# module_Rnx_ctrl.net
KiCad netlist of a schematic drawn in EAGLE
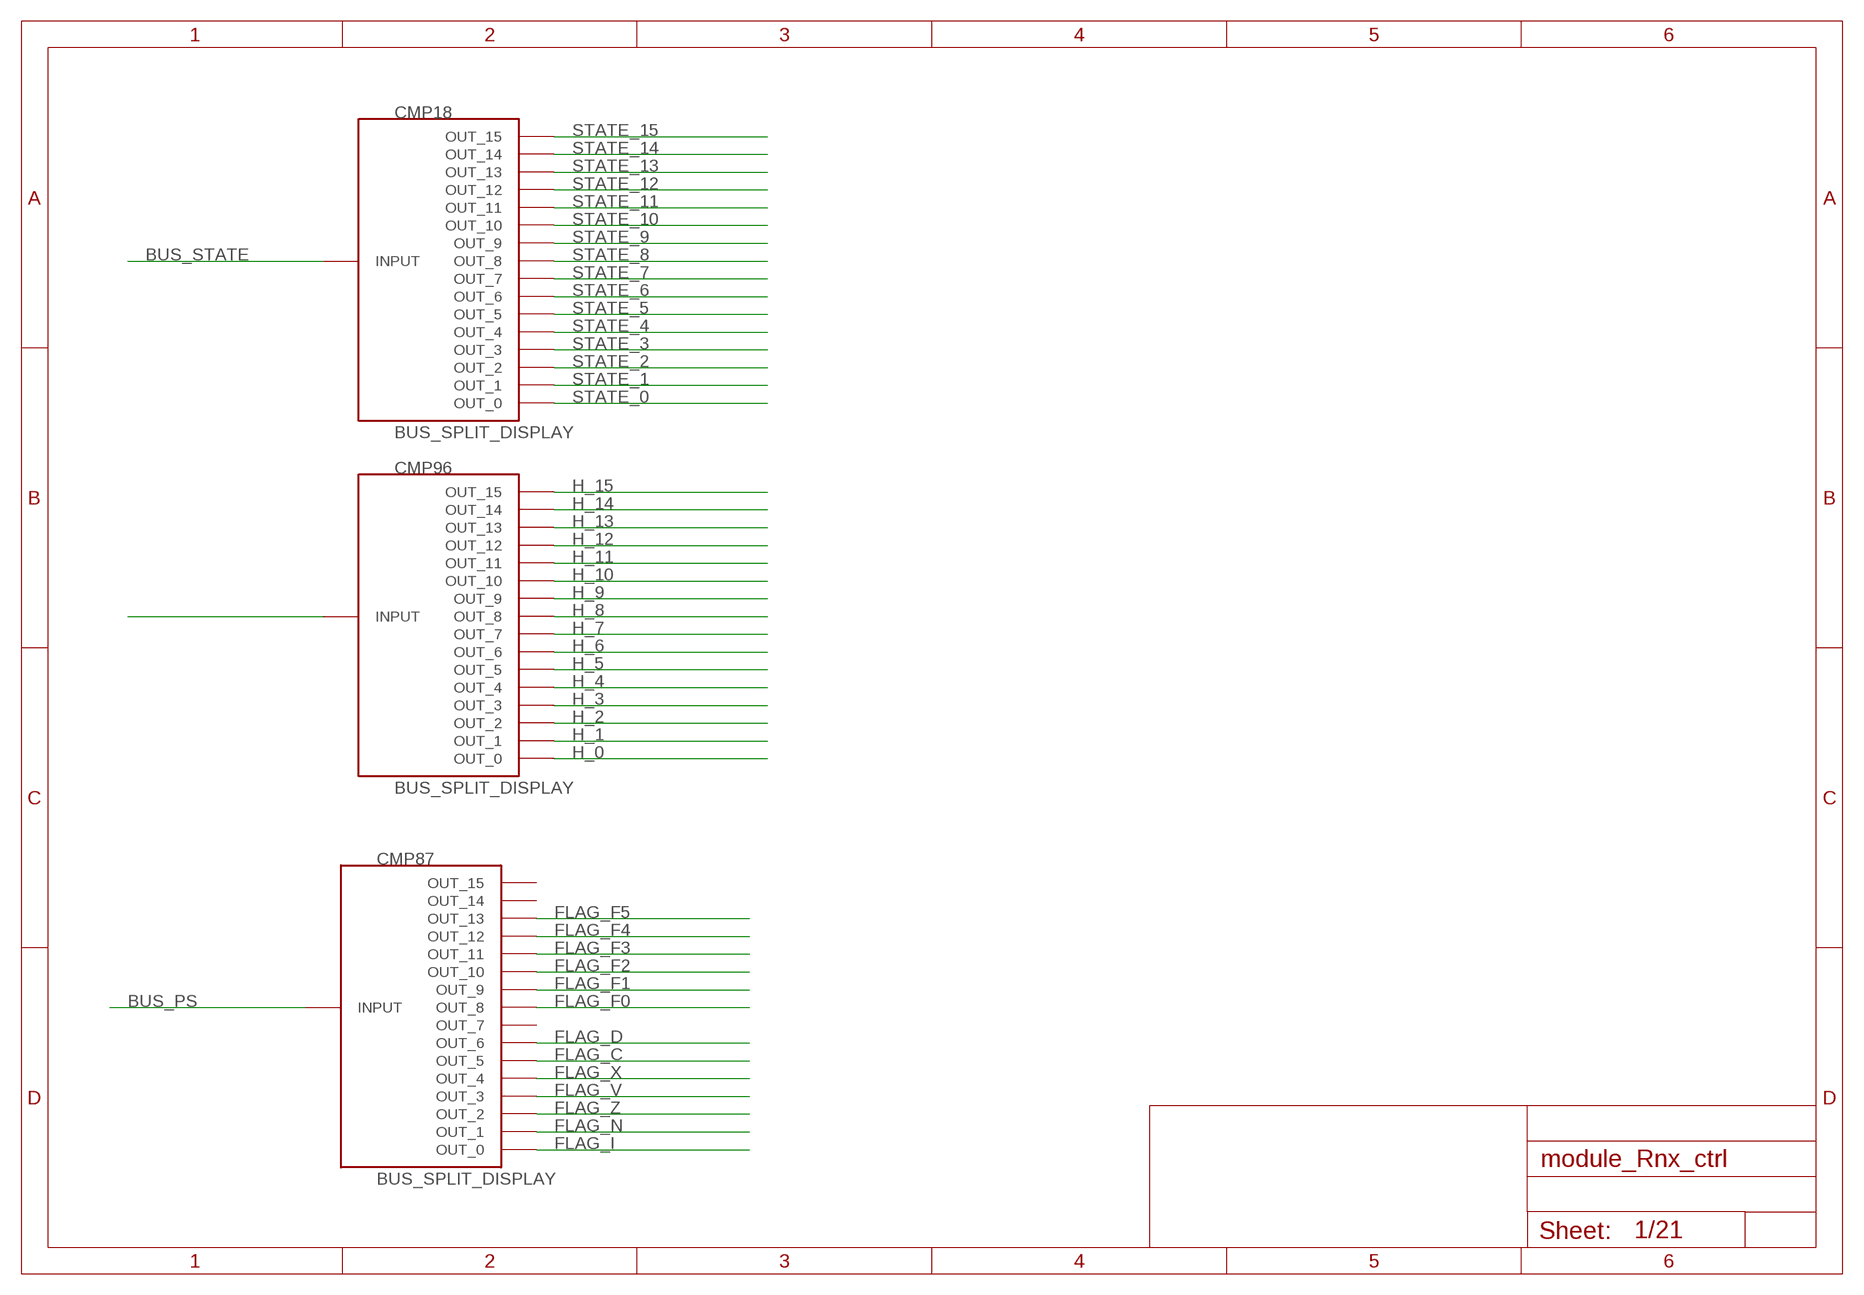
[diagram p0: schematic, sheet 1]
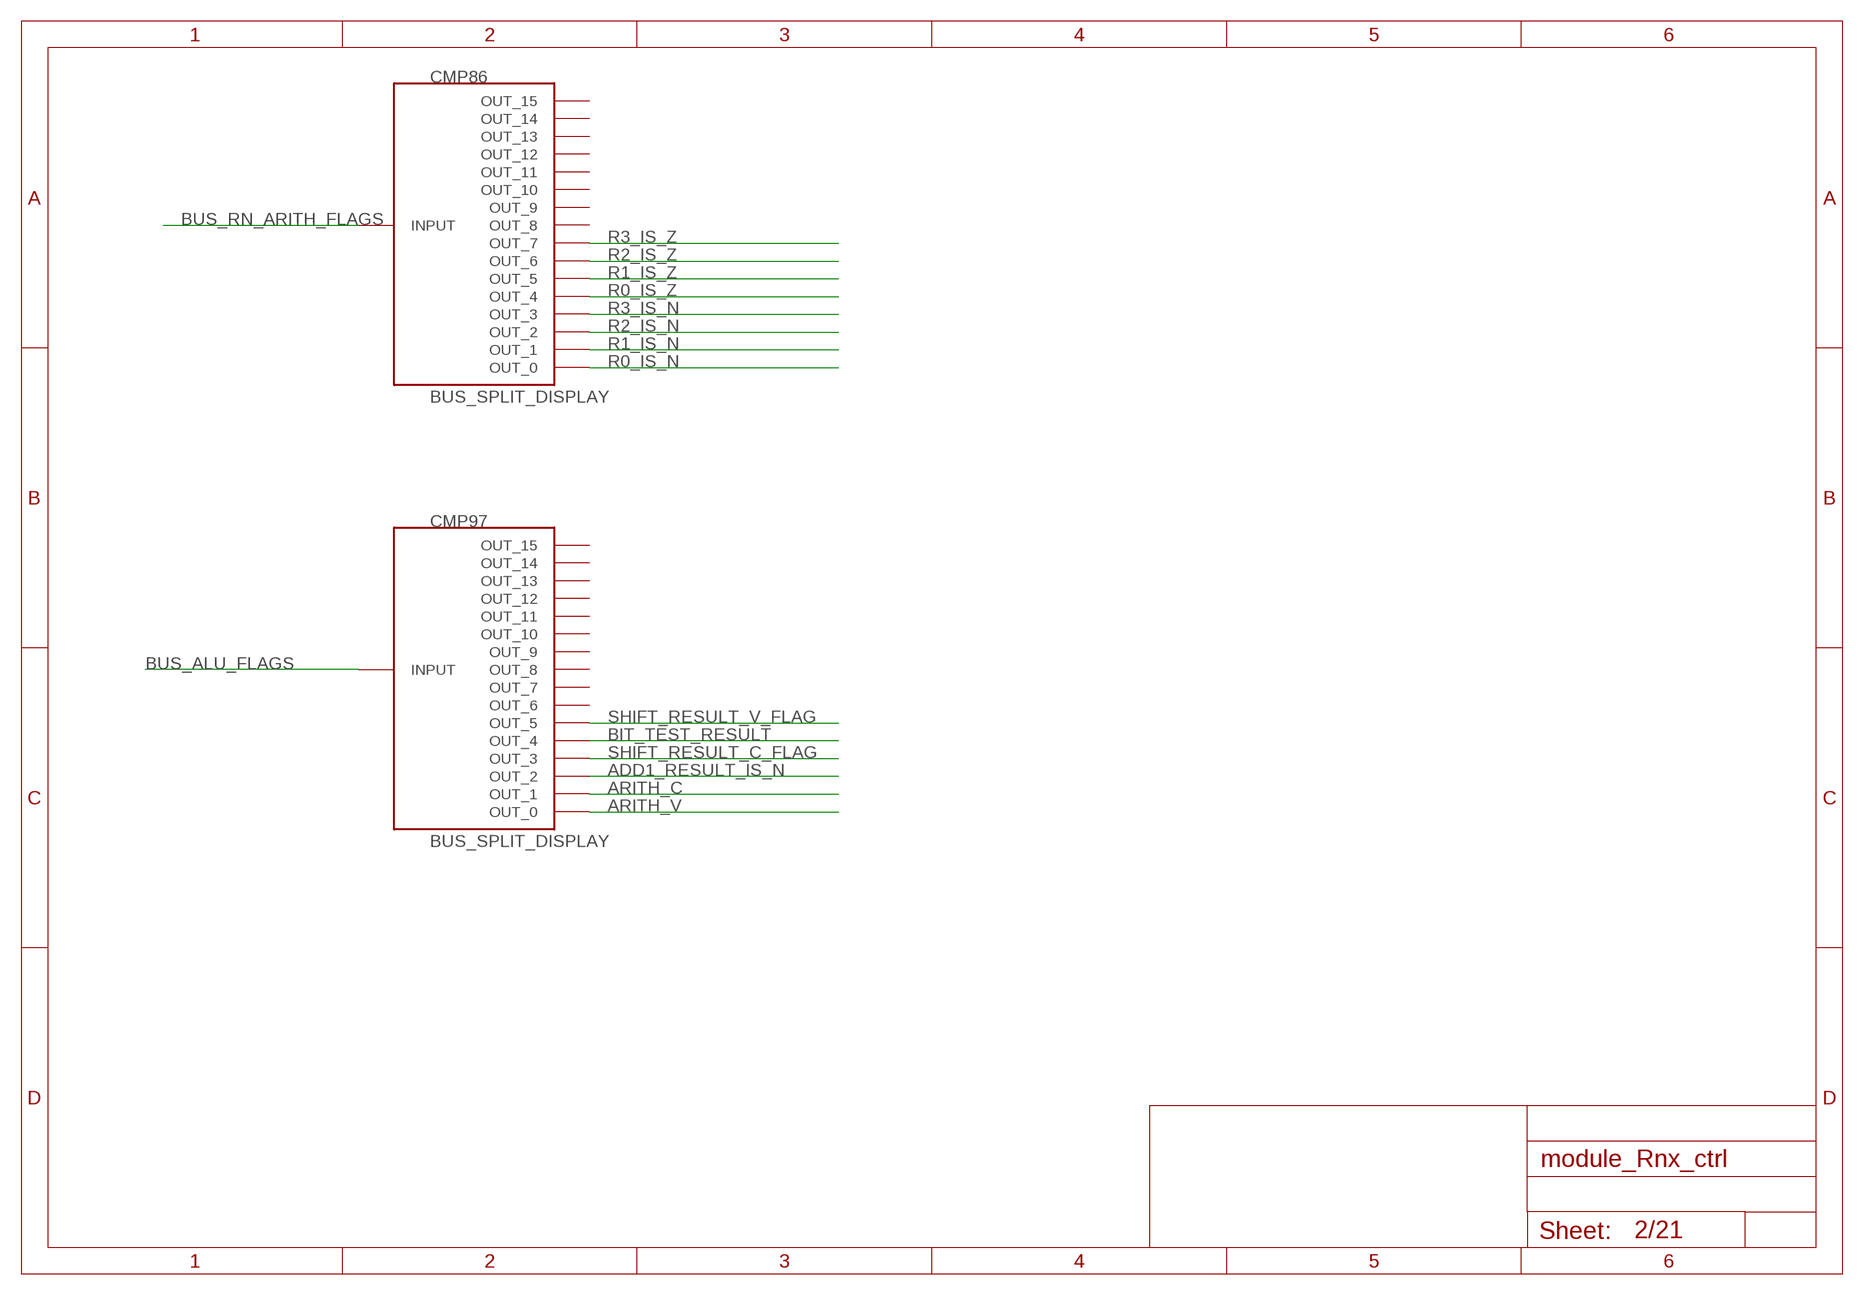
[diagram p1: schematic, sheet 2]
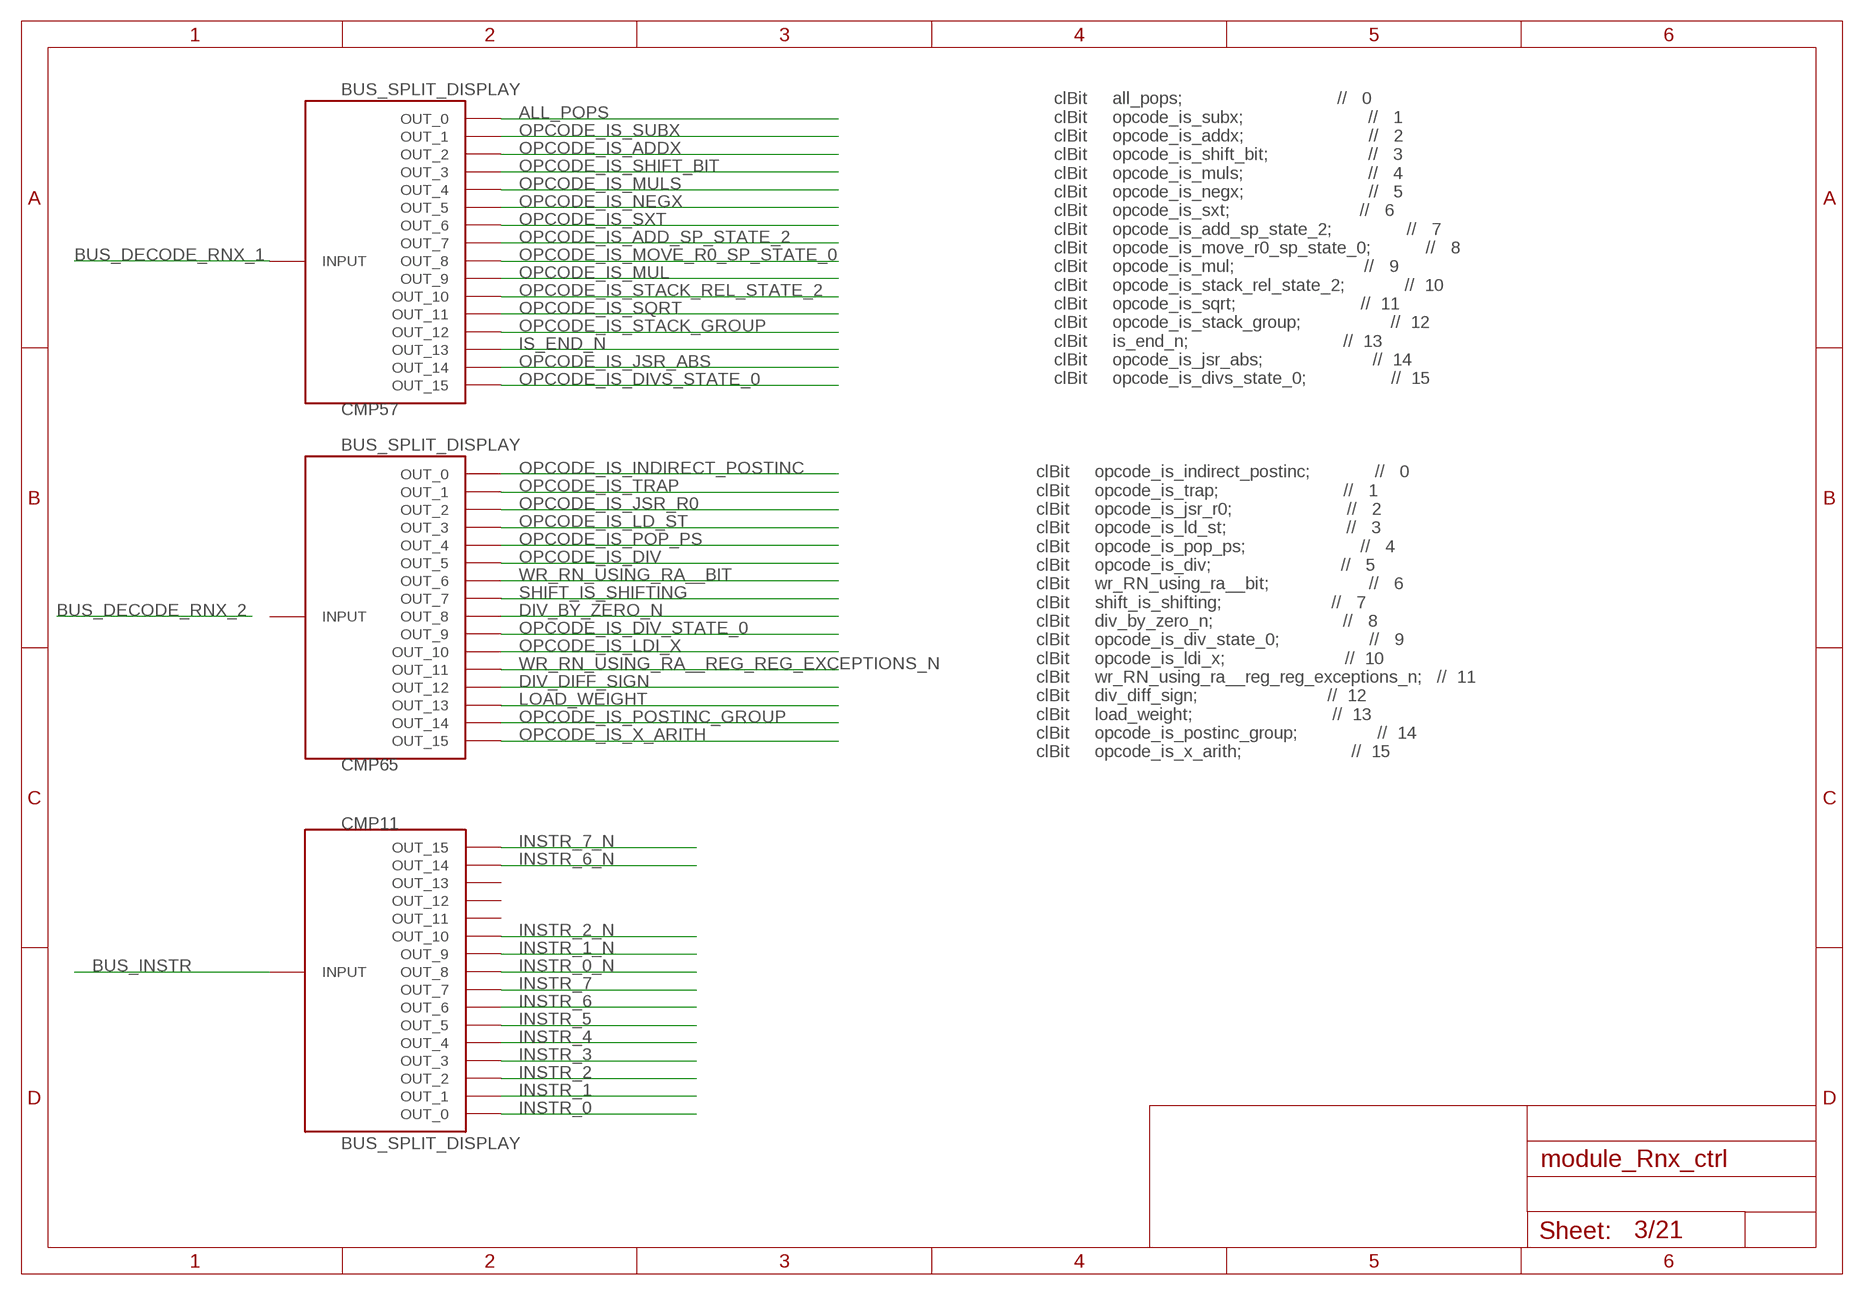
[diagram p2: schematic, sheet 3]
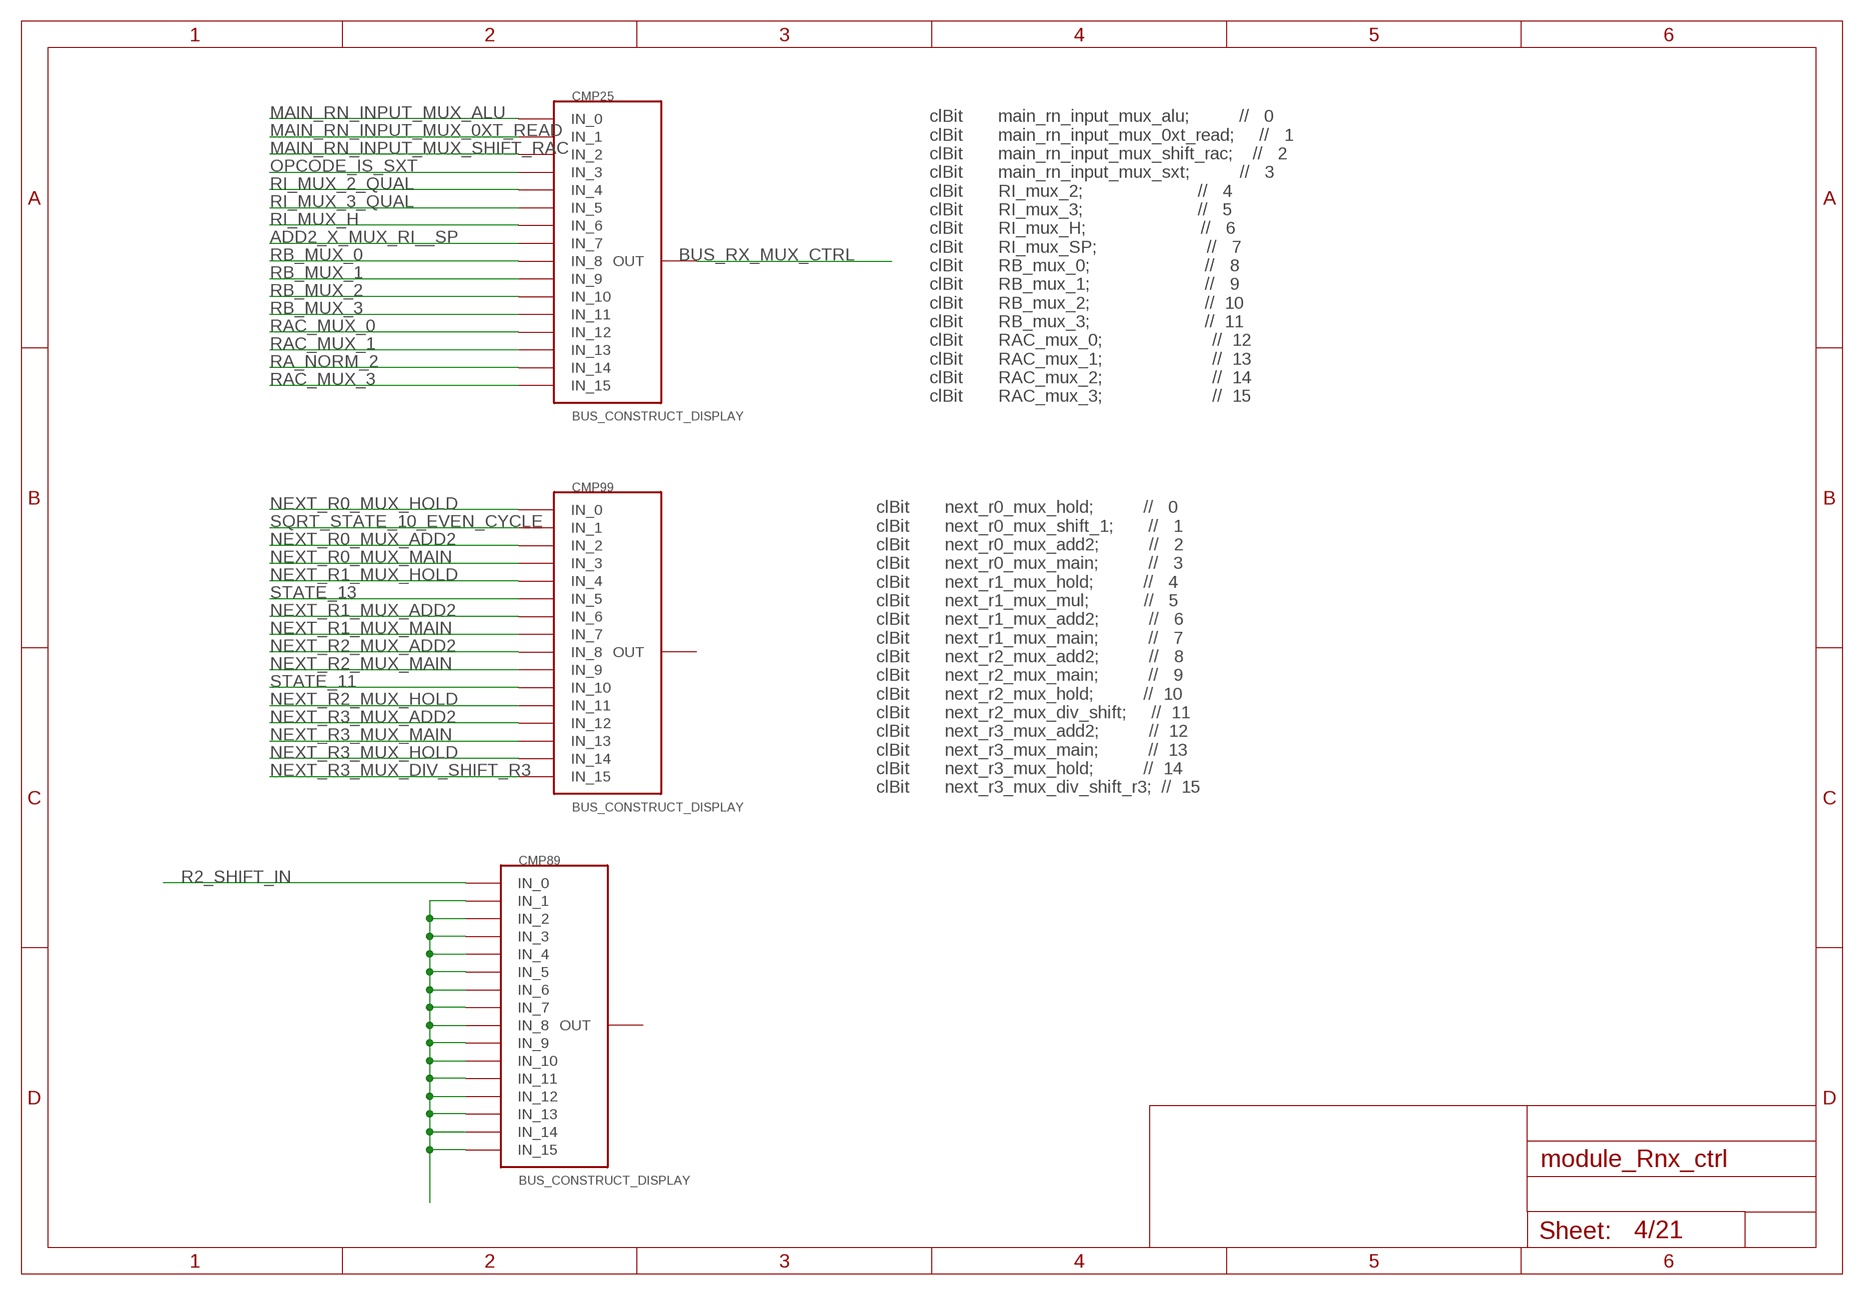
[diagram p3: schematic, sheet 4]
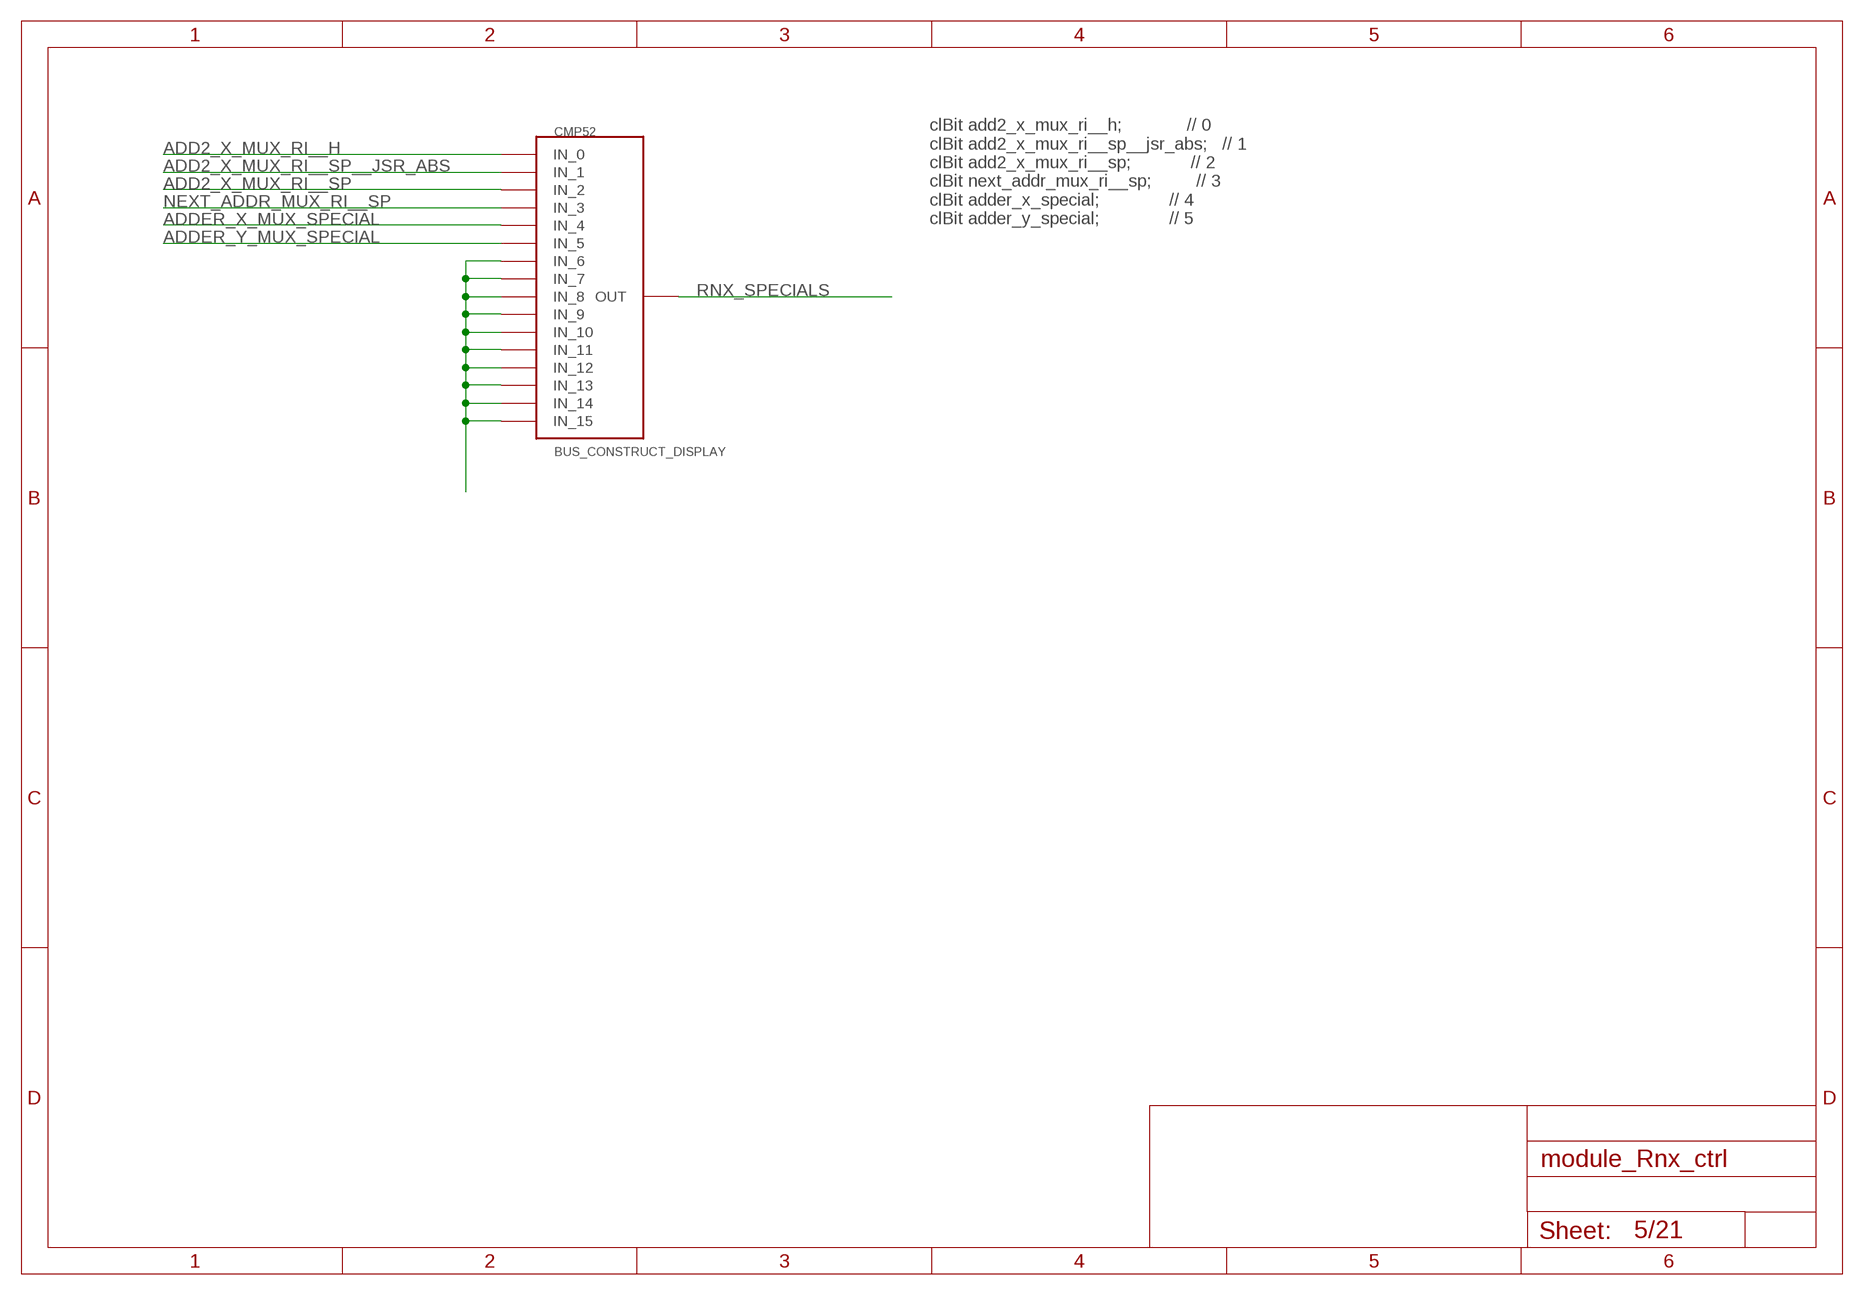
[diagram p4: schematic, sheet 5]
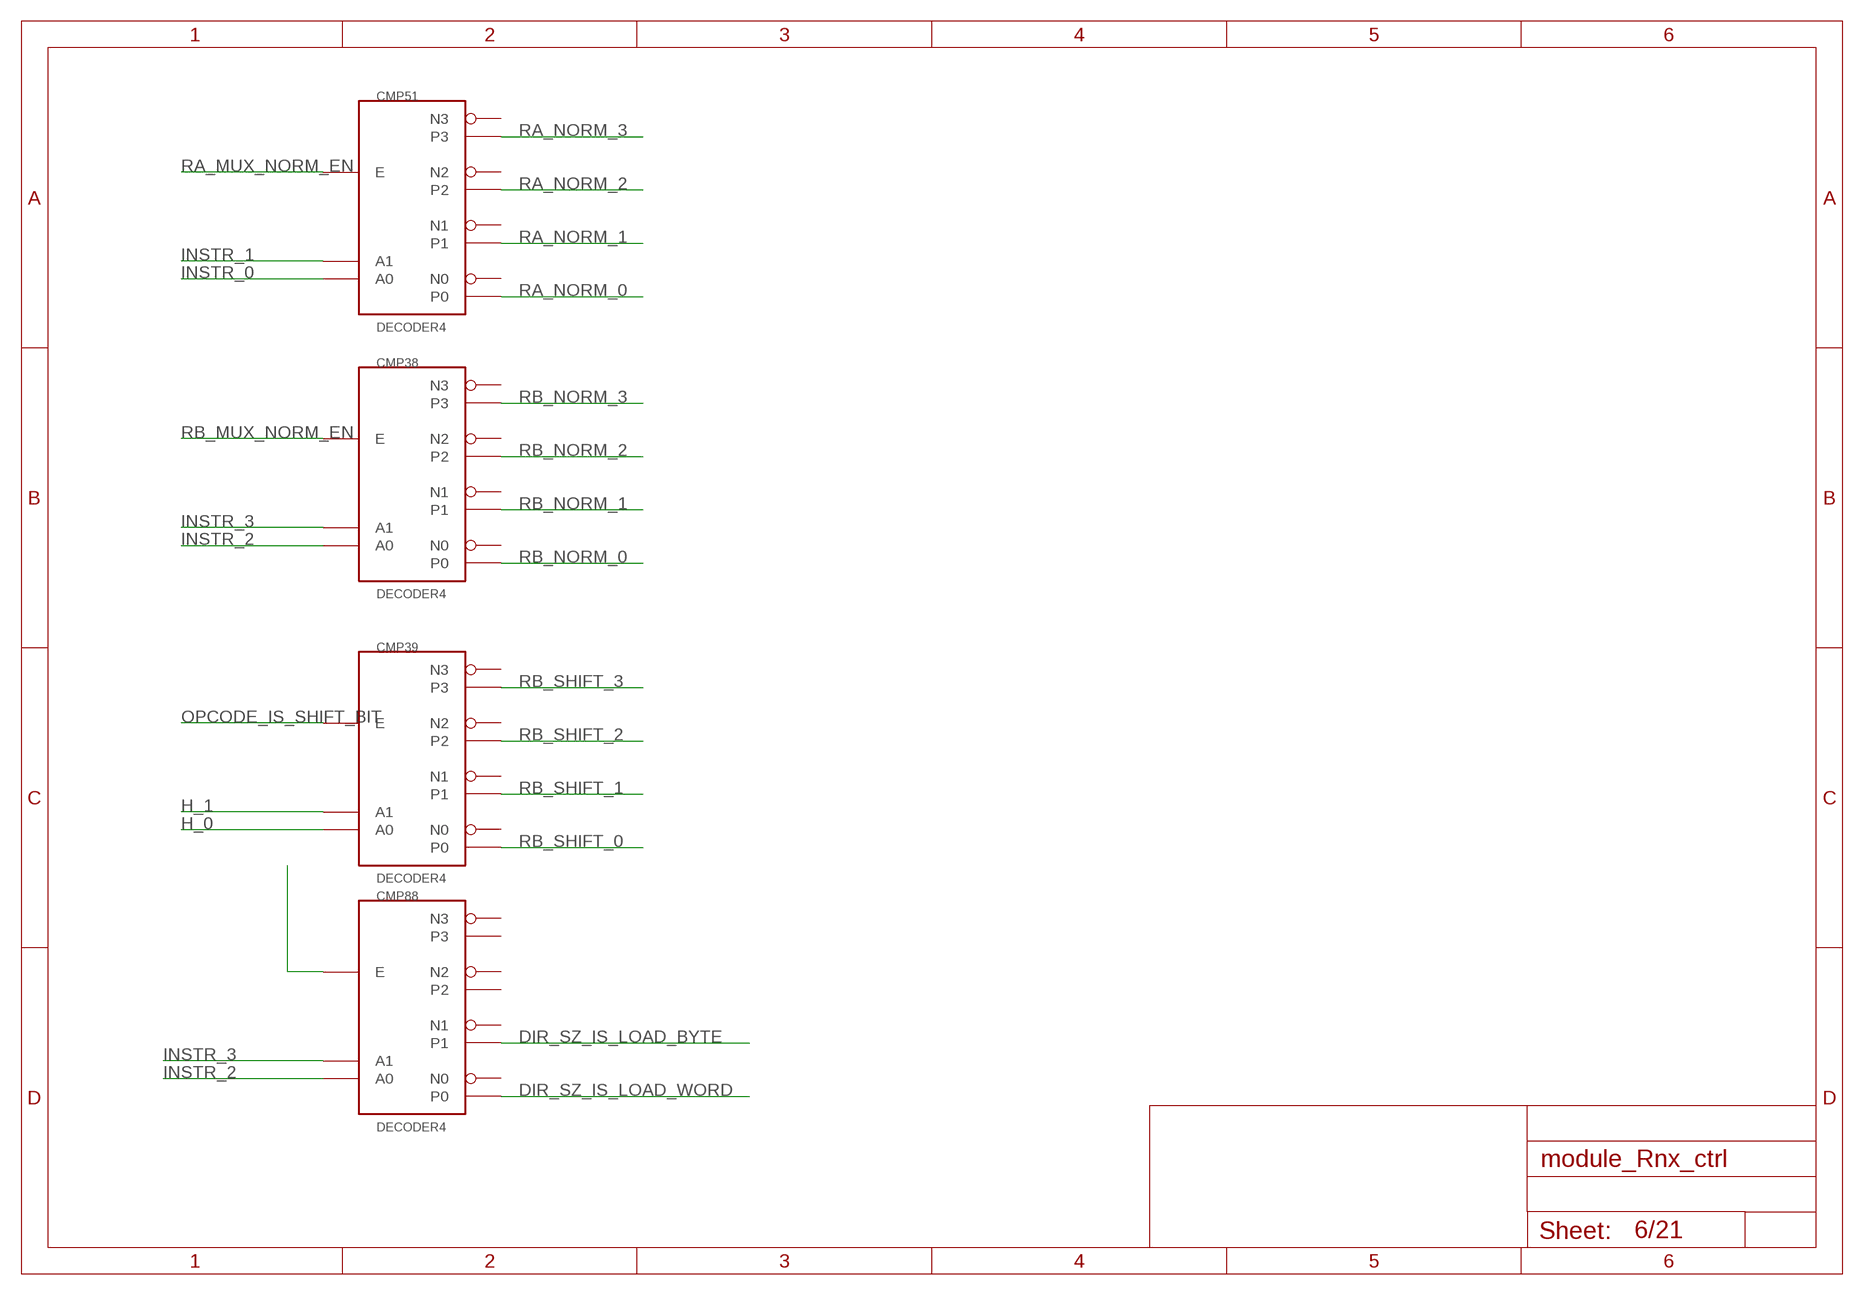
[diagram p5: schematic, sheet 6]
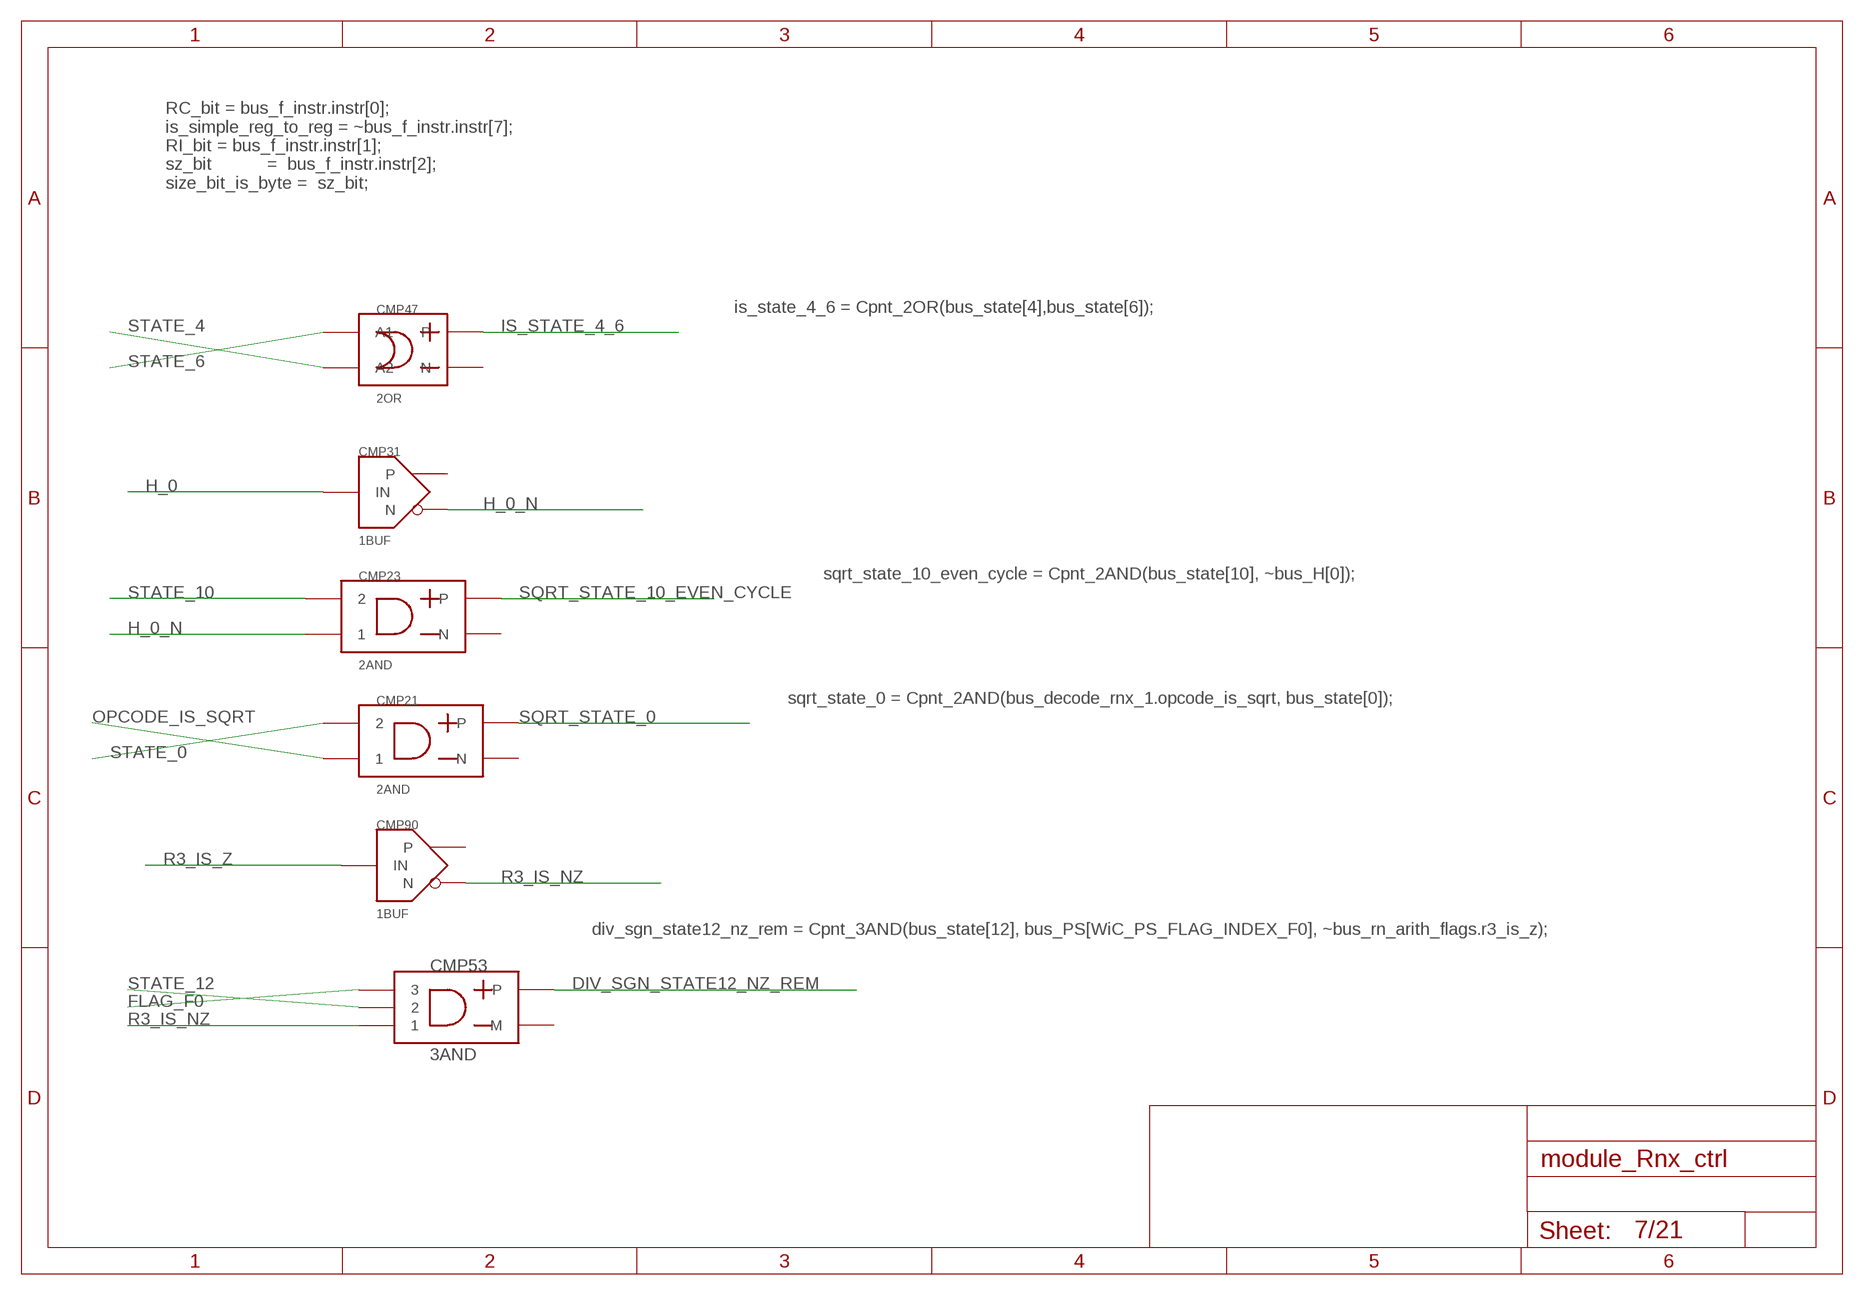
[diagram p6: schematic, sheet 7]
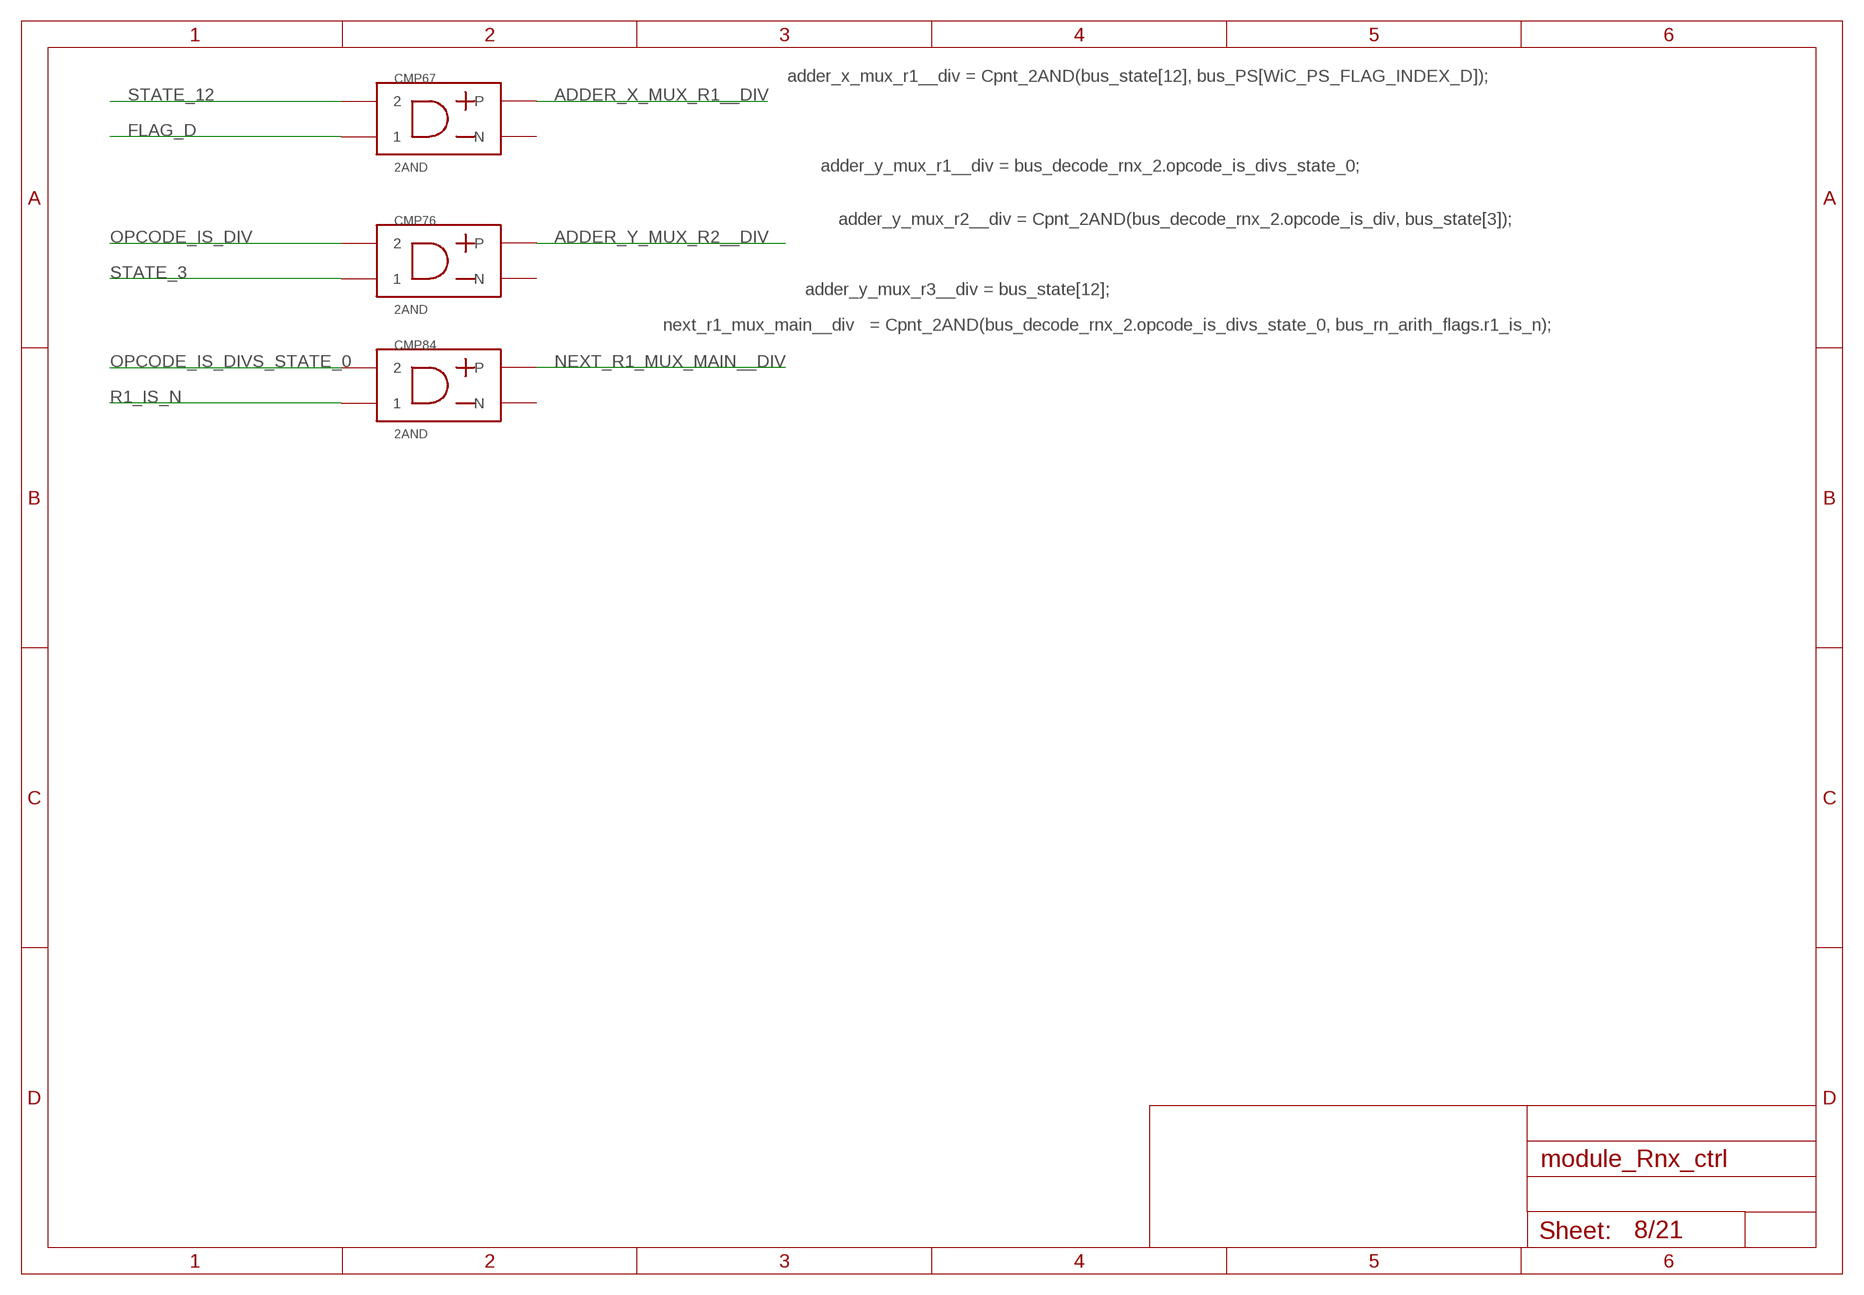
[diagram p7: schematic, sheet 8]
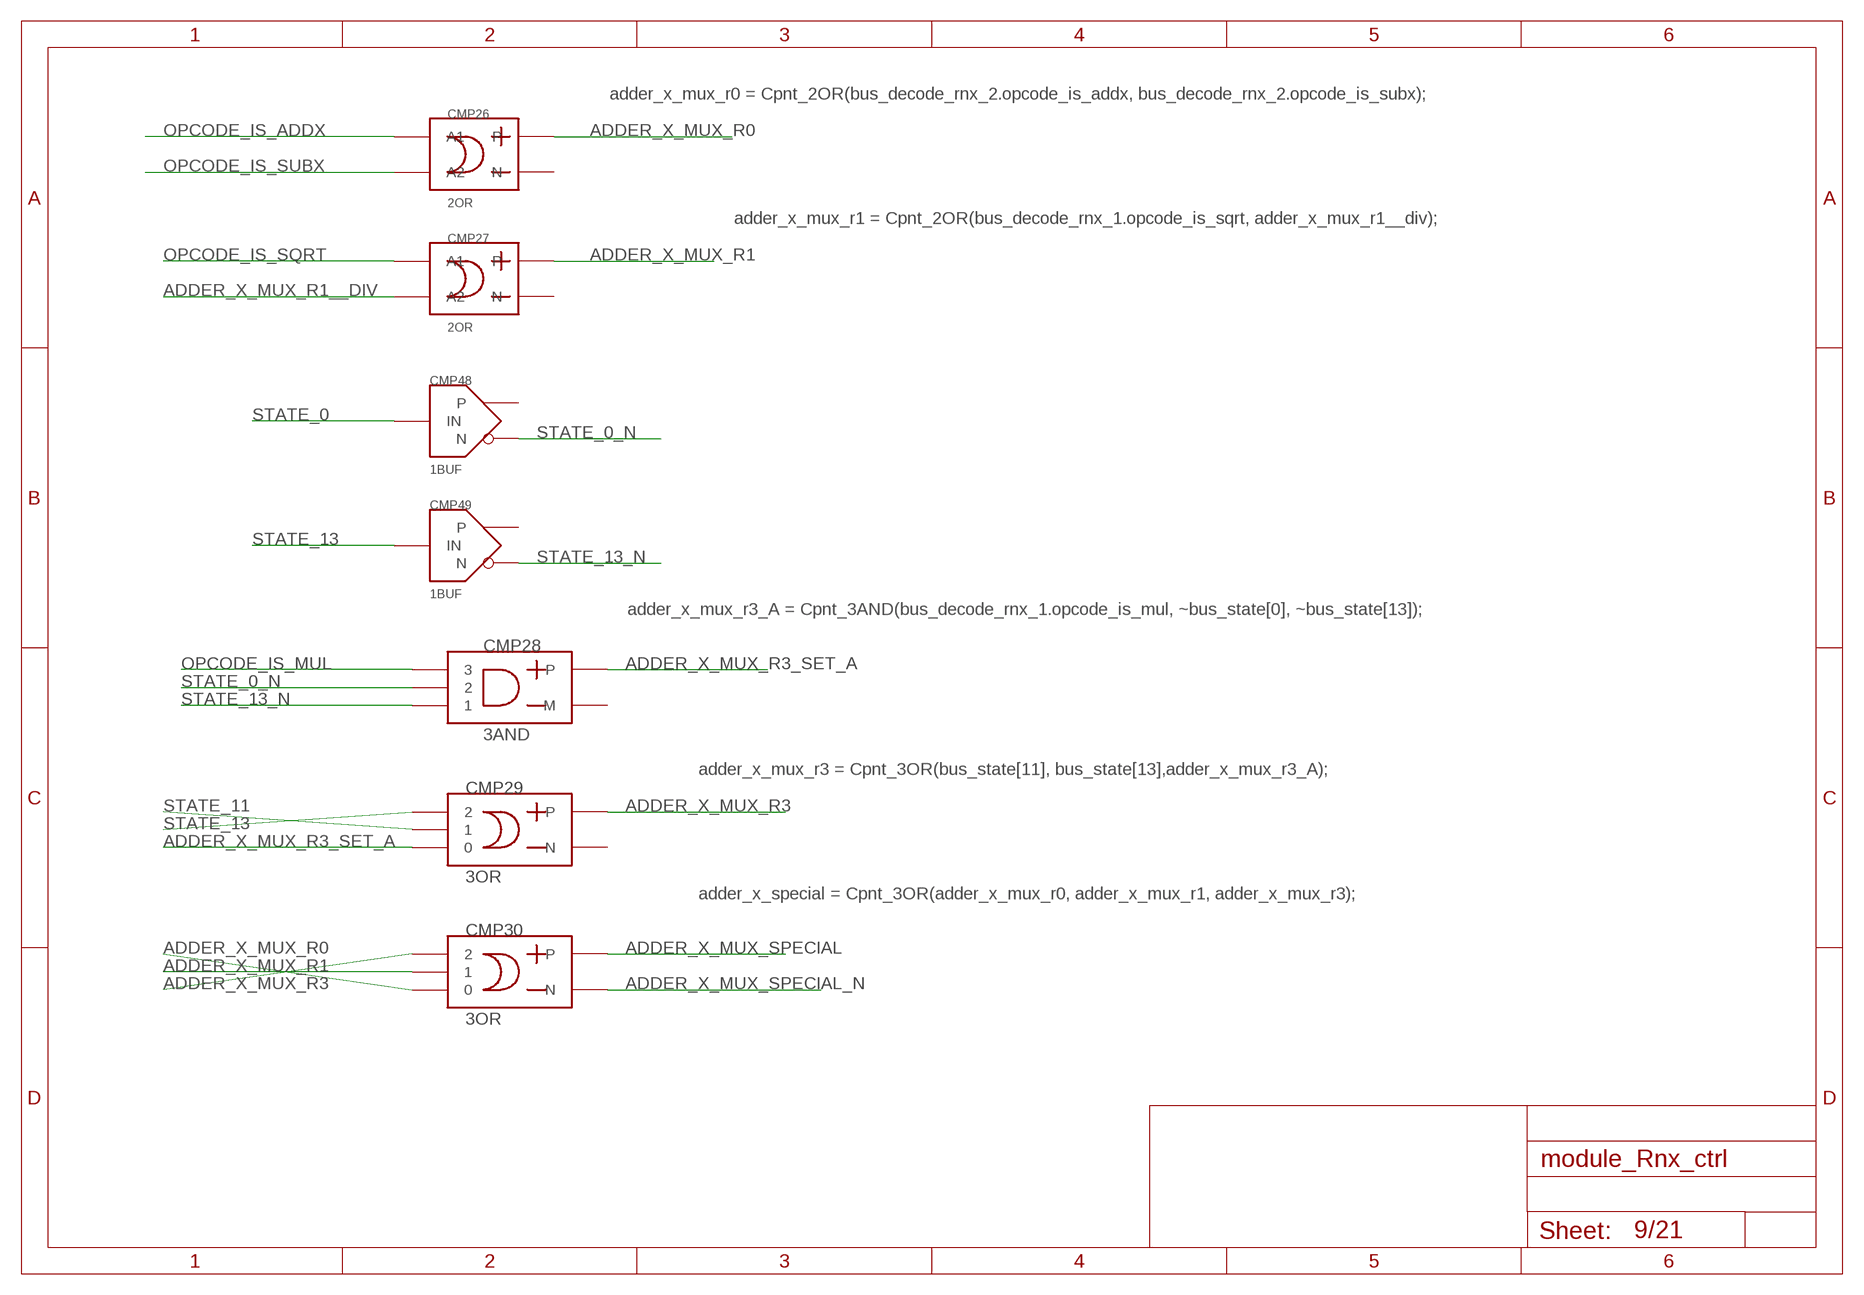
[diagram p8: schematic, sheet 9]
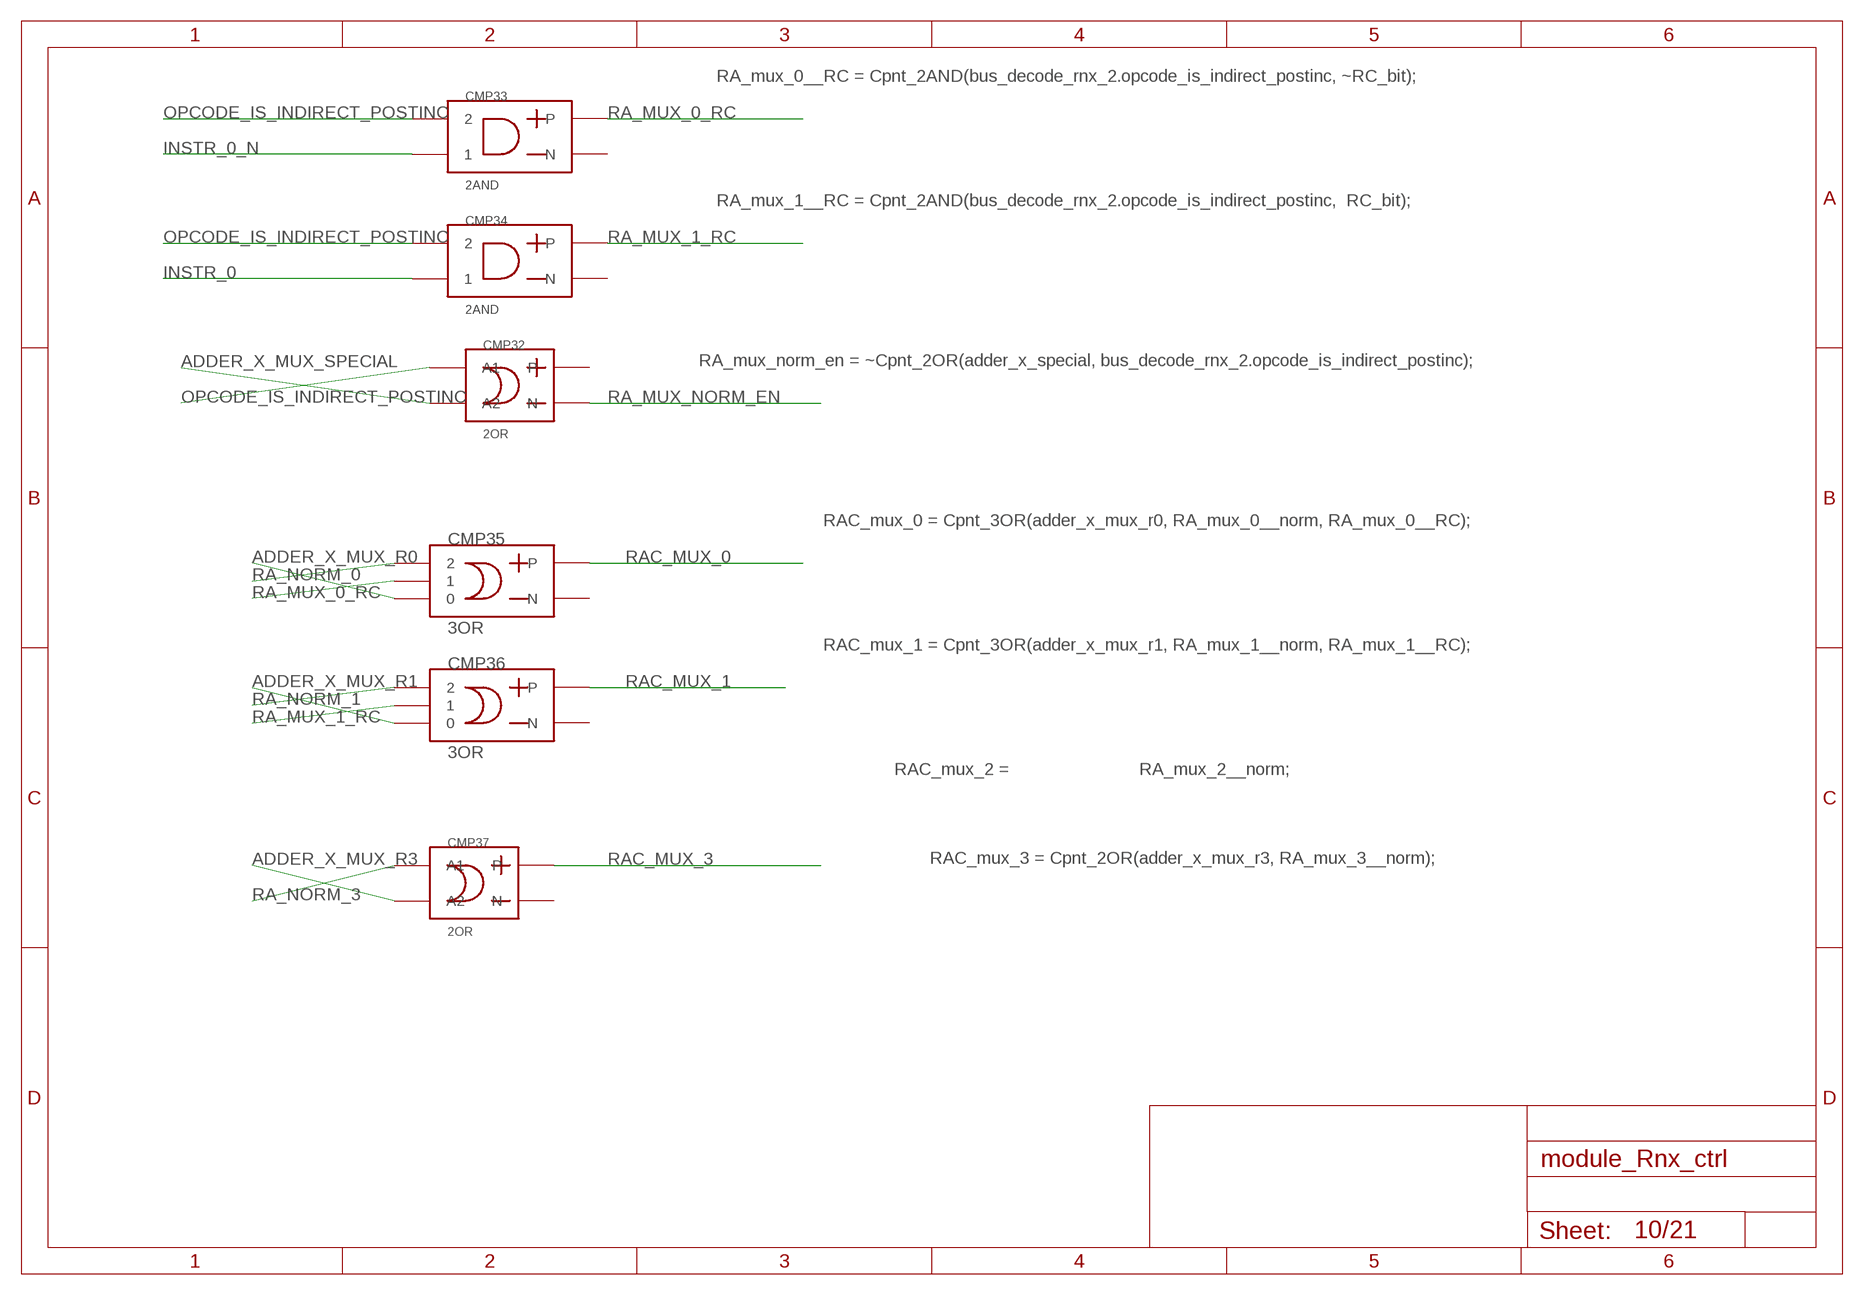
[diagram p9: schematic, sheet 10]
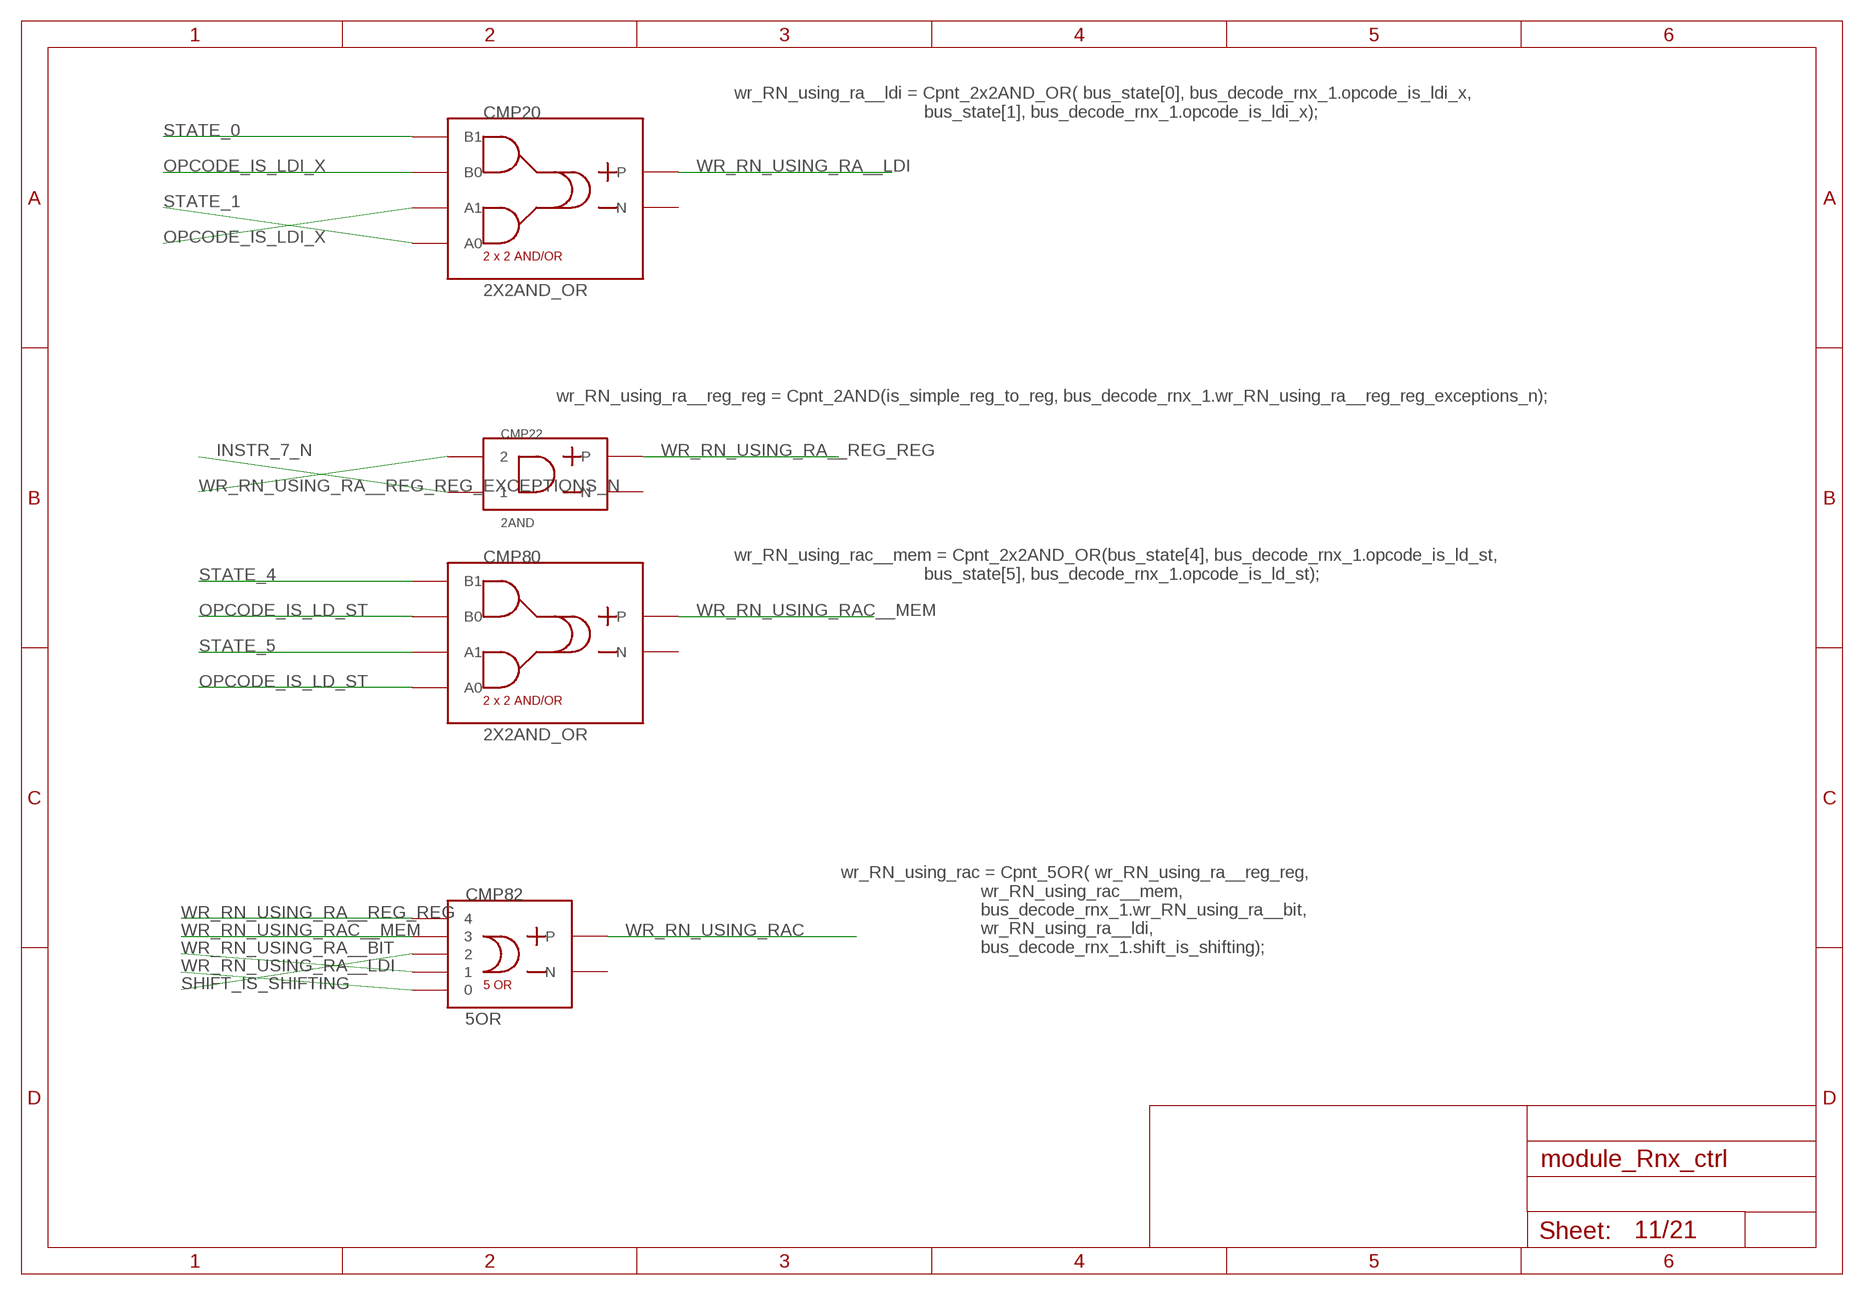
[diagram p10: schematic, sheet 11]
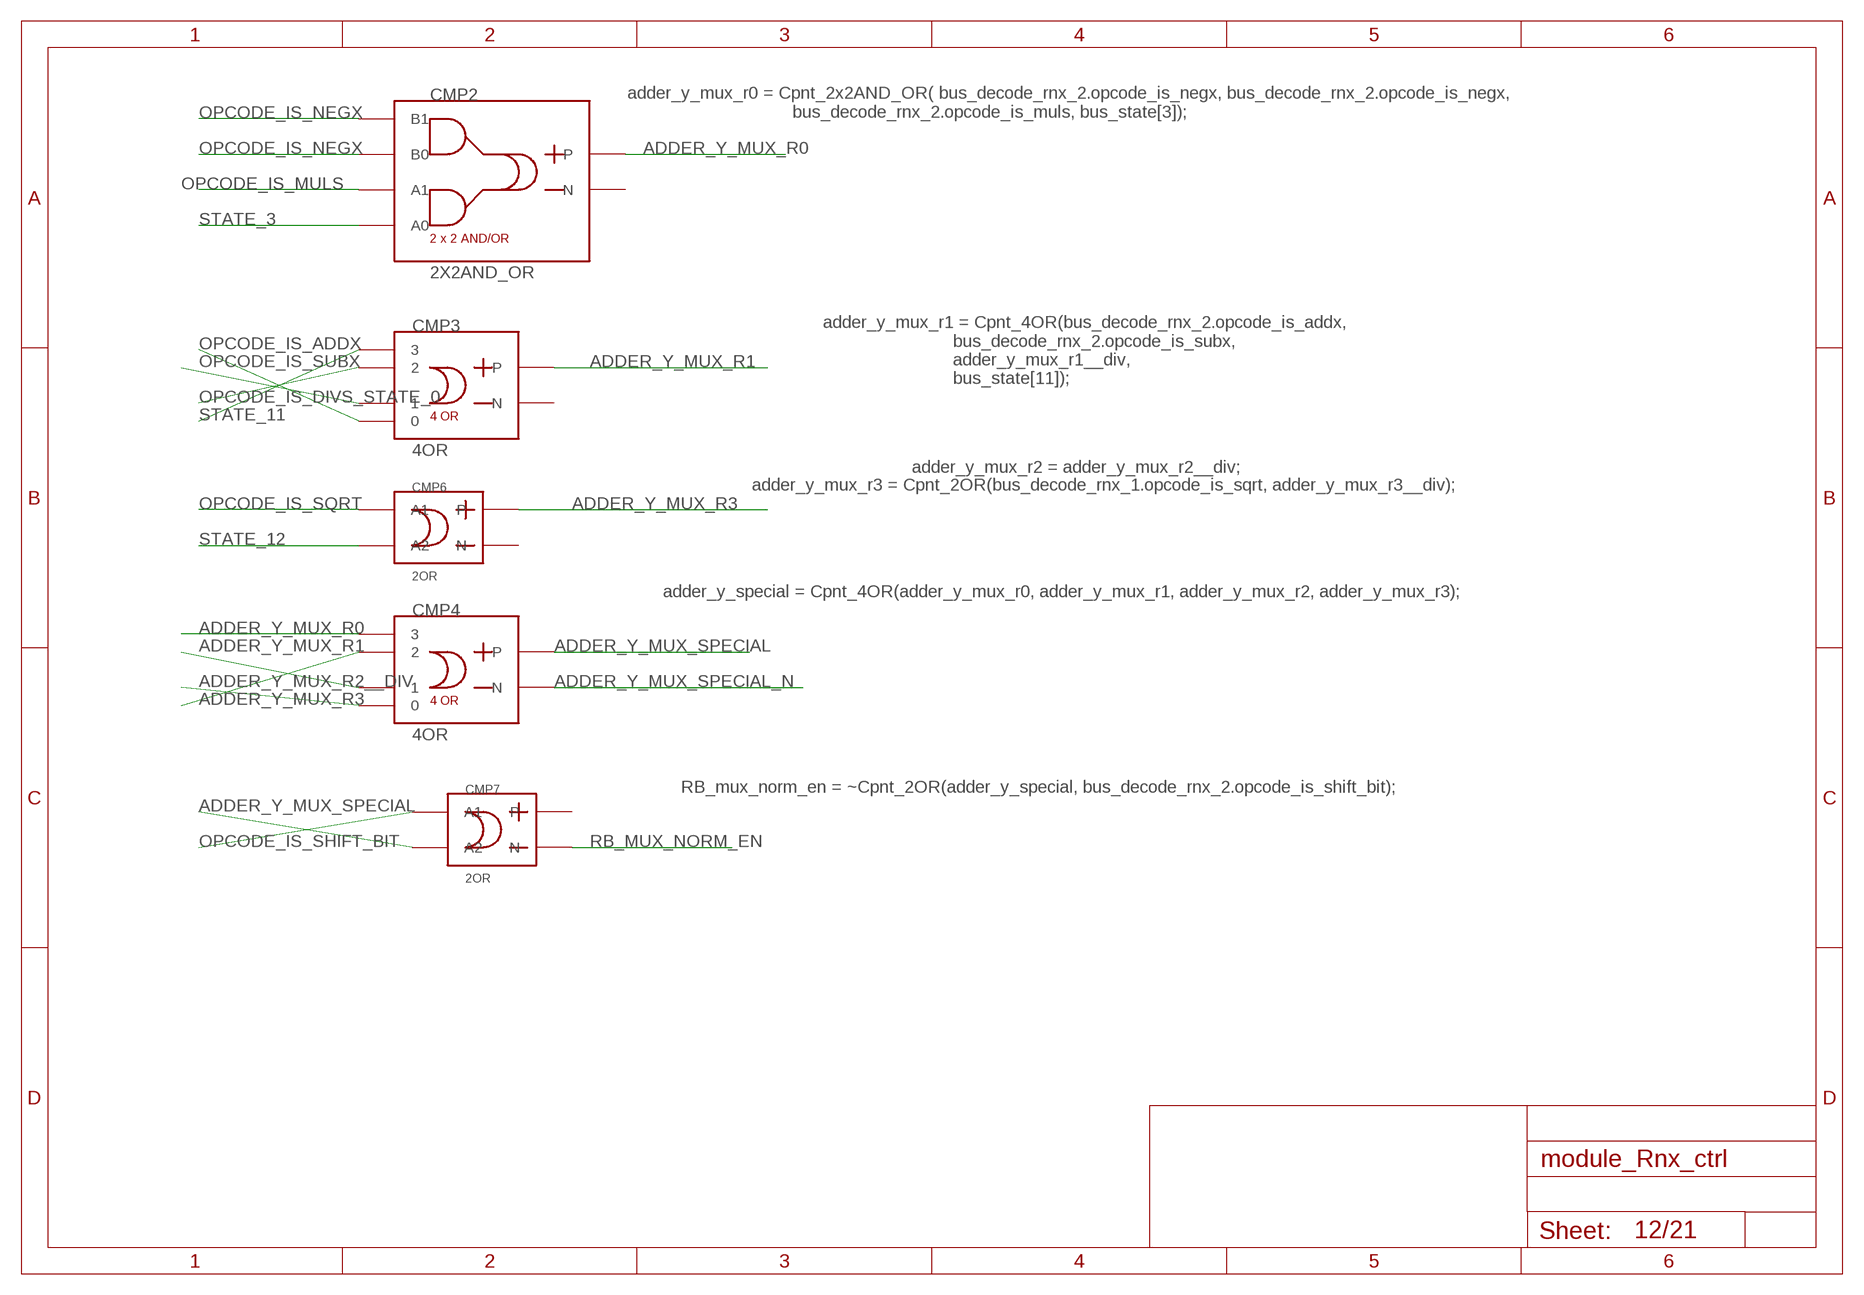
[diagram p11: schematic, sheet 12]
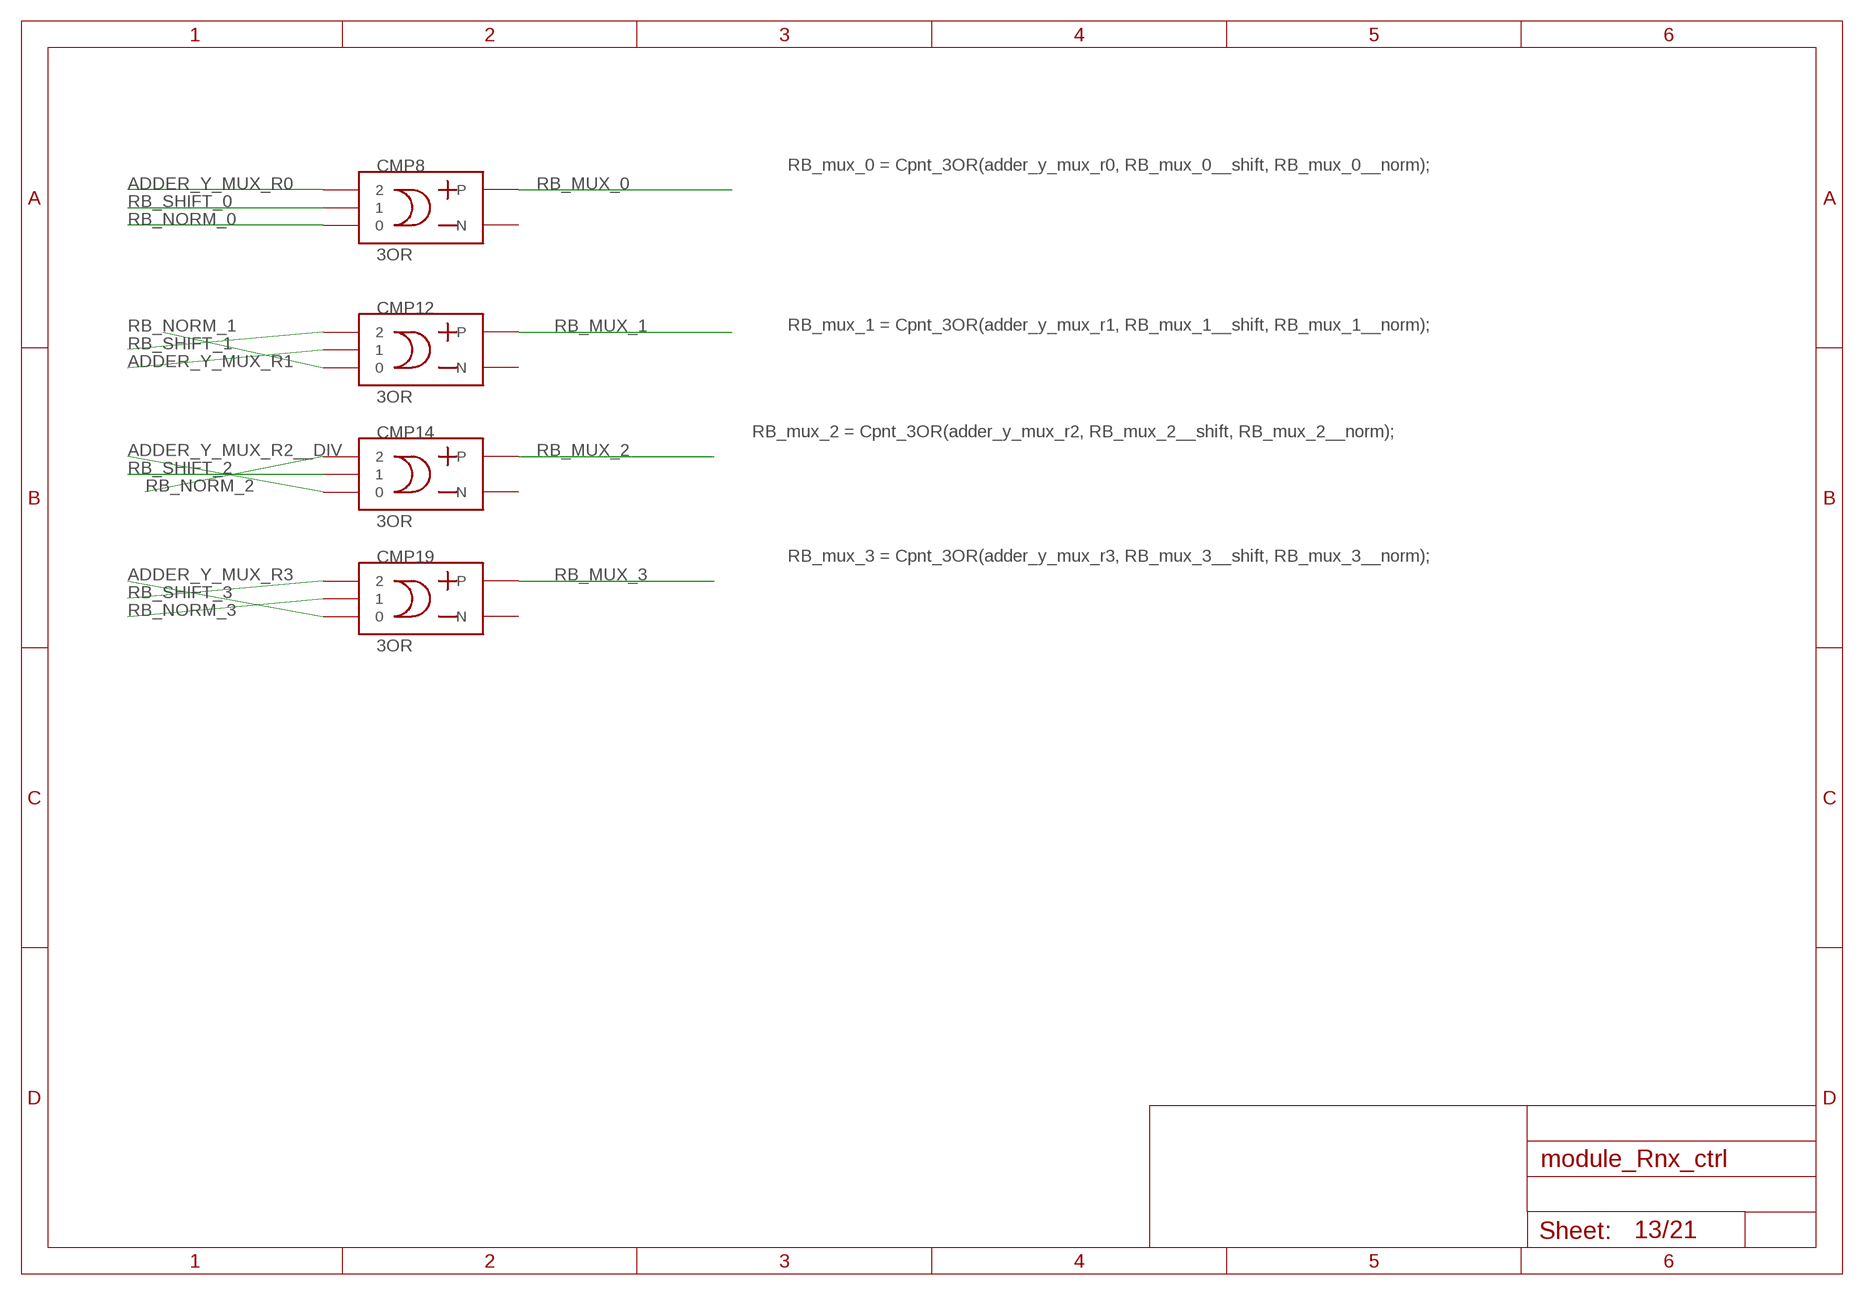
[diagram p12: schematic, sheet 13]
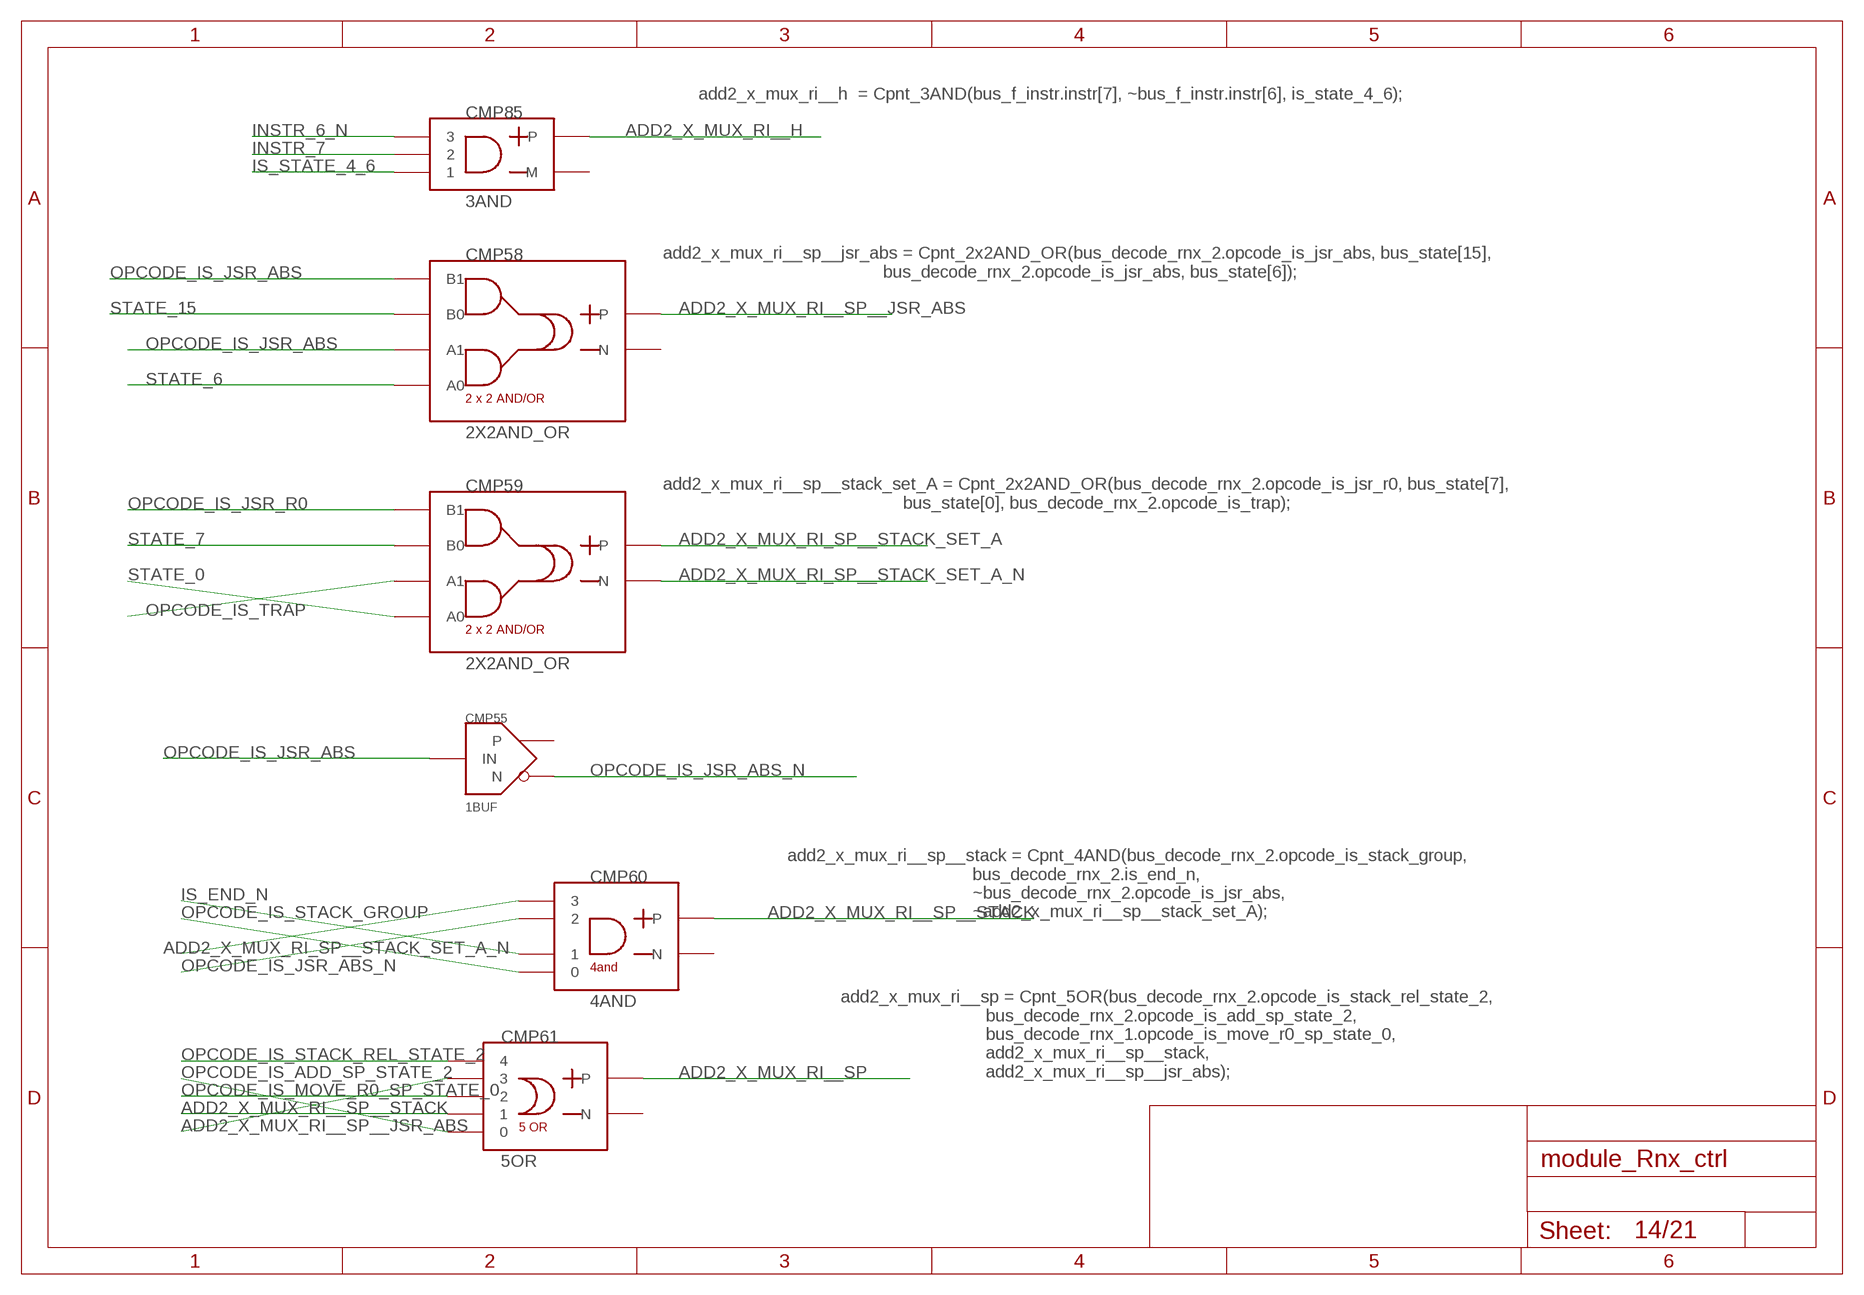
[diagram p13: schematic, sheet 14]
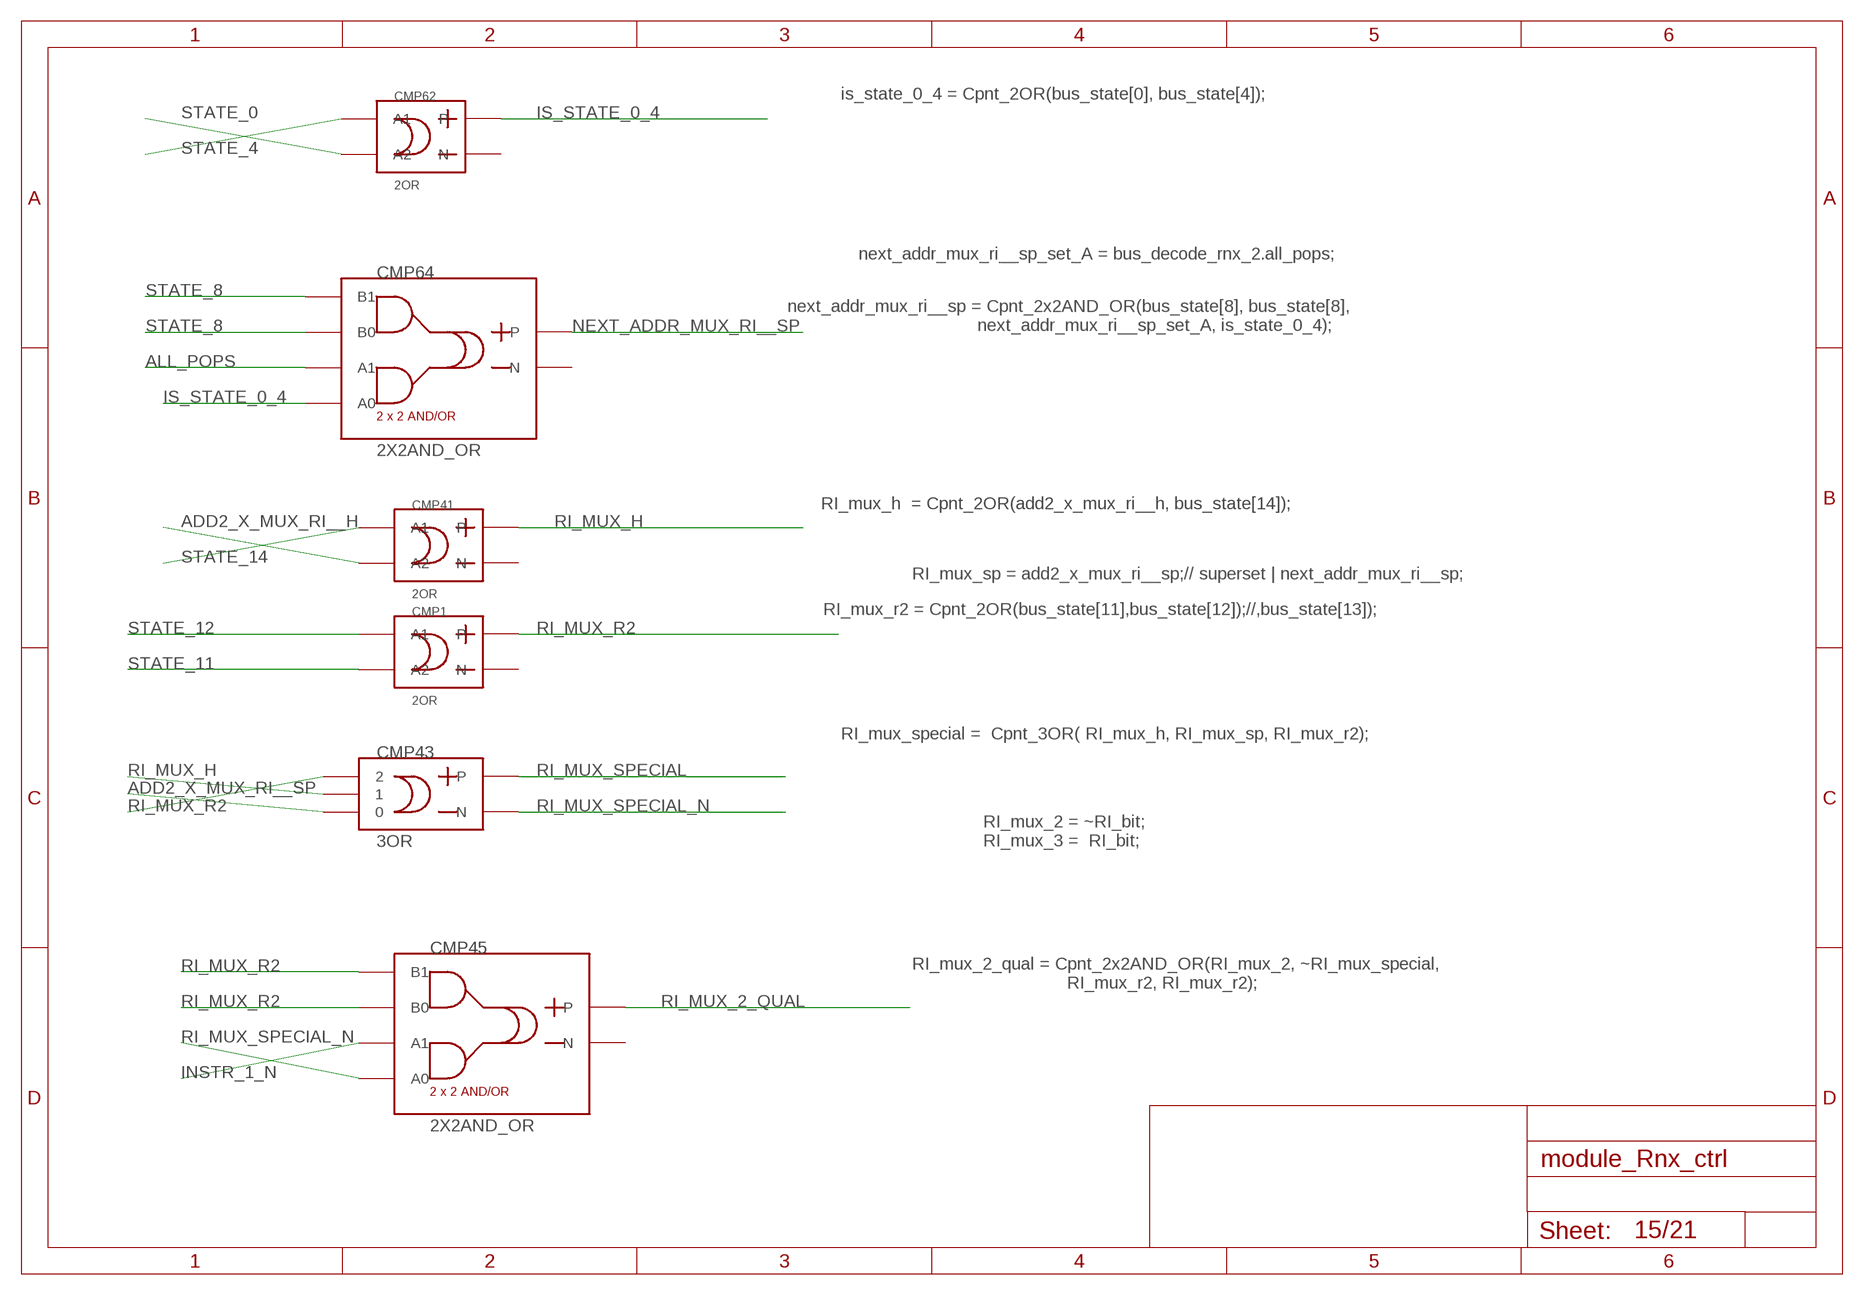
[diagram p14: schematic, sheet 15]
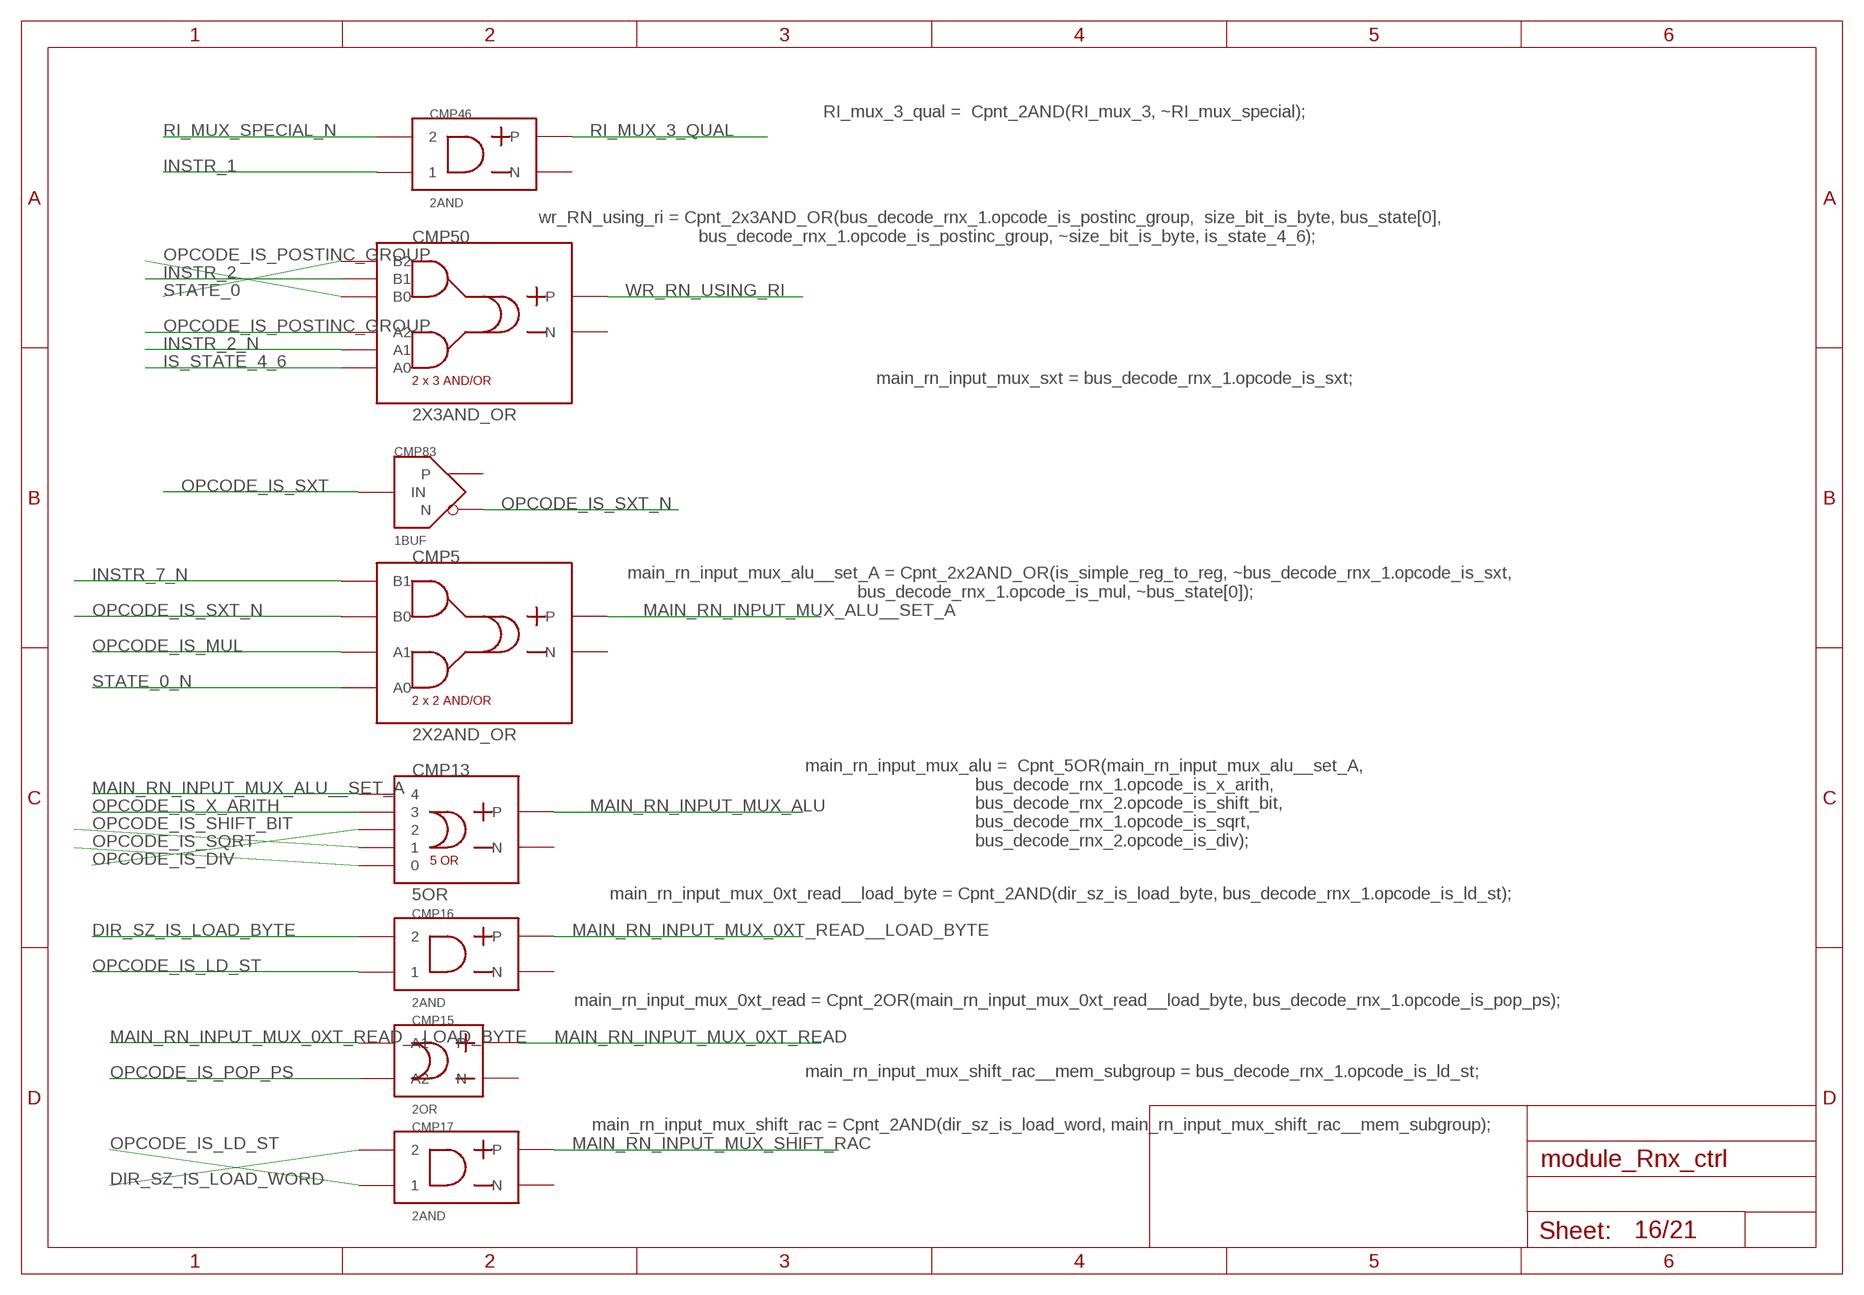
[diagram p15: schematic, sheet 16]
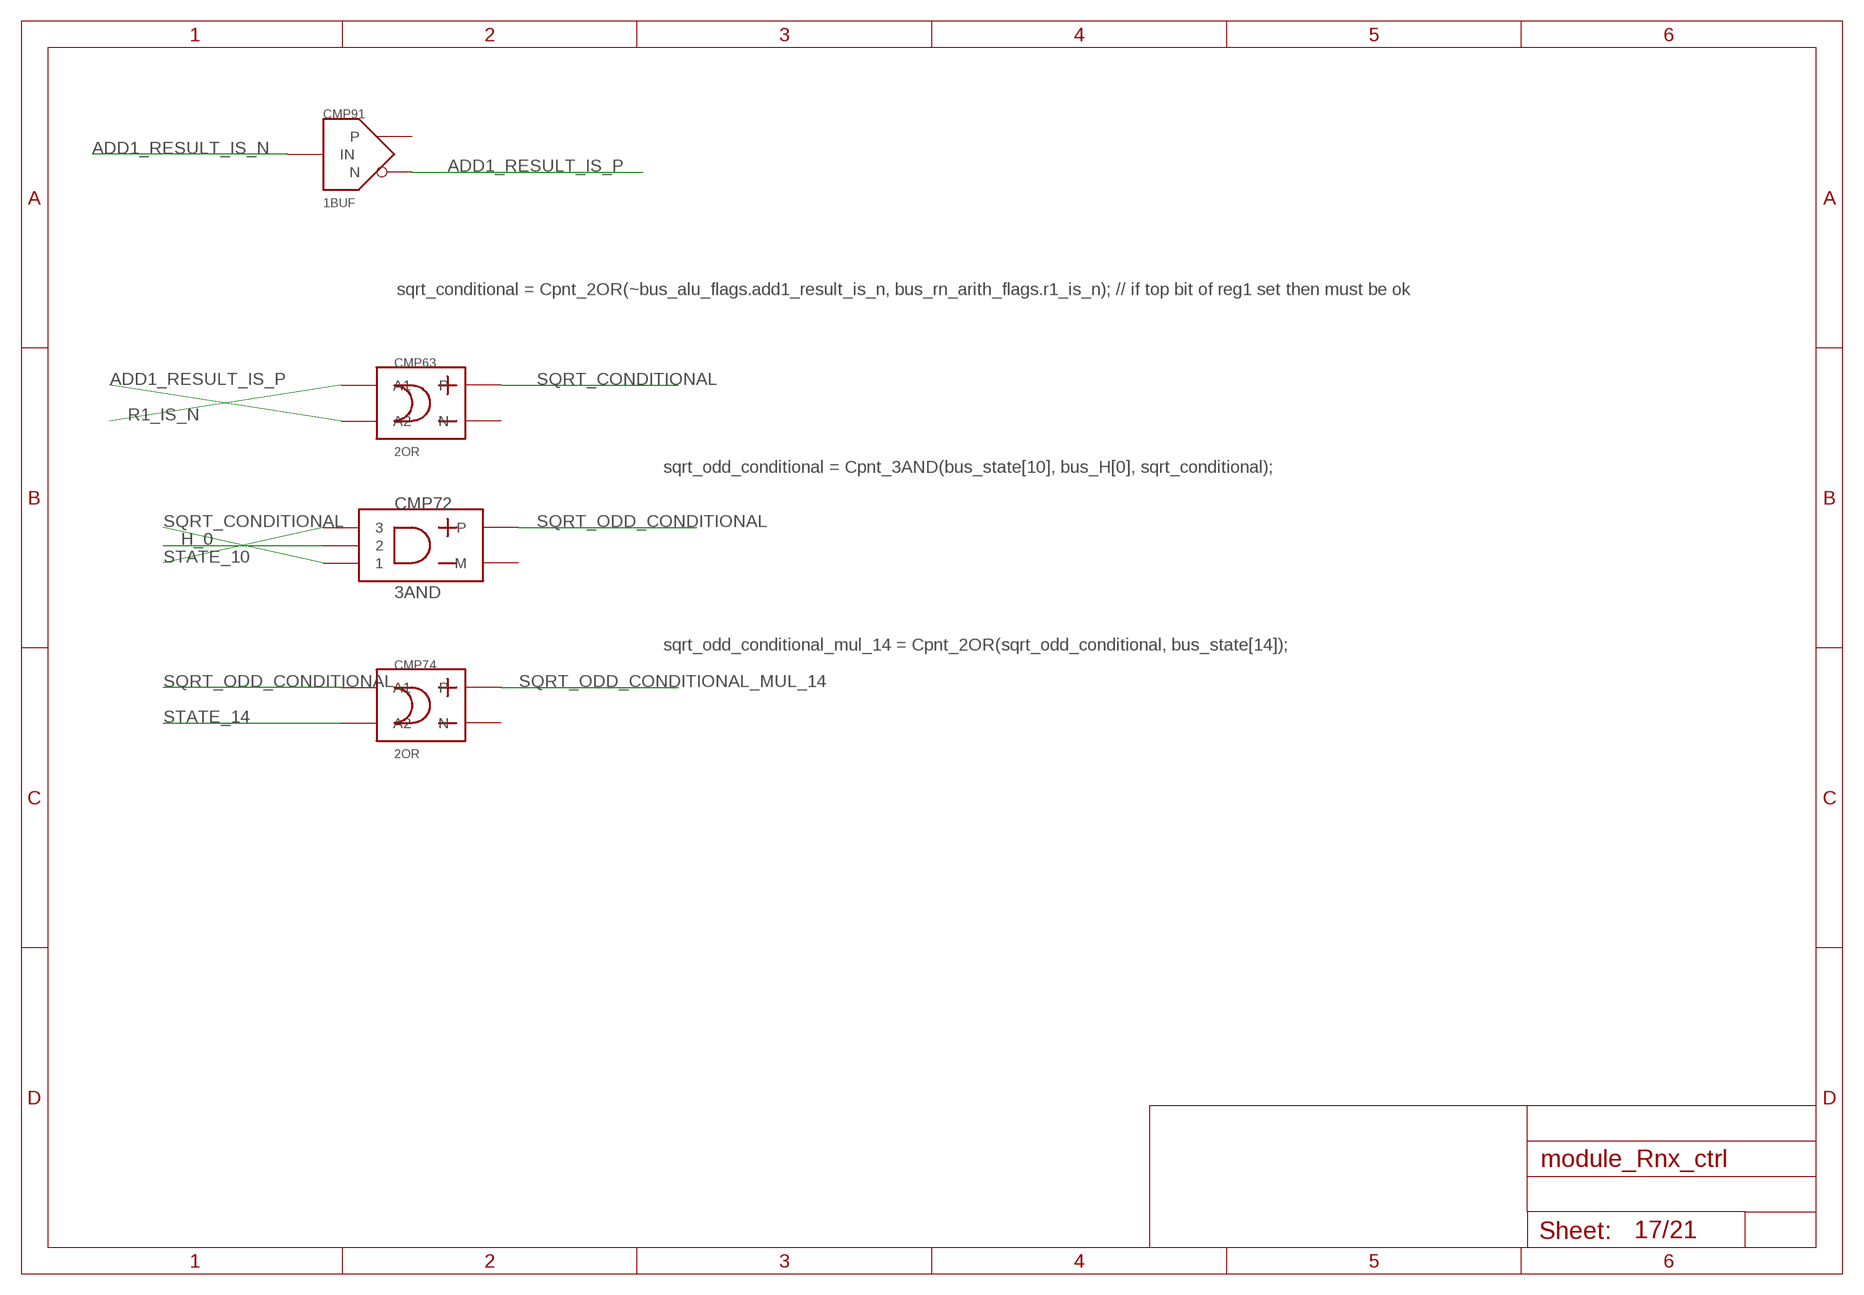
[diagram p16: schematic, sheet 17]
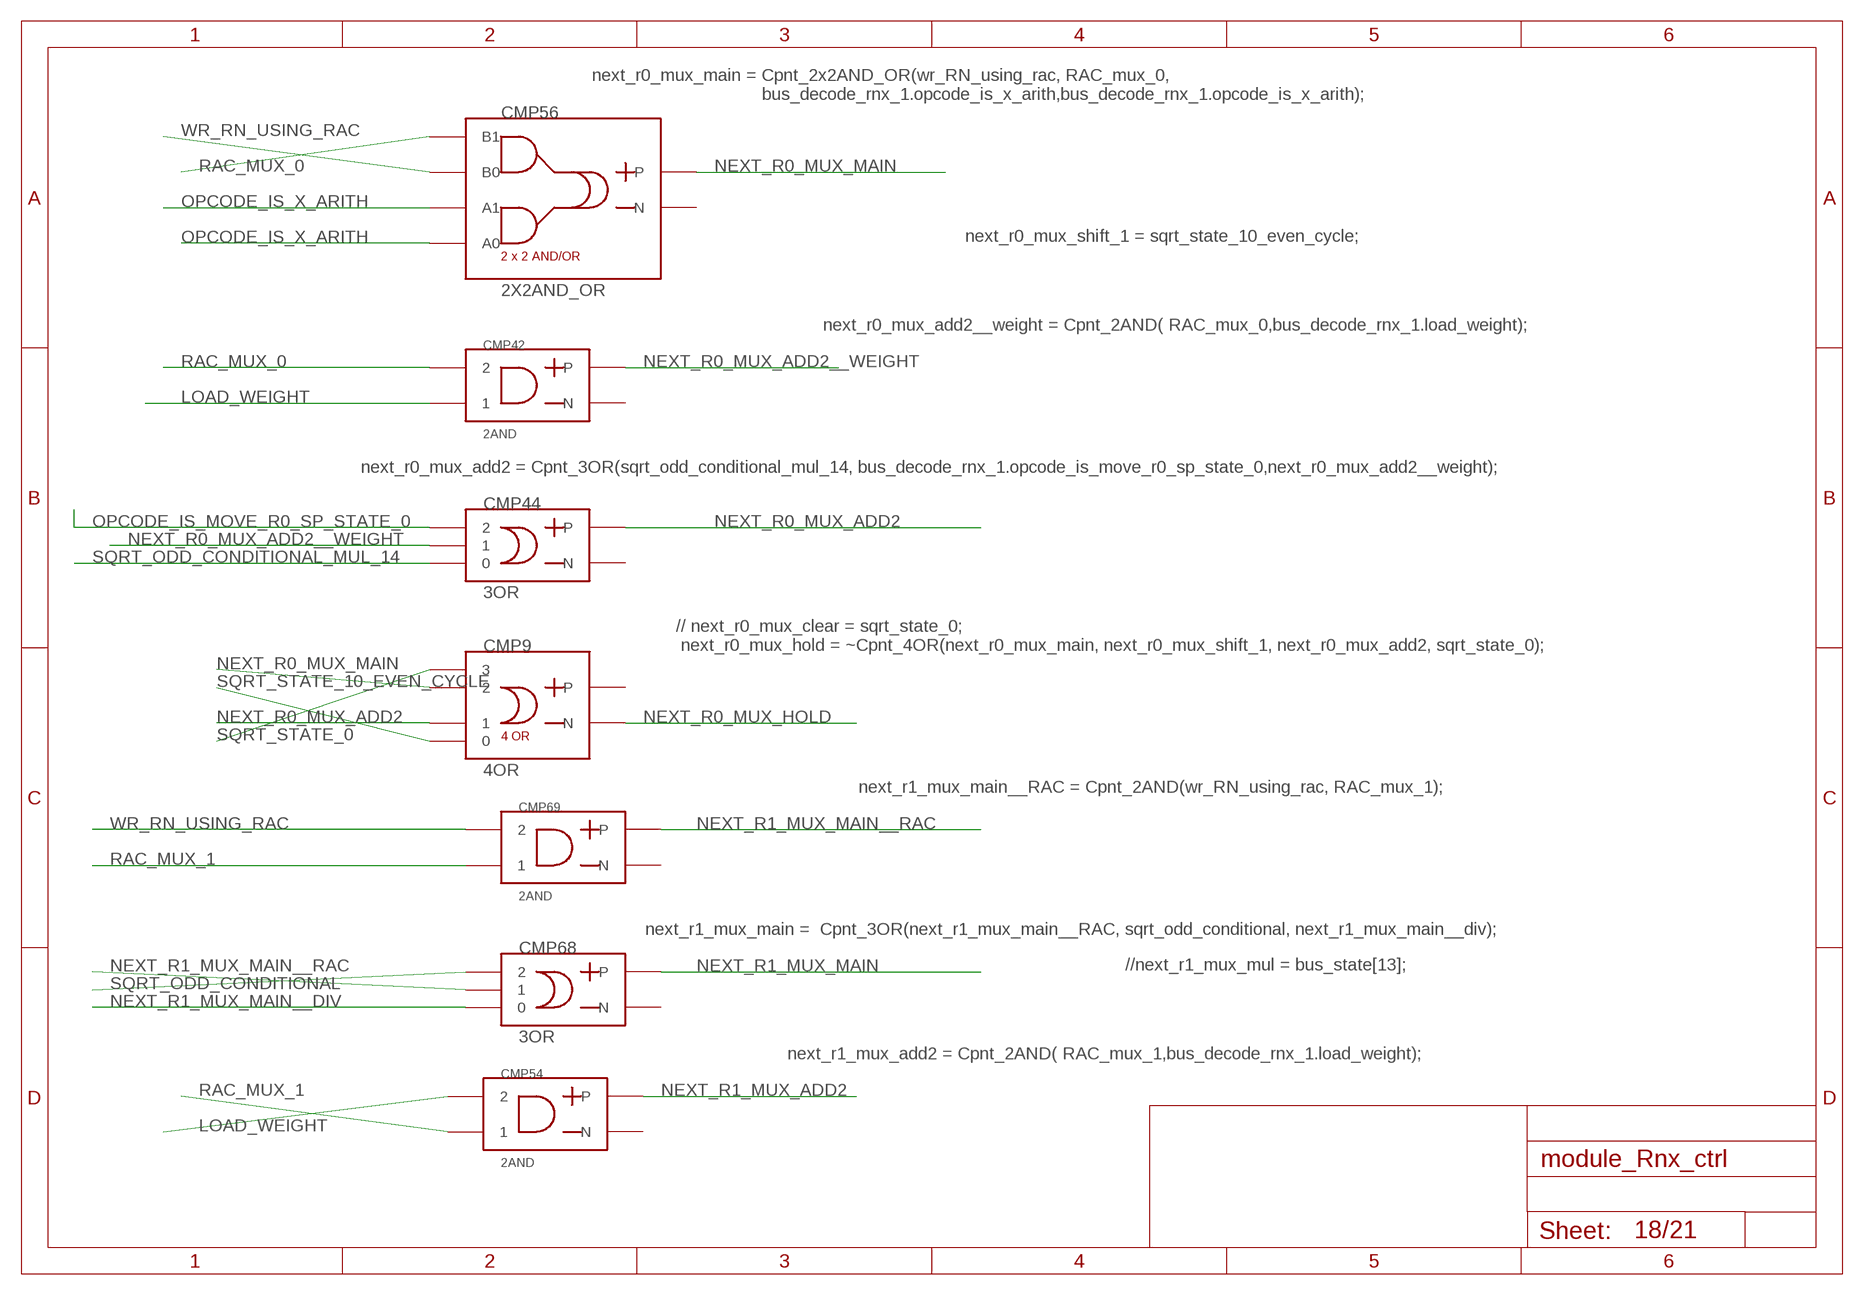
[diagram p17: schematic, sheet 18]
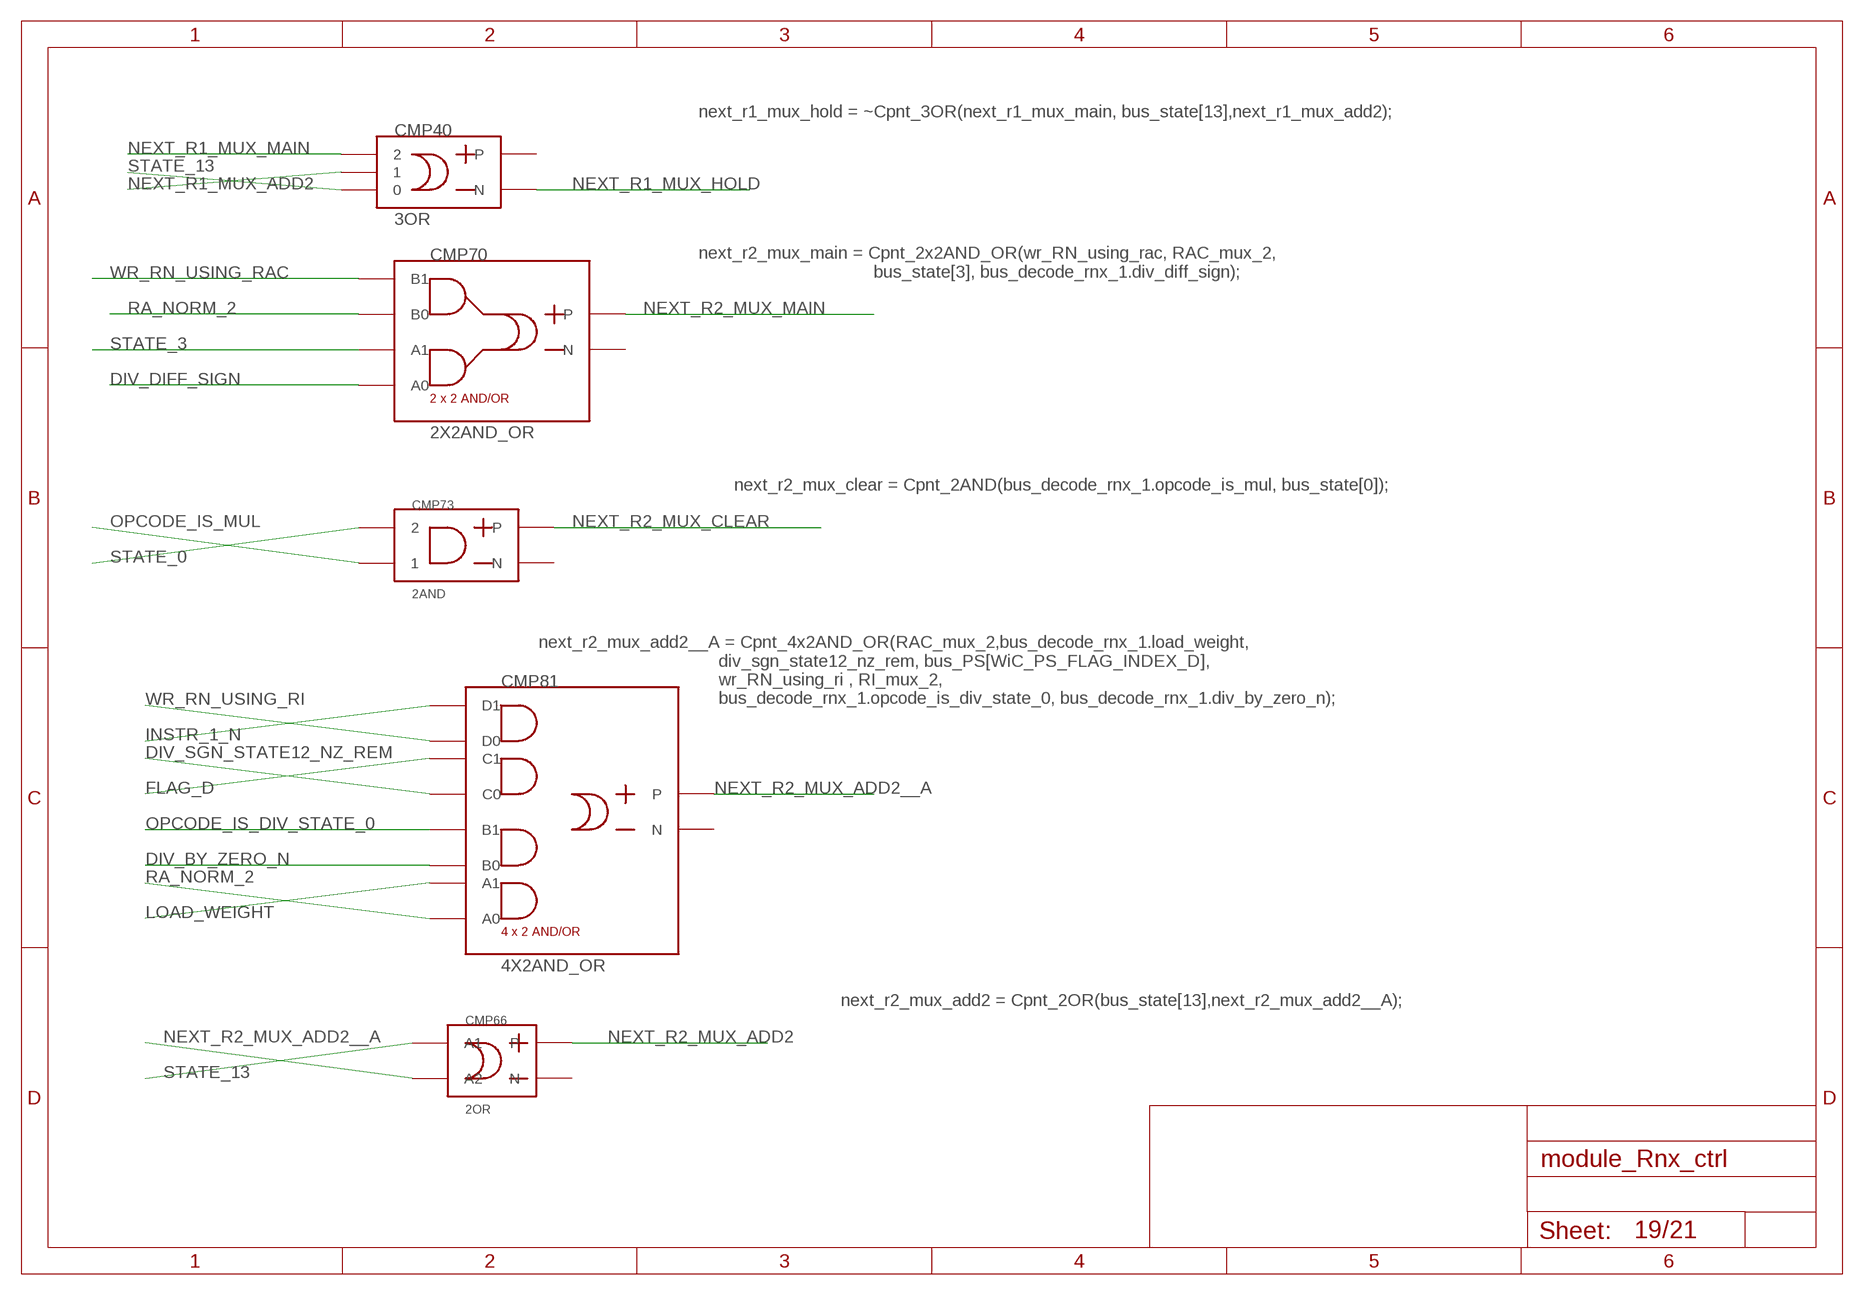
[diagram p18: schematic, sheet 19]
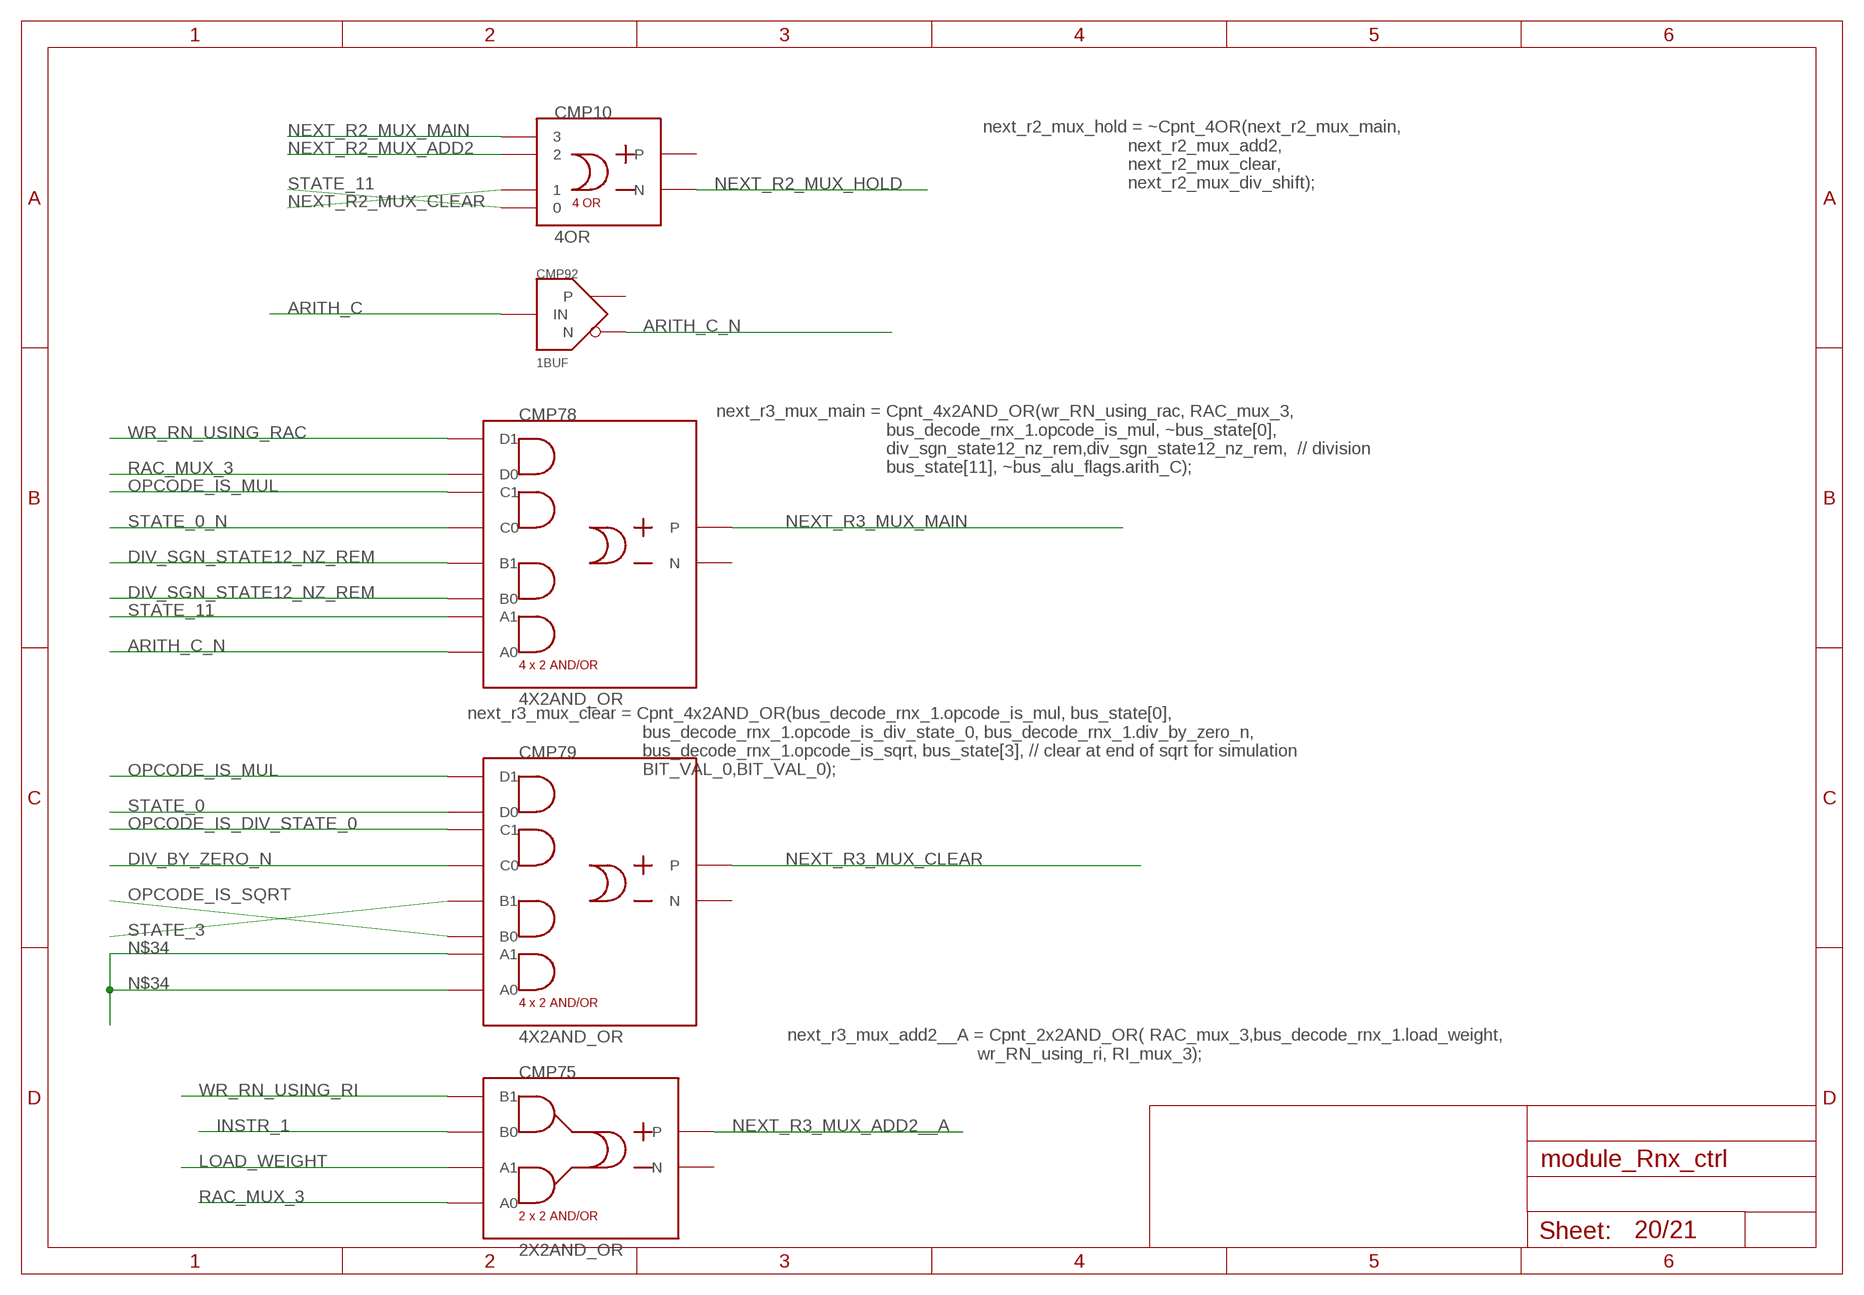
[diagram p19: schematic, sheet 20]
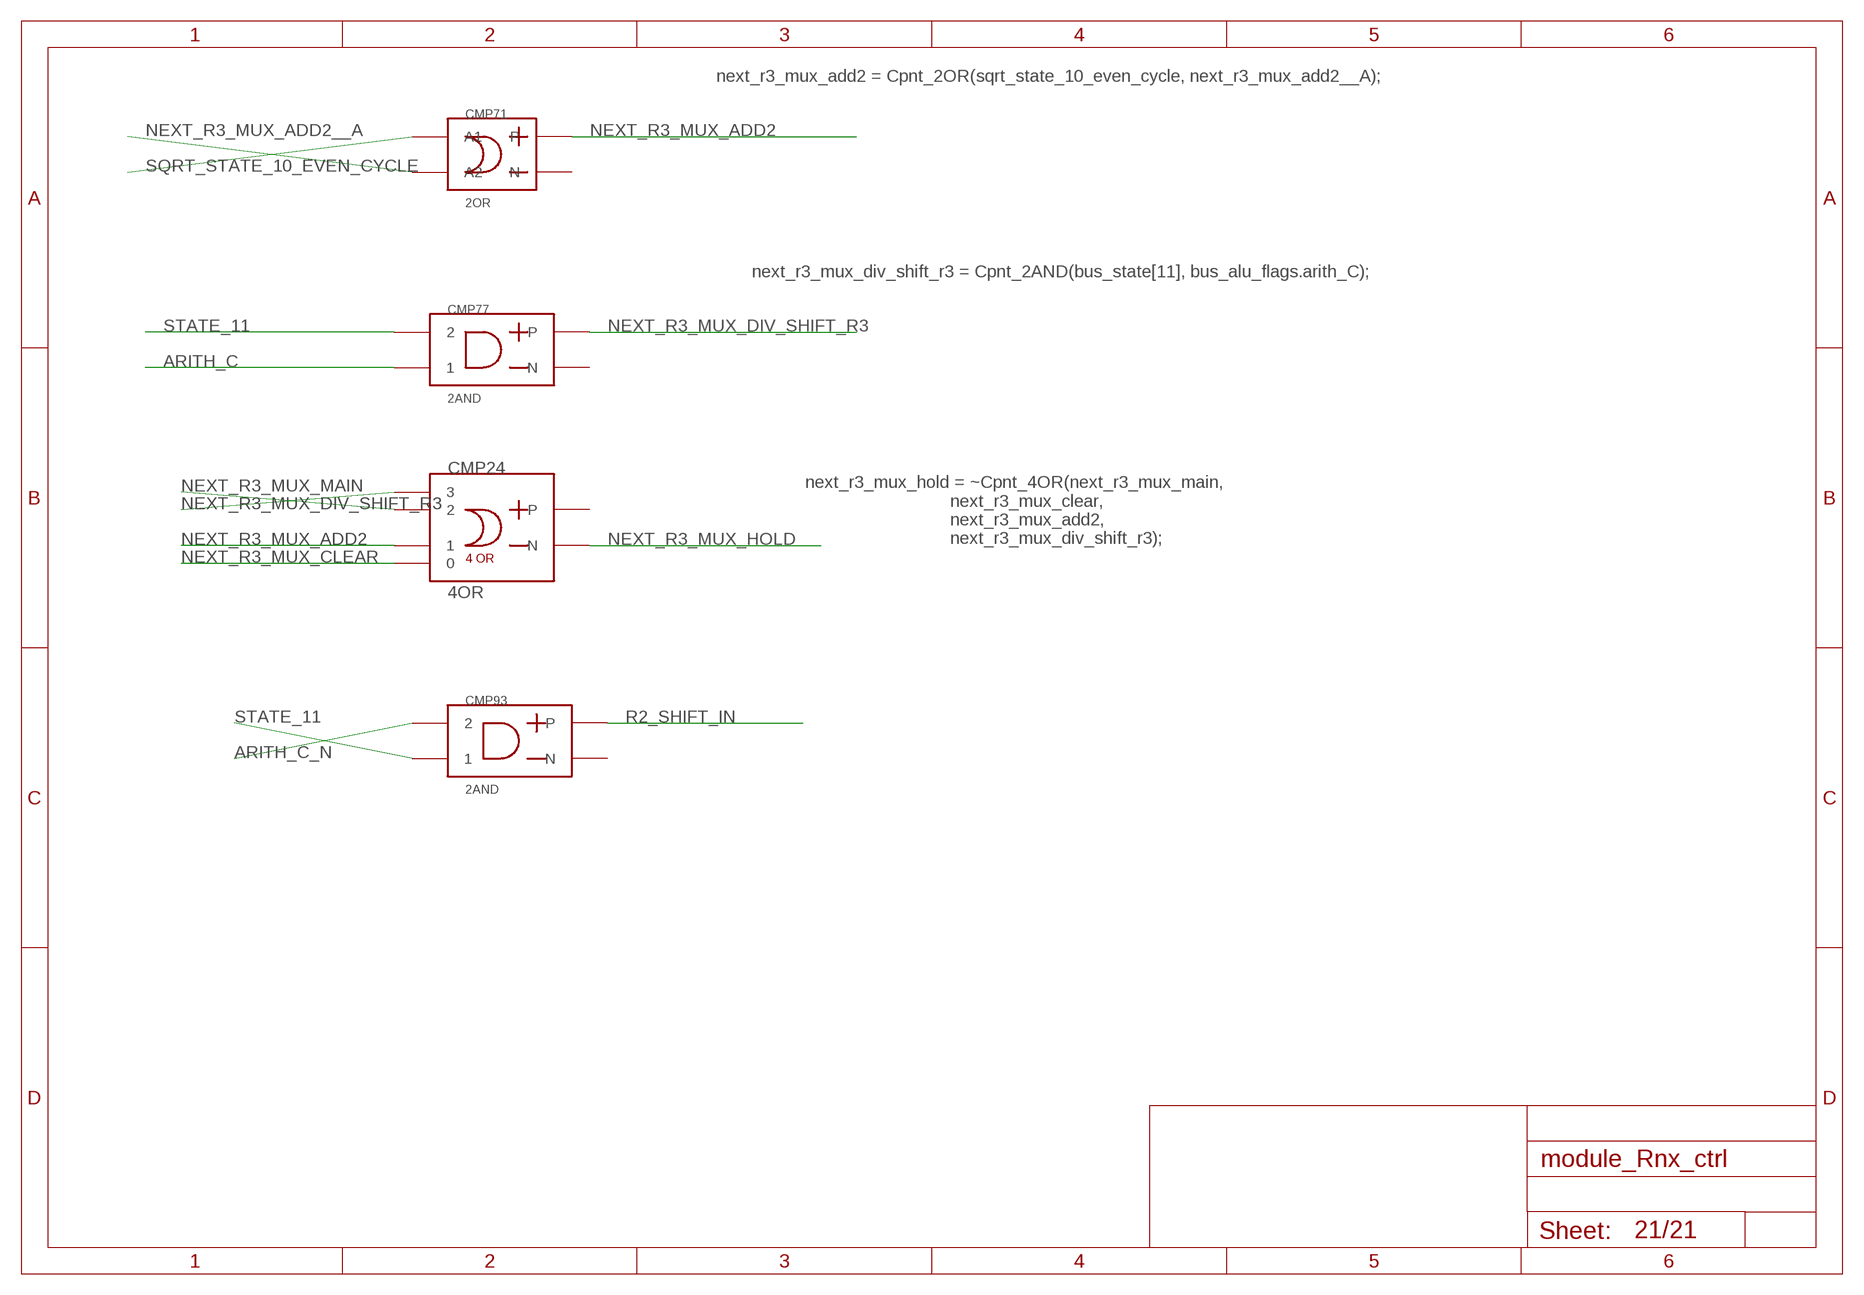
[diagram p20: schematic, sheet 21]

(export (version "E")
  (design (tool "Eeschema 10.0.6"))
  (components
    (comp (ref "CMP5")
      (value "2X2AND_OR")
      (footprint "eagle-import:2X2AND_OR")
      (libsource (lib "eagle-import") (part "2X2AND_OR"))
    )
    (comp (ref "CMP13")
      (value "5OR")
      (footprint "eagle-import:5OR")
      (libsource (lib "eagle-import") (part "5OR"))
    )
    (comp (ref "CMP15")
      (value "2OR")
      (footprint "eagle-import:2OR")
      (libsource (lib "eagle-import") (part "2OR"))
    )
    (comp (ref "CMP16")
      (value "2AND")
      (footprint "eagle-import:2AND")
      (libsource (lib "eagle-import") (part "2AND"))
    )
    (comp (ref "CMP17")
      (value "2AND")
      (footprint "eagle-import:2AND")
      (libsource (lib "eagle-import") (part "2AND"))
    )
    (comp (ref "CMP46")
      (value "2AND")
      (footprint "eagle-import:2AND")
      (libsource (lib "eagle-import") (part "2AND"))
    )
    (comp (ref "CMP50")
      (value "2X3AND_OR")
      (footprint "eagle-import:2X3AND_OR")
      (libsource (lib "eagle-import") (part "2X3AND_OR"))
    )
    (comp (ref "CMP83")
      (value "1BUF")
      (footprint "eagle-import:1BUF")
      (libsource (lib "eagle-import") (part "1BUF"))
    )
    (comp (ref "CMP2")
      (value "2X2AND_OR")
      (footprint "eagle-import:2X2AND_OR")
      (libsource (lib "eagle-import") (part "2X2AND_OR"))
    )
    (comp (ref "CMP3")
      (value "4OR")
      (footprint "eagle-import:4OR")
      (libsource (lib "eagle-import") (part "4OR"))
    )
    (comp (ref "CMP4")
      (value "4OR")
      (footprint "eagle-import:4OR")
      (libsource (lib "eagle-import") (part "4OR"))
    )
    (comp (ref "CMP6")
      (value "2OR")
      (footprint "eagle-import:2OR")
      (libsource (lib "eagle-import") (part "2OR"))
    )
    (comp (ref "CMP7")
      (value "2OR")
      (footprint "eagle-import:2OR")
      (libsource (lib "eagle-import") (part "2OR"))
    )
    (comp (ref "CMP63")
      (value "2OR")
      (footprint "eagle-import:2OR")
      (libsource (lib "eagle-import") (part "2OR"))
    )
    (comp (ref "CMP72")
      (value "3AND")
      (footprint "eagle-import:3AND")
      (libsource (lib "eagle-import") (part "3AND"))
    )
    (comp (ref "CMP74")
      (value "2OR")
      (footprint "eagle-import:2OR")
      (libsource (lib "eagle-import") (part "2OR"))
    )
    (comp (ref "CMP91")
      (value "1BUF")
      (footprint "eagle-import:1BUF")
      (libsource (lib "eagle-import") (part "1BUF"))
    )
    (comp (ref "CMP55")
      (value "1BUF")
      (footprint "eagle-import:1BUF")
      (libsource (lib "eagle-import") (part "1BUF"))
    )
    (comp (ref "CMP58")
      (value "2X2AND_OR")
      (footprint "eagle-import:2X2AND_OR")
      (libsource (lib "eagle-import") (part "2X2AND_OR"))
    )
    (comp (ref "CMP59")
      (value "2X2AND_OR")
      (footprint "eagle-import:2X2AND_OR")
      (libsource (lib "eagle-import") (part "2X2AND_OR"))
    )
    (comp (ref "CMP60")
      (value "4AND")
      (footprint "eagle-import:4AND")
      (libsource (lib "eagle-import") (part "4AND"))
    )
    (comp (ref "CMP61")
      (value "5OR")
      (footprint "eagle-import:5OR")
      (libsource (lib "eagle-import") (part "5OR"))
    )
    (comp (ref "CMP85")
      (value "3AND")
      (footprint "eagle-import:3AND")
      (libsource (lib "eagle-import") (part "3AND"))
    )
    (comp (ref "CMP86")
      (value "BUS_SPLIT_DISPLAY")
      (footprint "eagle-import:BUS_SPLIT_DISPLAY")
      (libsource (lib "eagle-import") (part "BUS_SPLIT_DISPLAY"))
    )
    (comp (ref "CMP97")
      (value "BUS_SPLIT_DISPLAY")
      (footprint "eagle-import:BUS_SPLIT_DISPLAY")
      (libsource (lib "eagle-import") (part "BUS_SPLIT_DISPLAY"))
    )
    (comp (ref "CMP52")
      (value "BUS_CONSTRUCT_DISPLAY")
      (footprint "eagle-import:BUS_SPLIT_DISPLAY")
      (libsource (lib "eagle-import") (part "BUS_CONSTRUCT_DISPLAY"))
    )
    (comp (ref "CMP25")
      (value "BUS_CONSTRUCT_DISPLAY")
      (footprint "eagle-import:BUS_SPLIT_DISPLAY")
      (libsource (lib "eagle-import") (part "BUS_CONSTRUCT_DISPLAY"))
    )
    (comp (ref "CMP89")
      (value "BUS_CONSTRUCT_DISPLAY")
      (footprint "eagle-import:BUS_SPLIT_DISPLAY")
      (libsource (lib "eagle-import") (part "BUS_CONSTRUCT_DISPLAY"))
    )
    (comp (ref "CMP99")
      (value "BUS_CONSTRUCT_DISPLAY")
      (footprint "eagle-import:BUS_SPLIT_DISPLAY")
      (libsource (lib "eagle-import") (part "BUS_CONSTRUCT_DISPLAY"))
    )
    (comp (ref "CMP26")
      (value "2OR")
      (footprint "eagle-import:2OR")
      (libsource (lib "eagle-import") (part "2OR"))
    )
    (comp (ref "CMP27")
      (value "2OR")
      (footprint "eagle-import:2OR")
      (libsource (lib "eagle-import") (part "2OR"))
    )
    (comp (ref "CMP28")
      (value "3AND")
      (footprint "eagle-import:3AND")
      (libsource (lib "eagle-import") (part "3AND"))
    )
    (comp (ref "CMP29")
      (value "3OR")
      (footprint "eagle-import:3OR")
      (libsource (lib "eagle-import") (part "3OR"))
    )
    (comp (ref "CMP30")
      (value "3OR")
      (footprint "eagle-import:3OR")
      (libsource (lib "eagle-import") (part "3OR"))
    )
    (comp (ref "CMP48")
      (value "1BUF")
      (footprint "eagle-import:1BUF")
      (libsource (lib "eagle-import") (part "1BUF"))
    )
    (comp (ref "CMP49")
      (value "1BUF")
      (footprint "eagle-import:1BUF")
      (libsource (lib "eagle-import") (part "1BUF"))
    )
    (comp (ref "CMP10")
      (value "4OR")
      (footprint "eagle-import:4OR")
      (libsource (lib "eagle-import") (part "4OR"))
    )
    (comp (ref "CMP75")
      (value "2X2AND_OR")
      (footprint "eagle-import:2X2AND_OR")
      (libsource (lib "eagle-import") (part "2X2AND_OR"))
    )
    (comp (ref "CMP78")
      (value "4X2AND_OR")
      (footprint "eagle-import:4X2AND_OR")
      (libsource (lib "eagle-import") (part "4X2AND_OR"))
    )
    (comp (ref "CMP79")
      (value "4X2AND_OR")
      (footprint "eagle-import:4X2AND_OR")
      (libsource (lib "eagle-import") (part "4X2AND_OR"))
    )
    (comp (ref "CMP92")
      (value "1BUF")
      (footprint "eagle-import:1BUF")
      (libsource (lib "eagle-import") (part "1BUF"))
    )
    (comp (ref "CMP20")
      (value "2X2AND_OR")
      (footprint "eagle-import:2X2AND_OR")
      (libsource (lib "eagle-import") (part "2X2AND_OR"))
    )
    (comp (ref "CMP22")
      (value "2AND")
      (footprint "eagle-import:2AND")
      (libsource (lib "eagle-import") (part "2AND"))
    )
    (comp (ref "CMP80")
      (value "2X2AND_OR")
      (footprint "eagle-import:2X2AND_OR")
      (libsource (lib "eagle-import") (part "2X2AND_OR"))
    )
    (comp (ref "CMP82")
      (value "5OR")
      (footprint "eagle-import:5OR")
      (libsource (lib "eagle-import") (part "5OR"))
    )
    (comp (ref "CMP21")
      (value "2AND")
      (footprint "eagle-import:2AND")
      (libsource (lib "eagle-import") (part "2AND"))
    )
    (comp (ref "CMP23")
      (value "2AND")
      (footprint "eagle-import:2AND")
      (libsource (lib "eagle-import") (part "2AND"))
    )
    (comp (ref "CMP31")
      (value "1BUF")
      (footprint "eagle-import:1BUF")
      (libsource (lib "eagle-import") (part "1BUF"))
    )
    (comp (ref "CMP47")
      (value "2OR")
      (footprint "eagle-import:2OR")
      (libsource (lib "eagle-import") (part "2OR"))
    )
    (comp (ref "CMP53")
      (value "3AND")
      (footprint "eagle-import:3AND")
      (libsource (lib "eagle-import") (part "3AND"))
    )
    (comp (ref "CMP90")
      (value "1BUF")
      (footprint "eagle-import:1BUF")
      (libsource (lib "eagle-import") (part "1BUF"))
    )
    (comp (ref "CMP1")
      (value "2OR")
      (footprint "eagle-import:2OR")
      (libsource (lib "eagle-import") (part "2OR"))
    )
    (comp (ref "CMP41")
      (value "2OR")
      (footprint "eagle-import:2OR")
      (libsource (lib "eagle-import") (part "2OR"))
    )
    (comp (ref "CMP43")
      (value "3OR")
      (footprint "eagle-import:3OR")
      (libsource (lib "eagle-import") (part "3OR"))
    )
    (comp (ref "CMP45")
      (value "2X2AND_OR")
      (footprint "eagle-import:2X2AND_OR")
      (libsource (lib "eagle-import") (part "2X2AND_OR"))
    )
    (comp (ref "CMP62")
      (value "2OR")
      (footprint "eagle-import:2OR")
      (libsource (lib "eagle-import") (part "2OR"))
    )
    (comp (ref "CMP64")
      (value "2X2AND_OR")
      (footprint "eagle-import:2X2AND_OR")
      (libsource (lib "eagle-import") (part "2X2AND_OR"))
    )
    (comp (ref "CMP8")
      (value "3OR")
      (footprint "eagle-import:3OR")
      (libsource (lib "eagle-import") (part "3OR"))
    )
    (comp (ref "CMP12")
      (value "3OR")
      (footprint "eagle-import:3OR")
      (libsource (lib "eagle-import") (part "3OR"))
    )
    (comp (ref "CMP14")
      (value "3OR")
      (footprint "eagle-import:3OR")
      (libsource (lib "eagle-import") (part "3OR"))
    )
    (comp (ref "CMP19")
      (value "3OR")
      (footprint "eagle-import:3OR")
      (libsource (lib "eagle-import") (part "3OR"))
    )
    (comp (ref "CMP18")
      (value "BUS_SPLIT_DISPLAY")
      (footprint "eagle-import:BUS_SPLIT_DISPLAY")
      (libsource (lib "eagle-import") (part "BUS_SPLIT_DISPLAY"))
    )
    (comp (ref "CMP87")
      (value "BUS_SPLIT_DISPLAY")
      (footprint "eagle-import:BUS_SPLIT_DISPLAY")
      (libsource (lib "eagle-import") (part "BUS_SPLIT_DISPLAY"))
    )
    (comp (ref "CMP96")
      (value "BUS_SPLIT_DISPLAY")
      (footprint "eagle-import:BUS_SPLIT_DISPLAY")
      (libsource (lib "eagle-import") (part "BUS_SPLIT_DISPLAY"))
    )
    (comp (ref "CMP9")
      (value "4OR")
      (footprint "eagle-import:4OR")
      (libsource (lib "eagle-import") (part "4OR"))
    )
    (comp (ref "CMP42")
      (value "2AND")
      (footprint "eagle-import:2AND")
      (libsource (lib "eagle-import") (part "2AND"))
    )
    (comp (ref "CMP44")
      (value "3OR")
      (footprint "eagle-import:3OR")
      (libsource (lib "eagle-import") (part "3OR"))
    )
    (comp (ref "CMP54")
      (value "2AND")
      (footprint "eagle-import:2AND")
      (libsource (lib "eagle-import") (part "2AND"))
    )
    (comp (ref "CMP56")
      (value "2X2AND_OR")
      (footprint "eagle-import:2X2AND_OR")
      (libsource (lib "eagle-import") (part "2X2AND_OR"))
    )
    (comp (ref "CMP68")
      (value "3OR")
      (footprint "eagle-import:3OR")
      (libsource (lib "eagle-import") (part "3OR"))
    )
    (comp (ref "CMP69")
      (value "2AND")
      (footprint "eagle-import:2AND")
      (libsource (lib "eagle-import") (part "2AND"))
    )
    (comp (ref "CMP40")
      (value "3OR")
      (footprint "eagle-import:3OR")
      (libsource (lib "eagle-import") (part "3OR"))
    )
    (comp (ref "CMP66")
      (value "2OR")
      (footprint "eagle-import:2OR")
      (libsource (lib "eagle-import") (part "2OR"))
    )
    (comp (ref "CMP70")
      (value "2X2AND_OR")
      (footprint "eagle-import:2X2AND_OR")
      (libsource (lib "eagle-import") (part "2X2AND_OR"))
    )
    (comp (ref "CMP73")
      (value "2AND")
      (footprint "eagle-import:2AND")
      (libsource (lib "eagle-import") (part "2AND"))
    )
    (comp (ref "CMP81")
      (value "4X2AND_OR")
      (footprint "eagle-import:4X2AND_OR")
      (libsource (lib "eagle-import") (part "4X2AND_OR"))
    )
    (comp (ref "CMP67")
      (value "2AND")
      (footprint "eagle-import:2AND")
      (libsource (lib "eagle-import") (part "2AND"))
    )
    (comp (ref "CMP76")
      (value "2AND")
      (footprint "eagle-import:2AND")
      (libsource (lib "eagle-import") (part "2AND"))
    )
    (comp (ref "CMP84")
      (value "2AND")
      (footprint "eagle-import:2AND")
      (libsource (lib "eagle-import") (part "2AND"))
    )
    (comp (ref "CMP38")
      (value "DECODER4")
      (footprint "eagle-import:DECODER4")
      (libsource (lib "eagle-import") (part "DECODER4"))
    )
    (comp (ref "CMP39")
      (value "DECODER4")
      (footprint "eagle-import:DECODER4")
      (libsource (lib "eagle-import") (part "DECODER4"))
    )
    (comp (ref "CMP51")
      (value "DECODER4")
      (footprint "eagle-import:DECODER4")
      (libsource (lib "eagle-import") (part "DECODER4"))
    )
    (comp (ref "CMP88")
      (value "DECODER4")
      (footprint "eagle-import:DECODER4")
      (libsource (lib "eagle-import") (part "DECODER4"))
    )
    (comp (ref "CMP24")
      (value "4OR")
      (footprint "eagle-import:4OR")
      (libsource (lib "eagle-import") (part "4OR"))
    )
    (comp (ref "CMP71")
      (value "2OR")
      (footprint "eagle-import:2OR")
      (libsource (lib "eagle-import") (part "2OR"))
    )
    (comp (ref "CMP77")
      (value "2AND")
      (footprint "eagle-import:2AND")
      (libsource (lib "eagle-import") (part "2AND"))
    )
    (comp (ref "CMP93")
      (value "2AND")
      (footprint "eagle-import:2AND")
      (libsource (lib "eagle-import") (part "2AND"))
    )
    (comp (ref "CMP32")
      (value "2OR")
      (footprint "eagle-import:2OR")
      (libsource (lib "eagle-import") (part "2OR"))
    )
    (comp (ref "CMP33")
      (value "2AND")
      (footprint "eagle-import:2AND")
      (libsource (lib "eagle-import") (part "2AND"))
    )
    (comp (ref "CMP34")
      (value "2AND")
      (footprint "eagle-import:2AND")
      (libsource (lib "eagle-import") (part "2AND"))
    )
    (comp (ref "CMP35")
      (value "3OR")
      (footprint "eagle-import:3OR")
      (libsource (lib "eagle-import") (part "3OR"))
    )
    (comp (ref "CMP36")
      (value "3OR")
      (footprint "eagle-import:3OR")
      (libsource (lib "eagle-import") (part "3OR"))
    )
    (comp (ref "CMP37")
      (value "2OR")
      (footprint "eagle-import:2OR")
      (libsource (lib "eagle-import") (part "2OR"))
    )
    (comp (ref "CMP11")
      (value "BUS_SPLIT_DISPLAY")
      (footprint "eagle-import:BUS_SPLIT_DISPLAY")
      (libsource (lib "eagle-import") (part "BUS_SPLIT_DISPLAY"))
    )
    (comp (ref "CMP57")
      (value "BUS_SPLIT_DISPLAY")
      (footprint "eagle-import:BUS_SPLIT_DISPLAY")
      (libsource (lib "eagle-import") (part "BUS_SPLIT_DISPLAY"))
    )
    (comp (ref "CMP65")
      (value "BUS_SPLIT_DISPLAY")
      (footprint "eagle-import:BUS_SPLIT_DISPLAY")
      (libsource (lib "eagle-import") (part "BUS_SPLIT_DISPLAY"))
    )
  )
  (nets
    (net (code "1") (name "ADD1_RESULT_IS_N") (class "Default")
      (node (ref "CMP91") (pin "IN") (pinfunction "IN_IN") (pintype "input"))
      (node (ref "CMP97") (pin "P$3") (pinfunction "OUT_2_P$3") (pintype "output"))
    )
    (net (code "2") (name "ADD1_RESULT_IS_P") (class "Default")
      (node (ref "CMP63") (pin "P$1") (pinfunction "A2_P$1") (pintype "input"))
      (node (ref "CMP91") (pin "N") (pinfunction "N_N") (pintype "output"))
    )
    (net (code "3") (name "ADD2_X_MUX_RI_SP__STACK_SET_A") (class "Default")
      (node (ref "CMP59") (pin "OUT_P") (pinfunction "P_OUT_P") (pintype "output"))
    )
    (net (code "4") (name "ADD2_X_MUX_RI_SP__STACK_SET_A_N") (class "Default")
      (node (ref "CMP59") (pin "OUT_M") (pinfunction "N_OUT_M") (pintype "output"))
      (node (ref "CMP60") (pin "P$4") (pinfunction "3_P$4") (pintype "input"))
    )
    (net (code "5") (name "ADD2_X_MUX_RI__H") (class "Default")
      (node (ref "CMP41") (pin "P$1") (pinfunction "A2_P$1") (pintype "input"))
      (node (ref "CMP52") (pin "P$1") (pinfunction "IN_0_P$1") (pintype "input"))
      (node (ref "CMP85") (pin "OUT_P") (pinfunction "P_OUT_P") (pintype "output"))
    )
    (net (code "6") (name "ADD2_X_MUX_RI__SP") (class "Default")
      (node (ref "CMP25") (pin "P$8") (pinfunction "IN_7_P$8") (pintype "input"))
      (node (ref "CMP43") (pin "P$1") (pinfunction "0_P$1") (pintype "input"))
      (node (ref "CMP52") (pin "P$3") (pinfunction "IN_2_P$3") (pintype "input"))
      (node (ref "CMP61") (pin "OUT_P") (pinfunction "P_OUT_P") (pintype "output"))
    )
    (net (code "7") (name "ADD2_X_MUX_RI__SP__JSR_ABS") (class "Default")
      (node (ref "CMP52") (pin "P$2") (pinfunction "IN_1_P$2") (pintype "input"))
      (node (ref "CMP58") (pin "OUT_P") (pinfunction "P_OUT_P") (pintype "output"))
      (node (ref "CMP61") (pin "4") (pinfunction "3_4") (pintype "input"))
    )
    (net (code "8") (name "ADD2_X_MUX_RI__SP__STACK") (class "Default")
      (node (ref "CMP60") (pin "OUT_P") (pinfunction "P_OUT_P") (pintype "output"))
      (node (ref "CMP61") (pin "5") (pinfunction "4_5") (pintype "input"))
    )
    (net (code "9") (name "ADDER_X_MUX_R0") (class "Default")
      (node (ref "CMP26") (pin "OUT_P") (pinfunction "P_OUT_P") (pintype "output"))
      (node (ref "CMP30") (pin "P$1") (pinfunction "0_P$1") (pintype "input"))
      (node (ref "CMP35") (pin "P$1") (pinfunction "0_P$1") (pintype "input"))
    )
    (net (code "10") (name "ADDER_X_MUX_R1") (class "Default")
      (node (ref "CMP27") (pin "OUT_P") (pinfunction "P_OUT_P") (pintype "output"))
      (node (ref "CMP30") (pin "P$2") (pinfunction "1_P$2") (pintype "input"))
      (node (ref "CMP36") (pin "P$1") (pinfunction "0_P$1") (pintype "input"))
    )
    (net (code "11") (name "ADDER_X_MUX_R1__DIV") (class "Default")
      (node (ref "CMP27") (pin "P$1") (pinfunction "A2_P$1") (pintype "input"))
      (node (ref "CMP67") (pin "OUT_P") (pinfunction "P_OUT_P") (pintype "output"))
    )
    (net (code "12") (name "ADDER_X_MUX_R3") (class "Default")
      (node (ref "CMP29") (pin "OUT_P") (pinfunction "P_OUT_P") (pintype "output"))
      (node (ref "CMP30") (pin "P$3") (pinfunction "2_P$3") (pintype "input"))
      (node (ref "CMP37") (pin "P$1") (pinfunction "A2_P$1") (pintype "input"))
    )
    (net (code "13") (name "ADDER_X_MUX_R3_SET_A") (class "Default")
      (node (ref "CMP28") (pin "OUT_P") (pinfunction "P_OUT_P") (pintype "output"))
      (node (ref "CMP29") (pin "P$1") (pinfunction "0_P$1") (pintype "input"))
    )
    (net (code "14") (name "ADDER_X_MUX_SPECIAL") (class "Default")
      (node (ref "CMP30") (pin "OUT_P") (pinfunction "P_OUT_P") (pintype "output"))
      (node (ref "CMP32") (pin "P$1") (pinfunction "A2_P$1") (pintype "input"))
      (node (ref "CMP52") (pin "P$5") (pinfunction "IN_4_P$5") (pintype "input"))
    )
    (net (code "15") (name "ADDER_X_MUX_SPECIAL_N") (class "Default")
      (node (ref "CMP30") (pin "OUT_M") (pinfunction "N_OUT_M") (pintype "output"))
    )
    (net (code "16") (name "ADDER_Y_MUX_R0") (class "Default")
      (node (ref "CMP2") (pin "OUT_P") (pinfunction "P_OUT_P") (pintype "output"))
      (node (ref "CMP4") (pin "4") (pinfunction "3_4") (pintype "input"))
      (node (ref "CMP8") (pin "P$3") (pinfunction "2_P$3") (pintype "input"))
    )
    (net (code "17") (name "ADDER_Y_MUX_R1") (class "Default")
      (node (ref "CMP12") (pin "P$2") (pinfunction "1_P$2") (pintype "input"))
      (node (ref "CMP3") (pin "OUT_P") (pinfunction "P_OUT_P") (pintype "output"))
      (node (ref "CMP4") (pin "2") (pinfunction "1_2") (pintype "input"))
    )
    (net (code "18") (name "ADDER_Y_MUX_R2__DIV") (class "Default")
      (node (ref "CMP14") (pin "P$1") (pinfunction "0_P$1") (pintype "input"))
      (node (ref "CMP4") (pin "1") (pinfunction "0_1") (pintype "input"))
      (node (ref "CMP76") (pin "OUT_P") (pinfunction "P_OUT_P") (pintype "output"))
    )
    (net (code "19") (name "ADDER_Y_MUX_R3") (class "Default")
      (node (ref "CMP19") (pin "P$1") (pinfunction "0_P$1") (pintype "input"))
      (node (ref "CMP4") (pin "3") (pinfunction "2_3") (pintype "input"))
      (node (ref "CMP6") (pin "OUT_P") (pinfunction "P_OUT_P") (pintype "output"))
    )
    (net (code "20") (name "ADDER_Y_MUX_SPECIAL") (class "Default")
      (node (ref "CMP4") (pin "OUT_P") (pinfunction "P_OUT_P") (pintype "output"))
      (node (ref "CMP52") (pin "P$6") (pinfunction "IN_5_P$6") (pintype "input"))
      (node (ref "CMP7") (pin "P$1") (pinfunction "A2_P$1") (pintype "input"))
    )
    (net (code "21") (name "ADDER_Y_MUX_SPECIAL_N") (class "Default")
      (node (ref "CMP4") (pin "OUT_M") (pinfunction "N_OUT_M") (pintype "output"))
    )
    (net (code "22") (name "ALL_POPS") (class "Default")
      (node (ref "CMP57") (pin "P$1") (pinfunction "OUT_0_P$1") (pintype "output"))
      (node (ref "CMP64") (pin "P$2") (pinfunction "A1_P$2") (pintype "input"))
    )
    (net (code "23") (name "ARITH_C") (class "Default")
      (node (ref "CMP77") (pin "P$1") (pinfunction "1_P$1") (pintype "input"))
      (node (ref "CMP92") (pin "IN") (pinfunction "IN_IN") (pintype "input"))
      (node (ref "CMP97") (pin "P$2") (pinfunction "OUT_1_P$2") (pintype "output"))
    )
    (net (code "24") (name "ARITH_C_N") (class "Default")
      (node (ref "CMP78") (pin "P$1") (pinfunction "A0_P$1") (pintype "input"))
      (node (ref "CMP92") (pin "N") (pinfunction "N_N") (pintype "output"))
      (node (ref "CMP93") (pin "P$2") (pinfunction "2_P$2") (pintype "input"))
    )
    (net (code "25") (name "ARITH_V") (class "Default")
      (node (ref "CMP97") (pin "P$1") (pinfunction "OUT_0_P$1") (pintype "output"))
    )
    (net (code "26") (name "BIT_TEST_RESULT") (class "Default")
      (node (ref "CMP97") (pin "P$5") (pinfunction "OUT_4_P$5") (pintype "output"))
    )
    (net (code "27") (name "BUS_ALU_FLAGS") (class "Default")
      (node (ref "CMP97") (pin "INPUT") (pinfunction "INPUT_INPUT") (pintype "input"))
    )
    (net (code "28") (name "BUS_DECODE_RNX_1") (class "Default")
      (node (ref "CMP57") (pin "INPUT") (pinfunction "INPUT_INPUT") (pintype "input"))
    )
    (net (code "30") (name "BUS_INSTR") (class "Default")
      (node (ref "CMP11") (pin "INPUT") (pinfunction "INPUT_INPUT") (pintype "input"))
    )
    (net (code "31") (name "BUS_PS") (class "Default")
      (node (ref "CMP87") (pin "INPUT") (pinfunction "INPUT_INPUT") (pintype "input"))
    )
    (net (code "32") (name "BUS_RN_ARITH_FLAGS") (class "Default")
      (node (ref "CMP86") (pin "INPUT") (pinfunction "INPUT_INPUT") (pintype "input"))
    )
    (net (code "33") (name "BUS_RX_MUX_CTRL") (class "Default")
      (node (ref "CMP25") (pin "INPUT") (pinfunction "OUT_INPUT") (pintype "output"))
    )
    (net (code "34") (name "BUS_STATE") (class "Default")
      (node (ref "CMP18") (pin "INPUT") (pinfunction "INPUT_INPUT") (pintype "input"))
    )
    (net (code "35") (name "DIR_SZ_IS_LOAD_BYTE") (class "Default")
      (node (ref "CMP16") (pin "P$2") (pinfunction "2_P$2") (pintype "input"))
      (node (ref "CMP88") (pin "P1") (pinfunction "P1_P1") (pintype "output"))
    )
    (net (code "36") (name "DIR_SZ_IS_LOAD_WORD") (class "Default")
      (node (ref "CMP17") (pin "P$2") (pinfunction "2_P$2") (pintype "input"))
      (node (ref "CMP88") (pin "P0") (pinfunction "P0_P0") (pintype "output"))
    )
    (net (code "37") (name "DIV_BY_ZERO_N") (class "Default")
      (node (ref "CMP65") (pin "P$9") (pinfunction "OUT_8_P$9") (pintype "output"))
      (node (ref "CMP79") (pin "P$5") (pinfunction "C0_P$5") (pintype "input"))
      (node (ref "CMP81") (pin "P$3") (pinfunction "B0_P$3") (pintype "input"))
    )
    (net (code "38") (name "DIV_DIFF_SIGN") (class "Default")
      (node (ref "CMP65") (pin "P$13") (pinfunction "OUT_12_P$13") (pintype "output"))
      (node (ref "CMP70") (pin "P$1") (pinfunction "A0_P$1") (pintype "input"))
    )
    (net (code "39") (name "DIV_SGN_STATE12_NZ_REM") (class "Default")
      (node (ref "CMP53") (pin "OUT_P") (pinfunction "P_OUT_P") (pintype "output"))
      (node (ref "CMP78") (pin "P$3") (pinfunction "B0_P$3") (pintype "input"))
      (node (ref "CMP78") (pin "P$4") (pinfunction "B1_P$4") (pintype "input"))
      (node (ref "CMP81") (pin "P$5") (pinfunction "C0_P$5") (pintype "input"))
    )
    (net (code "40") (name "FLAG_C") (class "Default")
      (node (ref "CMP87") (pin "P$6") (pinfunction "OUT_5_P$6") (pintype "output"))
    )
    (net (code "41") (name "FLAG_D") (class "Default")
      (node (ref "CMP67") (pin "P$1") (pinfunction "1_P$1") (pintype "input"))
      (node (ref "CMP81") (pin "P$6") (pinfunction "C1_P$6") (pintype "input"))
      (node (ref "CMP87") (pin "P$7") (pinfunction "OUT_6_P$7") (pintype "output"))
    )
    (net (code "42") (name "FLAG_F0") (class "Default")
      (node (ref "CMP53") (pin "P$3") (pinfunction "3_P$3") (pintype "input"))
      (node (ref "CMP87") (pin "P$9") (pinfunction "OUT_8_P$9") (pintype "output"))
    )
    (net (code "43") (name "FLAG_F1") (class "Default")
      (node (ref "CMP87") (pin "P$10") (pinfunction "OUT_9_P$10") (pintype "output"))
    )
    (net (code "44") (name "FLAG_F2") (class "Default")
      (node (ref "CMP87") (pin "P$11") (pinfunction "OUT_10_P$11") (pintype "output"))
    )
    (net (code "45") (name "FLAG_F3") (class "Default")
      (node (ref "CMP87") (pin "P$12") (pinfunction "OUT_11_P$12") (pintype "output"))
    )
    (net (code "46") (name "FLAG_F4") (class "Default")
      (node (ref "CMP87") (pin "P$13") (pinfunction "OUT_12_P$13") (pintype "output"))
    )
    (net (code "47") (name "FLAG_F5") (class "Default")
      (node (ref "CMP87") (pin "P$14") (pinfunction "OUT_13_P$14") (pintype "output"))
    )
    (net (code "48") (name "FLAG_I") (class "Default")
      (node (ref "CMP87") (pin "P$1") (pinfunction "OUT_0_P$1") (pintype "output"))
    )
    (net (code "49") (name "FLAG_N") (class "Default")
      (node (ref "CMP87") (pin "P$2") (pinfunction "OUT_1_P$2") (pintype "output"))
    )
    (net (code "50") (name "FLAG_V") (class "Default")
      (node (ref "CMP87") (pin "P$4") (pinfunction "OUT_3_P$4") (pintype "output"))
    )
    (net (code "51") (name "FLAG_X") (class "Default")
      (node (ref "CMP87") (pin "P$5") (pinfunction "OUT_4_P$5") (pintype "output"))
    )
    (net (code "52") (name "FLAG_Z") (class "Default")
      (node (ref "CMP87") (pin "P$3") (pinfunction "OUT_2_P$3") (pintype "output"))
    )
    (net (code "53") (name "H_0") (class "Default")
      (node (ref "CMP31") (pin "IN") (pinfunction "IN_IN") (pintype "input"))
      (node (ref "CMP39") (pin "A0") (pinfunction "A0_A0") (pintype "input"))
      (node (ref "CMP72") (pin "P$2") (pinfunction "2_P$2") (pintype "input"))
      (node (ref "CMP96") (pin "P$1") (pinfunction "OUT_0_P$1") (pintype "output"))
    )
    (net (code "54") (name "H_0_N") (class "Default")
      (node (ref "CMP23") (pin "P$1") (pinfunction "1_P$1") (pintype "input"))
      (node (ref "CMP31") (pin "N") (pinfunction "N_N") (pintype "output"))
    )
    (net (code "55") (name "H_1") (class "Default")
      (node (ref "CMP39") (pin "A1") (pinfunction "A1_A1") (pintype "input"))
      (node (ref "CMP96") (pin "P$2") (pinfunction "OUT_1_P$2") (pintype "output"))
    )
    (net (code "56") (name "H_2") (class "Default")
      (node (ref "CMP96") (pin "P$3") (pinfunction "OUT_2_P$3") (pintype "output"))
    )
    (net (code "57") (name "H_3") (class "Default")
      (node (ref "CMP96") (pin "P$4") (pinfunction "OUT_3_P$4") (pintype "output"))
    )
    (net (code "58") (name "H_4") (class "Default")
      (node (ref "CMP96") (pin "P$5") (pinfunction "OUT_4_P$5") (pintype "output"))
    )
    (net (code "59") (name "H_5") (class "Default")
      (node (ref "CMP96") (pin "P$6") (pinfunction "OUT_5_P$6") (pintype "output"))
    )
    (net (code "60") (name "H_6") (class "Default")
      (node (ref "CMP96") (pin "P$7") (pinfunction "OUT_6_P$7") (pintype "output"))
    )
    (net (code "61") (name "H_7") (class "Default")
      (node (ref "CMP96") (pin "P$8") (pinfunction "OUT_7_P$8") (pintype "output"))
    )
    (net (code "62") (name "H_8") (class "Default")
      (node (ref "CMP96") (pin "P$9") (pinfunction "OUT_8_P$9") (pintype "output"))
    )
    (net (code "63") (name "H_9") (class "Default")
      (node (ref "CMP96") (pin "P$10") (pinfunction "OUT_9_P$10") (pintype "output"))
    )
    (net (code "64") (name "H_10") (class "Default")
      (node (ref "CMP96") (pin "P$11") (pinfunction "OUT_10_P$11") (pintype "output"))
    )
    (net (code "65") (name "H_11") (class "Default")
      (node (ref "CMP96") (pin "P$12") (pinfunction "OUT_11_P$12") (pintype "output"))
    )
    (net (code "66") (name "H_12") (class "Default")
      (node (ref "CMP96") (pin "P$13") (pinfunction "OUT_12_P$13") (pintype "output"))
    )
    (net (code "67") (name "H_13") (class "Default")
      (node (ref "CMP96") (pin "P$14") (pinfunction "OUT_13_P$14") (pintype "output"))
    )
    (net (code "68") (name "H_14") (class "Default")
      (node (ref "CMP96") (pin "P$15") (pinfunction "OUT_14_P$15") (pintype "output"))
    )
    (net (code "69") (name "H_15") (class "Default")
      (node (ref "CMP96") (pin "P$16") (pinfunction "OUT_15_P$16") (pintype "output"))
    )
    (net (code "70") (name "INSTR_0") (class "Default")
      (node (ref "CMP11") (pin "P$1") (pinfunction "OUT_0_P$1") (pintype "output"))
      (node (ref "CMP34") (pin "P$1") (pinfunction "1_P$1") (pintype "input"))
      (node (ref "CMP51") (pin "A0") (pinfunction "A0_A0") (pintype "input"))
    )
    (net (code "71") (name "INSTR_0_N") (class "Default")
      (node (ref "CMP11") (pin "P$9") (pinfunction "OUT_8_P$9") (pintype "output"))
      (node (ref "CMP33") (pin "P$1") (pinfunction "1_P$1") (pintype "input"))
    )
    (net (code "72") (name "INSTR_1") (class "Default")
      (node (ref "CMP11") (pin "P$2") (pinfunction "OUT_1_P$2") (pintype "output"))
      (node (ref "CMP46") (pin "P$1") (pinfunction "1_P$1") (pintype "input"))
      (node (ref "CMP51") (pin "A1") (pinfunction "A1_A1") (pintype "input"))
      (node (ref "CMP75") (pin "P$3") (pinfunction "B0_P$3") (pintype "input"))
    )
    (net (code "73") (name "INSTR_1_N") (class "Default")
      (node (ref "CMP11") (pin "P$10") (pinfunction "OUT_9_P$10") (pintype "output"))
      (node (ref "CMP45") (pin "P$2") (pinfunction "A1_P$2") (pintype "input"))
      (node (ref "CMP81") (pin "P$8") (pinfunction "D1_P$8") (pintype "input"))
    )
    (net (code "74") (name "INSTR_2") (class "Default")
      (node (ref "CMP11") (pin "P$3") (pinfunction "OUT_2_P$3") (pintype "output"))
      (node (ref "CMP38") (pin "A0") (pinfunction "A0_A0") (pintype "input"))
      (node (ref "CMP50") (pin "P$5") (pinfunction "B1_P$5") (pintype "input"))
      (node (ref "CMP88") (pin "A0") (pinfunction "A0_A0") (pintype "input"))
    )
    (net (code "75") (name "INSTR_2_N") (class "Default")
      (node (ref "CMP11") (pin "P$11") (pinfunction "OUT_10_P$11") (pintype "output"))
      (node (ref "CMP50") (pin "P$2") (pinfunction "A1_P$2") (pintype "input"))
    )
    (net (code "76") (name "INSTR_3") (class "Default")
      (node (ref "CMP11") (pin "P$4") (pinfunction "OUT_3_P$4") (pintype "output"))
      (node (ref "CMP38") (pin "A1") (pinfunction "A1_A1") (pintype "input"))
      (node (ref "CMP88") (pin "A1") (pinfunction "A1_A1") (pintype "input"))
    )
    (net (code "77") (name "INSTR_4") (class "Default")
      (node (ref "CMP11") (pin "P$5") (pinfunction "OUT_4_P$5") (pintype "output"))
    )
    (net (code "78") (name "INSTR_5") (class "Default")
      (node (ref "CMP11") (pin "P$6") (pinfunction "OUT_5_P$6") (pintype "output"))
    )
    (net (code "79") (name "INSTR_6") (class "Default")
      (node (ref "CMP11") (pin "P$7") (pinfunction "OUT_6_P$7") (pintype "output"))
    )
    (net (code "80") (name "INSTR_6_N") (class "Default")
      (node (ref "CMP11") (pin "P$15") (pinfunction "OUT_14_P$15") (pintype "output"))
      (node (ref "CMP85") (pin "P$3") (pinfunction "3_P$3") (pintype "input"))
    )
    (net (code "81") (name "INSTR_7") (class "Default")
      (node (ref "CMP11") (pin "P$8") (pinfunction "OUT_7_P$8") (pintype "output"))
      (node (ref "CMP85") (pin "P$2") (pinfunction "2_P$2") (pintype "input"))
    )
    (net (code "82") (name "INSTR_7_N") (class "Default")
      (node (ref "CMP11") (pin "P$16") (pinfunction "OUT_15_P$16") (pintype "output"))
      (node (ref "CMP22") (pin "P$1") (pinfunction "1_P$1") (pintype "input"))
      (node (ref "CMP5") (pin "P$4") (pinfunction "B1_P$4") (pintype "input"))
    )
    (net (code "83") (name "IS_END_N") (class "Default")
      (node (ref "CMP57") (pin "P$14") (pinfunction "OUT_13_P$14") (pintype "output"))
      (node (ref "CMP60") (pin "P$2") (pinfunction "1_P$2") (pintype "input"))
    )
    (net (code "84") (name "IS_STATE_0_4") (class "Default")
      (node (ref "CMP62") (pin "OUT_P") (pinfunction "P_OUT_P") (pintype "output"))
      (node (ref "CMP64") (pin "P$1") (pinfunction "A0_P$1") (pintype "input"))
    )
    (net (code "85") (name "IS_STATE_4_6") (class "Default")
      (node (ref "CMP47") (pin "OUT_P") (pinfunction "P_OUT_P") (pintype "output"))
      (node (ref "CMP50") (pin "P$1") (pinfunction "A0_P$1") (pintype "input"))
      (node (ref "CMP85") (pin "P$1") (pinfunction "1_P$1") (pintype "input"))
    )
    (net (code "86") (name "LOAD_WEIGHT") (class "Default")
      (node (ref "CMP42") (pin "P$1") (pinfunction "1_P$1") (pintype "input"))
      (node (ref "CMP54") (pin "P$2") (pinfunction "2_P$2") (pintype "input"))
      (node (ref "CMP65") (pin "P$14") (pinfunction "OUT_13_P$14") (pintype "output"))
      (node (ref "CMP75") (pin "P$2") (pinfunction "A1_P$2") (pintype "input"))
      (node (ref "CMP81") (pin "P$2") (pinfunction "A1_P$2") (pintype "input"))
    )
    (net (code "87") (name "MAIN_RN_INPUT_MUX_0XT_READ") (class "Default")
      (node (ref "CMP15") (pin "OUT_P") (pinfunction "P_OUT_P") (pintype "output"))
      (node (ref "CMP25") (pin "P$2") (pinfunction "IN_1_P$2") (pintype "input"))
    )
    (net (code "88") (name "MAIN_RN_INPUT_MUX_0XT_READ__LOAD_BYTE") (class "Default")
      (node (ref "CMP15") (pin "P$2") (pinfunction "A1_P$2") (pintype "input"))
      (node (ref "CMP16") (pin "OUT_P") (pinfunction "P_OUT_P") (pintype "output"))
    )
    (net (code "89") (name "MAIN_RN_INPUT_MUX_ALU") (class "Default")
      (node (ref "CMP13") (pin "OUT_P") (pinfunction "P_OUT_P") (pintype "output"))
      (node (ref "CMP25") (pin "P$1") (pinfunction "IN_0_P$1") (pintype "input"))
    )
    (net (code "90") (name "MAIN_RN_INPUT_MUX_ALU__SET_A") (class "Default")
      (node (ref "CMP13") (pin "5") (pinfunction "4_5") (pintype "input"))
      (node (ref "CMP5") (pin "OUT_P") (pinfunction "P_OUT_P") (pintype "output"))
    )
    (net (code "91") (name "MAIN_RN_INPUT_MUX_SHIFT_RAC") (class "Default")
      (node (ref "CMP17") (pin "OUT_P") (pinfunction "P_OUT_P") (pintype "output"))
      (node (ref "CMP25") (pin "P$3") (pinfunction "IN_2_P$3") (pintype "input"))
    )
    (net (code "92") (name "N$34") (class "Default")
      (node (ref "CMP79") (pin "P$1") (pinfunction "A0_P$1") (pintype "input"))
      (node (ref "CMP79") (pin "P$2") (pinfunction "A1_P$2") (pintype "input"))
    )
    (net (code "93") (name "NEXT_ADDR_MUX_RI__SP") (class "Default")
      (node (ref "CMP52") (pin "P$4") (pinfunction "IN_3_P$4") (pintype "input"))
      (node (ref "CMP64") (pin "OUT_P") (pinfunction "P_OUT_P") (pintype "output"))
    )
    (net (code "94") (name "NEXT_R0_MUX_ADD2") (class "Default")
      (node (ref "CMP44") (pin "OUT_P") (pinfunction "P_OUT_P") (pintype "output"))
      (node (ref "CMP9") (pin "2") (pinfunction "1_2") (pintype "input"))
      (node (ref "CMP99") (pin "P$3") (pinfunction "IN_2_P$3") (pintype "input"))
    )
    (net (code "95") (name "NEXT_R0_MUX_ADD2__WEIGHT") (class "Default")
      (node (ref "CMP42") (pin "OUT_P") (pinfunction "P_OUT_P") (pintype "output"))
      (node (ref "CMP44") (pin "P$2") (pinfunction "1_P$2") (pintype "input"))
    )
    (net (code "96") (name "NEXT_R0_MUX_HOLD") (class "Default")
      (node (ref "CMP9") (pin "OUT_M") (pinfunction "N_OUT_M") (pintype "output"))
      (node (ref "CMP99") (pin "P$1") (pinfunction "IN_0_P$1") (pintype "input"))
    )
    (net (code "97") (name "NEXT_R0_MUX_MAIN") (class "Default")
      (node (ref "CMP56") (pin "OUT_P") (pinfunction "P_OUT_P") (pintype "output"))
      (node (ref "CMP9") (pin "3") (pinfunction "2_3") (pintype "input"))
      (node (ref "CMP99") (pin "P$4") (pinfunction "IN_3_P$4") (pintype "input"))
    )
    (net (code "98") (name "NEXT_R1_MUX_ADD2") (class "Default")
      (node (ref "CMP40") (pin "P$2") (pinfunction "1_P$2") (pintype "input"))
      (node (ref "CMP54") (pin "OUT_P") (pinfunction "P_OUT_P") (pintype "output"))
      (node (ref "CMP99") (pin "P$7") (pinfunction "IN_6_P$7") (pintype "input"))
    )
    (net (code "99") (name "NEXT_R1_MUX_HOLD") (class "Default")
      (node (ref "CMP40") (pin "OUT_M") (pinfunction "N_OUT_M") (pintype "output"))
      (node (ref "CMP99") (pin "P$5") (pinfunction "IN_4_P$5") (pintype "input"))
    )
    (net (code "100") (name "NEXT_R1_MUX_MAIN") (class "Default")
      (node (ref "CMP40") (pin "P$3") (pinfunction "2_P$3") (pintype "input"))
      (node (ref "CMP68") (pin "OUT_P") (pinfunction "P_OUT_P") (pintype "output"))
      (node (ref "CMP99") (pin "P$8") (pinfunction "IN_7_P$8") (pintype "input"))
    )
    (net (code "101") (name "NEXT_R1_MUX_MAIN__DIV") (class "Default")
      (node (ref "CMP68") (pin "P$1") (pinfunction "0_P$1") (pintype "input"))
      (node (ref "CMP84") (pin "OUT_P") (pinfunction "P_OUT_P") (pintype "output"))
    )
    (net (code "102") (name "NEXT_R1_MUX_MAIN__RAC") (class "Default")
      (node (ref "CMP68") (pin "P$2") (pinfunction "1_P$2") (pintype "input"))
      (node (ref "CMP69") (pin "OUT_P") (pinfunction "P_OUT_P") (pintype "output"))
    )
    (net (code "103") (name "NEXT_R2_MUX_ADD2") (class "Default")
      (node (ref "CMP10") (pin "3") (pinfunction "2_3") (pintype "input"))
      (node (ref "CMP66") (pin "OUT_P") (pinfunction "P_OUT_P") (pintype "output"))
      (node (ref "CMP99") (pin "P$9") (pinfunction "IN_8_P$9") (pintype "input"))
    )
    (net (code "104") (name "NEXT_R2_MUX_ADD2__A") (class "Default")
      (node (ref "CMP66") (pin "P$1") (pinfunction "A2_P$1") (pintype "input"))
      (node (ref "CMP81") (pin "OUT_P") (pinfunction "P_OUT_P") (pintype "output"))
    )
    (net (code "105") (name "NEXT_R2_MUX_CLEAR") (class "Default")
      (node (ref "CMP10") (pin "2") (pinfunction "1_2") (pintype "input"))
      (node (ref "CMP73") (pin "OUT_P") (pinfunction "P_OUT_P") (pintype "output"))
    )
    (net (code "106") (name "NEXT_R2_MUX_HOLD") (class "Default")
      (node (ref "CMP10") (pin "OUT_M") (pinfunction "N_OUT_M") (pintype "output"))
      (node (ref "CMP99") (pin "P$12") (pinfunction "IN_11_P$12") (pintype "input"))
    )
    (net (code "107") (name "NEXT_R2_MUX_MAIN") (class "Default")
      (node (ref "CMP10") (pin "4") (pinfunction "3_4") (pintype "input"))
      (node (ref "CMP70") (pin "OUT_P") (pinfunction "P_OUT_P") (pintype "output"))
      (node (ref "CMP99") (pin "P$10") (pinfunction "IN_9_P$10") (pintype "input"))
    )
    (net (code "108") (name "NEXT_R3_MUX_ADD2") (class "Default")
      (node (ref "CMP24") (pin "2") (pinfunction "1_2") (pintype "input"))
      (node (ref "CMP71") (pin "OUT_P") (pinfunction "P_OUT_P") (pintype "output"))
      (node (ref "CMP99") (pin "P$13") (pinfunction "IN_12_P$13") (pintype "input"))
    )
    (net (code "109") (name "NEXT_R3_MUX_ADD2__A") (class "Default")
      (node (ref "CMP71") (pin "P$1") (pinfunction "A2_P$1") (pintype "input"))
      (node (ref "CMP75") (pin "OUT_P") (pinfunction "P_OUT_P") (pintype "output"))
    )
    (net (code "110") (name "NEXT_R3_MUX_CLEAR") (class "Default")
      (node (ref "CMP24") (pin "1") (pinfunction "0_1") (pintype "input"))
      (node (ref "CMP79") (pin "OUT_P") (pinfunction "P_OUT_P") (pintype "output"))
    )
    (net (code "111") (name "NEXT_R3_MUX_DIV_SHIFT_R3") (class "Default")
      (node (ref "CMP24") (pin "4") (pinfunction "3_4") (pintype "input"))
      (node (ref "CMP77") (pin "OUT_P") (pinfunction "P_OUT_P") (pintype "output"))
      (node (ref "CMP99") (pin "P$16") (pinfunction "IN_15_P$16") (pintype "input"))
    )
    (net (code "112") (name "NEXT_R3_MUX_HOLD") (class "Default")
      (node (ref "CMP24") (pin "OUT_M") (pinfunction "N_OUT_M") (pintype "output"))
      (node (ref "CMP99") (pin "P$15") (pinfunction "IN_14_P$15") (pintype "input"))
    )
    (net (code "113") (name "NEXT_R3_MUX_MAIN") (class "Default")
      (node (ref "CMP24") (pin "3") (pinfunction "2_3") (pintype "input"))
      (node (ref "CMP78") (pin "OUT_P") (pinfunction "P_OUT_P") (pintype "output"))
      (node (ref "CMP99") (pin "P$14") (pinfunction "IN_13_P$14") (pintype "input"))
    )
    (net (code "114") (name "Net-(CMP52-IN_10)") (class "Default")
      (node (ref "CMP52") (pin "P$10") (pinfunction "IN_9_P$10") (pintype "input"))
      (node (ref "CMP52") (pin "P$11") (pinfunction "IN_10_P$11") (pintype "input"))
      (node (ref "CMP52") (pin "P$12") (pinfunction "IN_11_P$12") (pintype "input"))
      (node (ref "CMP52") (pin "P$13") (pinfunction "IN_12_P$13") (pintype "input"))
      (node (ref "CMP52") (pin "P$14") (pinfunction "IN_13_P$14") (pintype "input"))
      (node (ref "CMP52") (pin "P$15") (pinfunction "IN_14_P$15") (pintype "input"))
      (node (ref "CMP52") (pin "P$16") (pinfunction "IN_15_P$16") (pintype "input"))
      (node (ref "CMP52") (pin "P$7") (pinfunction "IN_6_P$7") (pintype "input"))
      (node (ref "CMP52") (pin "P$8") (pinfunction "IN_7_P$8") (pintype "input"))
      (node (ref "CMP52") (pin "P$9") (pinfunction "IN_8_P$9") (pintype "input"))
    )
    (net (code "115") (name "Net-(CMP89-IN_1)") (class "Default")
      (node (ref "CMP89") (pin "P$10") (pinfunction "IN_9_P$10") (pintype "input"))
      (node (ref "CMP89") (pin "P$11") (pinfunction "IN_10_P$11") (pintype "input"))
      (node (ref "CMP89") (pin "P$12") (pinfunction "IN_11_P$12") (pintype "input"))
      (node (ref "CMP89") (pin "P$13") (pinfunction "IN_12_P$13") (pintype "input"))
      (node (ref "CMP89") (pin "P$14") (pinfunction "IN_13_P$14") (pintype "input"))
      (node (ref "CMP89") (pin "P$15") (pinfunction "IN_14_P$15") (pintype "input"))
      (node (ref "CMP89") (pin "P$16") (pinfunction "IN_15_P$16") (pintype "input"))
      (node (ref "CMP89") (pin "P$2") (pinfunction "IN_1_P$2") (pintype "input"))
      (node (ref "CMP89") (pin "P$3") (pinfunction "IN_2_P$3") (pintype "input"))
      (node (ref "CMP89") (pin "P$4") (pinfunction "IN_3_P$4") (pintype "input"))
      (node (ref "CMP89") (pin "P$5") (pinfunction "IN_4_P$5") (pintype "input"))
      (node (ref "CMP89") (pin "P$6") (pinfunction "IN_5_P$6") (pintype "input"))
      (node (ref "CMP89") (pin "P$7") (pinfunction "IN_6_P$7") (pintype "input"))
      (node (ref "CMP89") (pin "P$8") (pinfunction "IN_7_P$8") (pintype "input"))
      (node (ref "CMP89") (pin "P$9") (pinfunction "IN_8_P$9") (pintype "input"))
    )
    (net (code "116") (name "OPCODE_IS_ADDX") (class "Default")
      (node (ref "CMP26") (pin "P$2") (pinfunction "A1_P$2") (pintype "input"))
      (node (ref "CMP3") (pin "1") (pinfunction "0_1") (pintype "input"))
      (node (ref "CMP57") (pin "P$3") (pinfunction "OUT_2_P$3") (pintype "output"))
    )
    (net (code "117") (name "OPCODE_IS_ADD_SP_STATE_2") (class "Default")
      (node (ref "CMP57") (pin "P$8") (pinfunction "OUT_7_P$8") (pintype "output"))
      (node (ref "CMP61") (pin "1") (pinfunction "0_1") (pintype "input"))
    )
    (net (code "118") (name "OPCODE_IS_DIV") (class "Default")
      (node (ref "CMP13") (pin "3") (pinfunction "2_3") (pintype "input"))
      (node (ref "CMP65") (pin "P$6") (pinfunction "OUT_5_P$6") (pintype "output"))
      (node (ref "CMP76") (pin "P$2") (pinfunction "2_P$2") (pintype "input"))
    )
    (net (code "119") (name "OPCODE_IS_DIVS_STATE_0") (class "Default")
      (node (ref "CMP3") (pin "3") (pinfunction "2_3") (pintype "input"))
      (node (ref "CMP57") (pin "P$16") (pinfunction "OUT_15_P$16") (pintype "output"))
      (node (ref "CMP84") (pin "P$2") (pinfunction "2_P$2") (pintype "input"))
    )
    (net (code "120") (name "OPCODE_IS_DIV_STATE_0") (class "Default")
      (node (ref "CMP65") (pin "P$10") (pinfunction "OUT_9_P$10") (pintype "output"))
      (node (ref "CMP79") (pin "P$6") (pinfunction "C1_P$6") (pintype "input"))
      (node (ref "CMP81") (pin "P$4") (pinfunction "B1_P$4") (pintype "input"))
    )
    (net (code "121") (name "OPCODE_IS_INDIRECT_POSTINC") (class "Default")
      (node (ref "CMP32") (pin "P$2") (pinfunction "A1_P$2") (pintype "input"))
      (node (ref "CMP33") (pin "P$2") (pinfunction "2_P$2") (pintype "input"))
      (node (ref "CMP34") (pin "P$2") (pinfunction "2_P$2") (pintype "input"))
      (node (ref "CMP65") (pin "P$1") (pinfunction "OUT_0_P$1") (pintype "output"))
    )
    (net (code "122") (name "OPCODE_IS_JSR_ABS") (class "Default")
      (node (ref "CMP55") (pin "IN") (pinfunction "IN_IN") (pintype "input"))
      (node (ref "CMP57") (pin "P$15") (pinfunction "OUT_14_P$15") (pintype "output"))
      (node (ref "CMP58") (pin "P$2") (pinfunction "A1_P$2") (pintype "input"))
      (node (ref "CMP58") (pin "P$4") (pinfunction "B1_P$4") (pintype "input"))
    )
    (net (code "123") (name "OPCODE_IS_JSR_ABS_N") (class "Default")
      (node (ref "CMP55") (pin "N") (pinfunction "N_N") (pintype "output"))
      (node (ref "CMP60") (pin "P$3") (pinfunction "2_P$3") (pintype "input"))
    )
    (net (code "124") (name "OPCODE_IS_JSR_R0") (class "Default")
      (node (ref "CMP59") (pin "P$4") (pinfunction "B1_P$4") (pintype "input"))
      (node (ref "CMP65") (pin "P$3") (pinfunction "OUT_2_P$3") (pintype "output"))
    )
    (net (code "125") (name "OPCODE_IS_LDI_X") (class "Default")
      (node (ref "CMP20") (pin "P$2") (pinfunction "A1_P$2") (pintype "input"))
      (node (ref "CMP20") (pin "P$3") (pinfunction "B0_P$3") (pintype "input"))
      (node (ref "CMP65") (pin "P$11") (pinfunction "OUT_10_P$11") (pintype "output"))
    )
    (net (code "126") (name "OPCODE_IS_LD_ST") (class "Default")
      (node (ref "CMP16") (pin "P$1") (pinfunction "1_P$1") (pintype "input"))
      (node (ref "CMP17") (pin "P$1") (pinfunction "1_P$1") (pintype "input"))
      (node (ref "CMP65") (pin "P$4") (pinfunction "OUT_3_P$4") (pintype "output"))
      (node (ref "CMP80") (pin "P$1") (pinfunction "A0_P$1") (pintype "input"))
      (node (ref "CMP80") (pin "P$3") (pinfunction "B0_P$3") (pintype "input"))
    )
    (net (code "127") (name "OPCODE_IS_MOVE_R0_SP_STATE_0") (class "Default")
      (node (ref "CMP44") (pin "P$3") (pinfunction "2_P$3") (pintype "input"))
      (node (ref "CMP57") (pin "P$9") (pinfunction "OUT_8_P$9") (pintype "output"))
      (node (ref "CMP61") (pin "2") (pinfunction "1_2") (pintype "input"))
    )
    (net (code "128") (name "OPCODE_IS_MUL") (class "Default")
      (node (ref "CMP28") (pin "P$3") (pinfunction "3_P$3") (pintype "input"))
      (node (ref "CMP5") (pin "P$2") (pinfunction "A1_P$2") (pintype "input"))
      (node (ref "CMP57") (pin "P$10") (pinfunction "OUT_9_P$10") (pintype "output"))
      (node (ref "CMP73") (pin "P$1") (pinfunction "1_P$1") (pintype "input"))
      (node (ref "CMP78") (pin "P$6") (pinfunction "C1_P$6") (pintype "input"))
      (node (ref "CMP79") (pin "P$8") (pinfunction "D1_P$8") (pintype "input"))
    )
    (net (code "129") (name "OPCODE_IS_MULS") (class "Default")
      (node (ref "CMP2") (pin "P$2") (pinfunction "A1_P$2") (pintype "input"))
      (node (ref "CMP57") (pin "P$5") (pinfunction "OUT_4_P$5") (pintype "output"))
    )
    (net (code "130") (name "OPCODE_IS_NEGX") (class "Default")
      (node (ref "CMP2") (pin "P$3") (pinfunction "B0_P$3") (pintype "input"))
      (node (ref "CMP2") (pin "P$4") (pinfunction "B1_P$4") (pintype "input"))
      (node (ref "CMP57") (pin "P$6") (pinfunction "OUT_5_P$6") (pintype "output"))
    )
    (net (code "131") (name "OPCODE_IS_POP_PS") (class "Default")
      (node (ref "CMP15") (pin "P$1") (pinfunction "A2_P$1") (pintype "input"))
      (node (ref "CMP65") (pin "P$5") (pinfunction "OUT_4_P$5") (pintype "output"))
    )
    (net (code "132") (name "OPCODE_IS_POSTINC_GROUP") (class "Default")
      (node (ref "CMP50") (pin "P$3") (pinfunction "A2_P$3") (pintype "input"))
      (node (ref "CMP50") (pin "P$4") (pinfunction "B0_P$4") (pintype "input"))
      (node (ref "CMP65") (pin "P$15") (pinfunction "OUT_14_P$15") (pintype "output"))
    )
    (net (code "133") (name "OPCODE_IS_SHIFT_BIT") (class "Default")
      (node (ref "CMP13") (pin "2") (pinfunction "1_2") (pintype "input"))
      (node (ref "CMP39") (pin "E") (pinfunction "E_E") (pintype "input"))
      (node (ref "CMP57") (pin "P$4") (pinfunction "OUT_3_P$4") (pintype "output"))
      (node (ref "CMP7") (pin "P$2") (pinfunction "A1_P$2") (pintype "input"))
    )
    (net (code "134") (name "OPCODE_IS_SQRT") (class "Default")
      (node (ref "CMP13") (pin "1") (pinfunction "0_1") (pintype "input"))
      (node (ref "CMP21") (pin "P$1") (pinfunction "1_P$1") (pintype "input"))
      (node (ref "CMP27") (pin "P$2") (pinfunction "A1_P$2") (pintype "input"))
      (node (ref "CMP57") (pin "P$12") (pinfunction "OUT_11_P$12") (pintype "output"))
      (node (ref "CMP6") (pin "P$2") (pinfunction "A1_P$2") (pintype "input"))
      (node (ref "CMP79") (pin "P$3") (pinfunction "B0_P$3") (pintype "input"))
    )
    (net (code "135") (name "OPCODE_IS_STACK_GROUP") (class "Default")
      (node (ref "CMP57") (pin "P$13") (pinfunction "OUT_12_P$13") (pintype "output"))
      (node (ref "CMP60") (pin "P$1") (pinfunction "0_P$1") (pintype "input"))
    )
    (net (code "136") (name "OPCODE_IS_STACK_REL_STATE_2") (class "Default")
      (node (ref "CMP57") (pin "P$11") (pinfunction "OUT_10_P$11") (pintype "output"))
      (node (ref "CMP61") (pin "3") (pinfunction "2_3") (pintype "input"))
    )
    (net (code "137") (name "OPCODE_IS_SUBX") (class "Default")
      (node (ref "CMP26") (pin "P$1") (pinfunction "A2_P$1") (pintype "input"))
      (node (ref "CMP3") (pin "2") (pinfunction "1_2") (pintype "input"))
      (node (ref "CMP57") (pin "P$2") (pinfunction "OUT_1_P$2") (pintype "output"))
    )
    (net (code "138") (name "OPCODE_IS_SXT") (class "Default")
      (node (ref "CMP25") (pin "P$4") (pinfunction "IN_3_P$4") (pintype "input"))
      (node (ref "CMP57") (pin "P$7") (pinfunction "OUT_6_P$7") (pintype "output"))
      (node (ref "CMP83") (pin "IN") (pinfunction "IN_IN") (pintype "input"))
    )
    (net (code "139") (name "OPCODE_IS_SXT_N") (class "Default")
      (node (ref "CMP5") (pin "P$3") (pinfunction "B0_P$3") (pintype "input"))
      (node (ref "CMP83") (pin "N") (pinfunction "N_N") (pintype "output"))
    )
    (net (code "140") (name "OPCODE_IS_TRAP") (class "Default")
      (node (ref "CMP59") (pin "P$2") (pinfunction "A1_P$2") (pintype "input"))
      (node (ref "CMP65") (pin "P$2") (pinfunction "OUT_1_P$2") (pintype "output"))
    )
    (net (code "141") (name "OPCODE_IS_X_ARITH") (class "Default")
      (node (ref "CMP13") (pin "4") (pinfunction "3_4") (pintype "input"))
      (node (ref "CMP56") (pin "P$1") (pinfunction "A0_P$1") (pintype "input"))
      (node (ref "CMP56") (pin "P$2") (pinfunction "A1_P$2") (pintype "input"))
      (node (ref "CMP65") (pin "P$16") (pinfunction "OUT_15_P$16") (pintype "output"))
    )
    (net (code "142") (name "R0_IS_N") (class "Default")
      (node (ref "CMP86") (pin "P$1") (pinfunction "OUT_0_P$1") (pintype "output"))
    )
    (net (code "143") (name "R0_IS_Z") (class "Default")
      (node (ref "CMP86") (pin "P$5") (pinfunction "OUT_4_P$5") (pintype "output"))
    )
    (net (code "144") (name "R1_IS_N") (class "Default")
      (node (ref "CMP63") (pin "P$2") (pinfunction "A1_P$2") (pintype "input"))
      (node (ref "CMP84") (pin "P$1") (pinfunction "1_P$1") (pintype "input"))
      (node (ref "CMP86") (pin "P$2") (pinfunction "OUT_1_P$2") (pintype "output"))
    )
    (net (code "145") (name "R1_IS_Z") (class "Default")
      (node (ref "CMP86") (pin "P$6") (pinfunction "OUT_5_P$6") (pintype "output"))
    )
    (net (code "146") (name "R2_IS_N") (class "Default")
      (node (ref "CMP86") (pin "P$3") (pinfunction "OUT_2_P$3") (pintype "output"))
    )
    (net (code "147") (name "R2_IS_Z") (class "Default")
      (node (ref "CMP86") (pin "P$7") (pinfunction "OUT_6_P$7") (pintype "output"))
    )
    (net (code "148") (name "R2_SHIFT_IN") (class "Default")
      (node (ref "CMP89") (pin "P$1") (pinfunction "IN_0_P$1") (pintype "input"))
      (node (ref "CMP93") (pin "OUT_P") (pinfunction "P_OUT_P") (pintype "output"))
    )
    (net (code "149") (name "R3_IS_N") (class "Default")
      (node (ref "CMP86") (pin "P$4") (pinfunction "OUT_3_P$4") (pintype "output"))
    )
    (net (code "150") (name "R3_IS_NZ") (class "Default")
      (node (ref "CMP53") (pin "P$1") (pinfunction "1_P$1") (pintype "input"))
      (node (ref "CMP90") (pin "N") (pinfunction "N_N") (pintype "output"))
    )
    (net (code "151") (name "R3_IS_Z") (class "Default")
      (node (ref "CMP86") (pin "P$8") (pinfunction "OUT_7_P$8") (pintype "output"))
      (node (ref "CMP90") (pin "IN") (pinfunction "IN_IN") (pintype "input"))
    )
    (net (code "152") (name "RAC_MUX_0") (class "Default")
      (node (ref "CMP25") (pin "P$13") (pinfunction "IN_12_P$13") (pintype "input"))
      (node (ref "CMP35") (pin "OUT_P") (pinfunction "P_OUT_P") (pintype "output"))
      (node (ref "CMP42") (pin "P$2") (pinfunction "2_P$2") (pintype "input"))
      (node (ref "CMP56") (pin "P$4") (pinfunction "B1_P$4") (pintype "input"))
    )
    (net (code "153") (name "RAC_MUX_1") (class "Default")
      (node (ref "CMP25") (pin "P$14") (pinfunction "IN_13_P$14") (pintype "input"))
      (node (ref "CMP36") (pin "OUT_P") (pinfunction "P_OUT_P") (pintype "output"))
      (node (ref "CMP54") (pin "P$1") (pinfunction "1_P$1") (pintype "input"))
      (node (ref "CMP69") (pin "P$1") (pinfunction "1_P$1") (pintype "input"))
    )
    (net (code "154") (name "RAC_MUX_3") (class "Default")
      (node (ref "CMP25") (pin "P$16") (pinfunction "IN_15_P$16") (pintype "input"))
      (node (ref "CMP37") (pin "OUT_P") (pinfunction "P_OUT_P") (pintype "output"))
      (node (ref "CMP75") (pin "P$1") (pinfunction "A0_P$1") (pintype "input"))
      (node (ref "CMP78") (pin "P$7") (pinfunction "D0_P$7") (pintype "input"))
    )
    (net (code "155") (name "RA_MUX_0_RC") (class "Default")
      (node (ref "CMP33") (pin "OUT_P") (pinfunction "P_OUT_P") (pintype "output"))
      (node (ref "CMP35") (pin "P$2") (pinfunction "1_P$2") (pintype "input"))
    )
    (net (code "156") (name "RA_MUX_1_RC") (class "Default")
      (node (ref "CMP34") (pin "OUT_P") (pinfunction "P_OUT_P") (pintype "output"))
      (node (ref "CMP36") (pin "P$2") (pinfunction "1_P$2") (pintype "input"))
    )
    (net (code "157") (name "RA_MUX_NORM_EN") (class "Default")
      (node (ref "CMP32") (pin "OUT_M") (pinfunction "N_OUT_M") (pintype "output"))
      (node (ref "CMP51") (pin "E") (pinfunction "E_E") (pintype "input"))
    )
    (net (code "158") (name "RA_NORM_0") (class "Default")
      (node (ref "CMP35") (pin "P$3") (pinfunction "2_P$3") (pintype "input"))
      (node (ref "CMP51") (pin "P0") (pinfunction "P0_P0") (pintype "output"))
    )
    (net (code "159") (name "RA_NORM_1") (class "Default")
      (node (ref "CMP36") (pin "P$3") (pinfunction "2_P$3") (pintype "input"))
      (node (ref "CMP51") (pin "P1") (pinfunction "P1_P1") (pintype "output"))
    )
    (net (code "160") (name "RA_NORM_2") (class "Default")
      (node (ref "CMP25") (pin "P$15") (pinfunction "IN_14_P$15") (pintype "input"))
      (node (ref "CMP51") (pin "P2") (pinfunction "P2_P2") (pintype "output"))
      (node (ref "CMP70") (pin "P$3") (pinfunction "B0_P$3") (pintype "input"))
      (node (ref "CMP81") (pin "P$1") (pinfunction "A0_P$1") (pintype "input"))
    )
    (net (code "161") (name "RA_NORM_3") (class "Default")
      (node (ref "CMP37") (pin "P$2") (pinfunction "A1_P$2") (pintype "input"))
      (node (ref "CMP51") (pin "P3") (pinfunction "P3_P3") (pintype "output"))
    )
    (net (code "162") (name "RB_MUX_0") (class "Default")
      (node (ref "CMP25") (pin "P$9") (pinfunction "IN_8_P$9") (pintype "input"))
      (node (ref "CMP8") (pin "OUT_P") (pinfunction "P_OUT_P") (pintype "output"))
    )
    (net (code "163") (name "RB_MUX_1") (class "Default")
      (node (ref "CMP12") (pin "OUT_P") (pinfunction "P_OUT_P") (pintype "output"))
      (node (ref "CMP25") (pin "P$10") (pinfunction "IN_9_P$10") (pintype "input"))
    )
    (net (code "164") (name "RB_MUX_2") (class "Default")
      (node (ref "CMP14") (pin "OUT_P") (pinfunction "P_OUT_P") (pintype "output"))
      (node (ref "CMP25") (pin "P$11") (pinfunction "IN_10_P$11") (pintype "input"))
    )
    (net (code "165") (name "RB_MUX_3") (class "Default")
      (node (ref "CMP19") (pin "OUT_P") (pinfunction "P_OUT_P") (pintype "output"))
      (node (ref "CMP25") (pin "P$12") (pinfunction "IN_11_P$12") (pintype "input"))
    )
    (net (code "166") (name "RB_MUX_NORM_EN") (class "Default")
      (node (ref "CMP38") (pin "E") (pinfunction "E_E") (pintype "input"))
      (node (ref "CMP7") (pin "OUT_M") (pinfunction "N_OUT_M") (pintype "output"))
    )
    (net (code "167") (name "RB_NORM_0") (class "Default")
      (node (ref "CMP38") (pin "P0") (pinfunction "P0_P0") (pintype "output"))
      (node (ref "CMP8") (pin "P$1") (pinfunction "0_P$1") (pintype "input"))
    )
    (net (code "168") (name "RB_NORM_1") (class "Default")
      (node (ref "CMP12") (pin "P$1") (pinfunction "0_P$1") (pintype "input"))
      (node (ref "CMP38") (pin "P1") (pinfunction "P1_P1") (pintype "output"))
    )
    (net (code "169") (name "RB_NORM_2") (class "Default")
      (node (ref "CMP14") (pin "P$3") (pinfunction "2_P$3") (pintype "input"))
      (node (ref "CMP38") (pin "P2") (pinfunction "P2_P2") (pintype "output"))
    )
    (net (code "170") (name "RB_NORM_3") (class "Default")
      (node (ref "CMP19") (pin "P$2") (pinfunction "1_P$2") (pintype "input"))
      (node (ref "CMP38") (pin "P3") (pinfunction "P3_P3") (pintype "output"))
    )
    (net (code "171") (name "RB_SHIFT_0") (class "Default")
      (node (ref "CMP39") (pin "P0") (pinfunction "P0_P0") (pintype "output"))
      (node (ref "CMP8") (pin "P$2") (pinfunction "1_P$2") (pintype "input"))
    )
    (net (code "172") (name "RB_SHIFT_1") (class "Default")
      (node (ref "CMP12") (pin "P$3") (pinfunction "2_P$3") (pintype "input"))
      (node (ref "CMP39") (pin "P1") (pinfunction "P1_P1") (pintype "output"))
    )
    (net (code "173") (name "RB_SHIFT_2") (class "Default")
      (node (ref "CMP14") (pin "P$2") (pinfunction "1_P$2") (pintype "input"))
      (node (ref "CMP39") (pin "P2") (pinfunction "P2_P2") (pintype "output"))
    )
    (net (code "174") (name "RB_SHIFT_3") (class "Default")
      (node (ref "CMP19") (pin "P$3") (pinfunction "2_P$3") (pintype "input"))
      (node (ref "CMP39") (pin "P3") (pinfunction "P3_P3") (pintype "output"))
    )
    (net (code "175") (name "RI_MUX_2_QUAL") (class "Default")
      (node (ref "CMP25") (pin "P$5") (pinfunction "IN_4_P$5") (pintype "input"))
      (node (ref "CMP45") (pin "OUT_P") (pinfunction "P_OUT_P") (pintype "output"))
    )
    (net (code "176") (name "RI_MUX_3_QUAL") (class "Default")
      (node (ref "CMP25") (pin "P$6") (pinfunction "IN_5_P$6") (pintype "input"))
      (node (ref "CMP46") (pin "OUT_P") (pinfunction "P_OUT_P") (pintype "output"))
    )
    (net (code "177") (name "RI_MUX_H") (class "Default")
      (node (ref "CMP25") (pin "P$7") (pinfunction "IN_6_P$7") (pintype "input"))
      (node (ref "CMP41") (pin "OUT_P") (pinfunction "P_OUT_P") (pintype "output"))
      (node (ref "CMP43") (pin "P$2") (pinfunction "1_P$2") (pintype "input"))
    )
    (net (code "178") (name "RI_MUX_R2") (class "Default")
      (node (ref "CMP1") (pin "OUT_P") (pinfunction "P_OUT_P") (pintype "output"))
      (node (ref "CMP43") (pin "P$3") (pinfunction "2_P$3") (pintype "input"))
      (node (ref "CMP45") (pin "P$3") (pinfunction "B0_P$3") (pintype "input"))
      (node (ref "CMP45") (pin "P$4") (pinfunction "B1_P$4") (pintype "input"))
    )
    (net (code "179") (name "RI_MUX_SPECIAL") (class "Default")
      (node (ref "CMP43") (pin "OUT_P") (pinfunction "P_OUT_P") (pintype "output"))
    )
    (net (code "180") (name "RI_MUX_SPECIAL_N") (class "Default")
      (node (ref "CMP43") (pin "OUT_M") (pinfunction "N_OUT_M") (pintype "output"))
      (node (ref "CMP45") (pin "P$1") (pinfunction "A0_P$1") (pintype "input"))
      (node (ref "CMP46") (pin "P$2") (pinfunction "2_P$2") (pintype "input"))
    )
    (net (code "181") (name "RNX_SPECIALS") (class "Default")
      (node (ref "CMP52") (pin "INPUT") (pinfunction "OUT_INPUT") (pintype "output"))
    )
    (net (code "182") (name "SHIFT_IS_SHIFTING") (class "Default")
      (node (ref "CMP65") (pin "P$8") (pinfunction "OUT_7_P$8") (pintype "output"))
      (node (ref "CMP82") (pin "3") (pinfunction "2_3") (pintype "input"))
    )
    (net (code "183") (name "SHIFT_RESULT_C_FLAG") (class "Default")
      (node (ref "CMP97") (pin "P$4") (pinfunction "OUT_3_P$4") (pintype "output"))
    )
    (net (code "184") (name "SHIFT_RESULT_V_FLAG") (class "Default")
      (node (ref "CMP97") (pin "P$6") (pinfunction "OUT_5_P$6") (pintype "output"))
    )
    (net (code "185") (name "SQRT_CONDITIONAL") (class "Default")
      (node (ref "CMP63") (pin "OUT_P") (pinfunction "P_OUT_P") (pintype "output"))
      (node (ref "CMP72") (pin "P$1") (pinfunction "1_P$1") (pintype "input"))
    )
    (net (code "186") (name "SQRT_ODD_CONDITIONAL") (class "Default")
      (node (ref "CMP68") (pin "P$3") (pinfunction "2_P$3") (pintype "input"))
      (node (ref "CMP72") (pin "OUT_P") (pinfunction "P_OUT_P") (pintype "output"))
      (node (ref "CMP74") (pin "P$2") (pinfunction "A1_P$2") (pintype "input"))
    )
    (net (code "187") (name "SQRT_ODD_CONDITIONAL_MUL_14") (class "Default")
      (node (ref "CMP44") (pin "P$1") (pinfunction "0_P$1") (pintype "input"))
      (node (ref "CMP74") (pin "OUT_P") (pinfunction "P_OUT_P") (pintype "output"))
    )
    (net (code "188") (name "SQRT_STATE_0") (class "Default")
      (node (ref "CMP21") (pin "OUT_P") (pinfunction "P_OUT_P") (pintype "output"))
      (node (ref "CMP9") (pin "4") (pinfunction "3_4") (pintype "input"))
    )
    (net (code "189") (name "SQRT_STATE_10_EVEN_CYCLE") (class "Default")
      (node (ref "CMP23") (pin "OUT_P") (pinfunction "P_OUT_P") (pintype "output"))
      (node (ref "CMP71") (pin "P$2") (pinfunction "A1_P$2") (pintype "input"))
      (node (ref "CMP9") (pin "1") (pinfunction "0_1") (pintype "input"))
      (node (ref "CMP99") (pin "P$2") (pinfunction "IN_1_P$2") (pintype "input"))
    )
    (net (code "190") (name "STATE_0") (class "Default")
      (node (ref "CMP18") (pin "P$1") (pinfunction "OUT_0_P$1") (pintype "output"))
      (node (ref "CMP20") (pin "P$4") (pinfunction "B1_P$4") (pintype "input"))
      (node (ref "CMP21") (pin "P$2") (pinfunction "2_P$2") (pintype "input"))
      (node (ref "CMP48") (pin "IN") (pinfunction "IN_IN") (pintype "input"))
      (node (ref "CMP50") (pin "P$6") (pinfunction "B2_P$6") (pintype "input"))
      (node (ref "CMP59") (pin "P$1") (pinfunction "A0_P$1") (pintype "input"))
      (node (ref "CMP62") (pin "P$1") (pinfunction "A2_P$1") (pintype "input"))
      (node (ref "CMP73") (pin "P$2") (pinfunction "2_P$2") (pintype "input"))
      (node (ref "CMP79") (pin "P$7") (pinfunction "D0_P$7") (pintype "input"))
    )
    (net (code "191") (name "STATE_0_N") (class "Default")
      (node (ref "CMP28") (pin "P$2") (pinfunction "2_P$2") (pintype "input"))
      (node (ref "CMP48") (pin "N") (pinfunction "N_N") (pintype "output"))
      (node (ref "CMP5") (pin "P$1") (pinfunction "A0_P$1") (pintype "input"))
      (node (ref "CMP78") (pin "P$5") (pinfunction "C0_P$5") (pintype "input"))
    )
    (net (code "192") (name "STATE_1") (class "Default")
      (node (ref "CMP18") (pin "P$2") (pinfunction "OUT_1_P$2") (pintype "output"))
      (node (ref "CMP20") (pin "P$1") (pinfunction "A0_P$1") (pintype "input"))
    )
    (net (code "193") (name "STATE_2") (class "Default")
      (node (ref "CMP18") (pin "P$3") (pinfunction "OUT_2_P$3") (pintype "output"))
    )
    (net (code "194") (name "STATE_3") (class "Default")
      (node (ref "CMP18") (pin "P$4") (pinfunction "OUT_3_P$4") (pintype "output"))
      (node (ref "CMP2") (pin "P$1") (pinfunction "A0_P$1") (pintype "input"))
      (node (ref "CMP70") (pin "P$2") (pinfunction "A1_P$2") (pintype "input"))
      (node (ref "CMP76") (pin "P$1") (pinfunction "1_P$1") (pintype "input"))
      (node (ref "CMP79") (pin "P$4") (pinfunction "B1_P$4") (pintype "input"))
    )
    (net (code "195") (name "STATE_4") (class "Default")
      (node (ref "CMP18") (pin "P$5") (pinfunction "OUT_4_P$5") (pintype "output"))
      (node (ref "CMP47") (pin "P$1") (pinfunction "A2_P$1") (pintype "input"))
      (node (ref "CMP62") (pin "P$2") (pinfunction "A1_P$2") (pintype "input"))
      (node (ref "CMP80") (pin "P$4") (pinfunction "B1_P$4") (pintype "input"))
    )
    (net (code "196") (name "STATE_5") (class "Default")
      (node (ref "CMP18") (pin "P$6") (pinfunction "OUT_5_P$6") (pintype "output"))
      (node (ref "CMP80") (pin "P$2") (pinfunction "A1_P$2") (pintype "input"))
    )
    (net (code "197") (name "STATE_6") (class "Default")
      (node (ref "CMP18") (pin "P$7") (pinfunction "OUT_6_P$7") (pintype "output"))
      (node (ref "CMP47") (pin "P$2") (pinfunction "A1_P$2") (pintype "input"))
      (node (ref "CMP58") (pin "P$1") (pinfunction "A0_P$1") (pintype "input"))
    )
    (net (code "198") (name "STATE_7") (class "Default")
      (node (ref "CMP18") (pin "P$8") (pinfunction "OUT_7_P$8") (pintype "output"))
      (node (ref "CMP59") (pin "P$3") (pinfunction "B0_P$3") (pintype "input"))
    )
    (net (code "199") (name "STATE_8") (class "Default")
      (node (ref "CMP18") (pin "P$9") (pinfunction "OUT_8_P$9") (pintype "output"))
      (node (ref "CMP64") (pin "P$3") (pinfunction "B0_P$3") (pintype "input"))
      (node (ref "CMP64") (pin "P$4") (pinfunction "B1_P$4") (pintype "input"))
    )
    (net (code "200") (name "STATE_9") (class "Default")
      (node (ref "CMP18") (pin "P$10") (pinfunction "OUT_9_P$10") (pintype "output"))
    )
    (net (code "201") (name "STATE_10") (class "Default")
      (node (ref "CMP18") (pin "P$11") (pinfunction "OUT_10_P$11") (pintype "output"))
      (node (ref "CMP23") (pin "P$2") (pinfunction "2_P$2") (pintype "input"))
      (node (ref "CMP72") (pin "P$3") (pinfunction "3_P$3") (pintype "input"))
    )
    (net (code "202") (name "STATE_11") (class "Default")
      (node (ref "CMP1") (pin "P$1") (pinfunction "A2_P$1") (pintype "input"))
      (node (ref "CMP10") (pin "1") (pinfunction "0_1") (pintype "input"))
      (node (ref "CMP18") (pin "P$12") (pinfunction "OUT_11_P$12") (pintype "output"))
      (node (ref "CMP29") (pin "P$2") (pinfunction "1_P$2") (pintype "input"))
      (node (ref "CMP3") (pin "4") (pinfunction "3_4") (pintype "input"))
      (node (ref "CMP77") (pin "P$2") (pinfunction "2_P$2") (pintype "input"))
      (node (ref "CMP78") (pin "P$2") (pinfunction "A1_P$2") (pintype "input"))
      (node (ref "CMP93") (pin "P$1") (pinfunction "1_P$1") (pintype "input"))
      (node (ref "CMP99") (pin "P$11") (pinfunction "IN_10_P$11") (pintype "input"))
    )
    (net (code "203") (name "STATE_12") (class "Default")
      (node (ref "CMP1") (pin "P$2") (pinfunction "A1_P$2") (pintype "input"))
      (node (ref "CMP18") (pin "P$13") (pinfunction "OUT_12_P$13") (pintype "output"))
      (node (ref "CMP53") (pin "P$2") (pinfunction "2_P$2") (pintype "input"))
      (node (ref "CMP6") (pin "P$1") (pinfunction "A2_P$1") (pintype "input"))
      (node (ref "CMP67") (pin "P$2") (pinfunction "2_P$2") (pintype "input"))
    )
    (net (code "204") (name "STATE_13") (class "Default")
      (node (ref "CMP18") (pin "P$14") (pinfunction "OUT_13_P$14") (pintype "output"))
      (node (ref "CMP29") (pin "P$3") (pinfunction "2_P$3") (pintype "input"))
      (node (ref "CMP40") (pin "P$1") (pinfunction "0_P$1") (pintype "input"))
      (node (ref "CMP49") (pin "IN") (pinfunction "IN_IN") (pintype "input"))
      (node (ref "CMP66") (pin "P$2") (pinfunction "A1_P$2") (pintype "input"))
      (node (ref "CMP99") (pin "P$6") (pinfunction "IN_5_P$6") (pintype "input"))
    )
    (net (code "205") (name "STATE_13_N") (class "Default")
      (node (ref "CMP28") (pin "P$1") (pinfunction "1_P$1") (pintype "input"))
      (node (ref "CMP49") (pin "N") (pinfunction "N_N") (pintype "output"))
    )
    (net (code "206") (name "STATE_14") (class "Default")
      (node (ref "CMP18") (pin "P$15") (pinfunction "OUT_14_P$15") (pintype "output"))
      (node (ref "CMP41") (pin "P$2") (pinfunction "A1_P$2") (pintype "input"))
      (node (ref "CMP74") (pin "P$1") (pinfunction "A2_P$1") (pintype "input"))
    )
    (net (code "207") (name "STATE_15") (class "Default")
      (node (ref "CMP18") (pin "P$16") (pinfunction "OUT_15_P$16") (pintype "output"))
      (node (ref "CMP58") (pin "P$3") (pinfunction "B0_P$3") (pintype "input"))
    )
    (net (code "208") (name "WR_RN_USING_RAC") (class "Default")
      (node (ref "CMP56") (pin "P$3") (pinfunction "B0_P$3") (pintype "input"))
      (node (ref "CMP69") (pin "P$2") (pinfunction "2_P$2") (pintype "input"))
      (node (ref "CMP70") (pin "P$4") (pinfunction "B1_P$4") (pintype "input"))
      (node (ref "CMP78") (pin "P$8") (pinfunction "D1_P$8") (pintype "input"))
      (node (ref "CMP82") (pin "OUT_P") (pinfunction "P_OUT_P") (pintype "output"))
    )
    (net (code "209") (name "WR_RN_USING_RAC__MEM") (class "Default")
      (node (ref "CMP80") (pin "OUT_P") (pinfunction "P_OUT_P") (pintype "output"))
      (node (ref "CMP82") (pin "4") (pinfunction "3_4") (pintype "input"))
    )
    (net (code "210") (name "WR_RN_USING_RA__BIT") (class "Default")
      (node (ref "CMP65") (pin "P$7") (pinfunction "OUT_6_P$7") (pintype "output"))
      (node (ref "CMP82") (pin "2") (pinfunction "1_2") (pintype "input"))
    )
    (net (code "211") (name "WR_RN_USING_RA__LDI") (class "Default")
      (node (ref "CMP20") (pin "OUT_P") (pinfunction "P_OUT_P") (pintype "output"))
      (node (ref "CMP82") (pin "1") (pinfunction "0_1") (pintype "input"))
    )
    (net (code "212") (name "WR_RN_USING_RA__REG_REG") (class "Default")
      (node (ref "CMP22") (pin "OUT_P") (pinfunction "P_OUT_P") (pintype "output"))
      (node (ref "CMP82") (pin "5") (pinfunction "4_5") (pintype "input"))
    )
    (net (code "213") (name "WR_RN_USING_RA__REG_REG_EXCEPTIONS_N") (class "Default")
      (node (ref "CMP22") (pin "P$2") (pinfunction "2_P$2") (pintype "input"))
      (node (ref "CMP65") (pin "P$12") (pinfunction "OUT_11_P$12") (pintype "output"))
    )
    (net (code "214") (name "WR_RN_USING_RI") (class "Default")
      (node (ref "CMP50") (pin "OUT_P") (pinfunction "P_OUT_P") (pintype "output"))
      (node (ref "CMP75") (pin "P$4") (pinfunction "B1_P$4") (pintype "input"))
      (node (ref "CMP81") (pin "P$7") (pinfunction "D0_P$7") (pintype "input"))
    )
    (net (code "215") (name "unconnected-(CMP1-N-PadOUT_M)") (class "Default")
      (node (ref "CMP1") (pin "OUT_M") (pinfunction "N_OUT_M") (pintype "output"))
    )
    (net (code "216") (name "unconnected-(CMP2-N-PadOUT_M)") (class "Default")
      (node (ref "CMP2") (pin "OUT_M") (pinfunction "N_OUT_M") (pintype "output"))
    )
    (net (code "217") (name "unconnected-(CMP3-N-PadOUT_M)") (class "Default")
      (node (ref "CMP3") (pin "OUT_M") (pinfunction "N_OUT_M") (pintype "output"))
    )
    (net (code "218") (name "unconnected-(CMP5-N-PadOUT_M)") (class "Default")
      (node (ref "CMP5") (pin "OUT_M") (pinfunction "N_OUT_M") (pintype "output"))
    )
    (net (code "219") (name "unconnected-(CMP6-N-PadOUT_M)") (class "Default")
      (node (ref "CMP6") (pin "OUT_M") (pinfunction "N_OUT_M") (pintype "output"))
    )
    (net (code "220") (name "unconnected-(CMP7-P-PadOUT_P)") (class "Default")
      (node (ref "CMP7") (pin "OUT_P") (pinfunction "P_OUT_P") (pintype "output"))
    )
    (net (code "221") (name "unconnected-(CMP8-N-PadOUT_M)") (class "Default")
      (node (ref "CMP8") (pin "OUT_M") (pinfunction "N_OUT_M") (pintype "output"))
    )
    (net (code "222") (name "unconnected-(CMP9-P-PadOUT_P)") (class "Default")
      (node (ref "CMP9") (pin "OUT_P") (pinfunction "P_OUT_P") (pintype "output"))
    )
    (net (code "223") (name "unconnected-(CMP10-P-PadOUT_P)") (class "Default")
      (node (ref "CMP10") (pin "OUT_P") (pinfunction "P_OUT_P") (pintype "output"))
    )
    (net (code "224") (name "unconnected-(CMP11-OUT_11-PadP$12)") (class "Default")
      (node (ref "CMP11") (pin "P$12") (pinfunction "OUT_11_P$12") (pintype "output"))
    )
    (net (code "225") (name "unconnected-(CMP11-OUT_12-PadP$13)") (class "Default")
      (node (ref "CMP11") (pin "P$13") (pinfunction "OUT_12_P$13") (pintype "output"))
    )
    (net (code "226") (name "unconnected-(CMP11-OUT_13-PadP$14)") (class "Default")
      (node (ref "CMP11") (pin "P$14") (pinfunction "OUT_13_P$14") (pintype "output"))
    )
    (net (code "227") (name "unconnected-(CMP12-N-PadOUT_M)") (class "Default")
      (node (ref "CMP12") (pin "OUT_M") (pinfunction "N_OUT_M") (pintype "output"))
    )
    (net (code "228") (name "unconnected-(CMP13-N-PadOUT_M)") (class "Default")
      (node (ref "CMP13") (pin "OUT_M") (pinfunction "N_OUT_M") (pintype "output"))
    )
    (net (code "229") (name "unconnected-(CMP14-N-PadOUT_M)") (class "Default")
      (node (ref "CMP14") (pin "OUT_M") (pinfunction "N_OUT_M") (pintype "output"))
    )
    (net (code "230") (name "unconnected-(CMP15-N-PadOUT_M)") (class "Default")
      (node (ref "CMP15") (pin "OUT_M") (pinfunction "N_OUT_M") (pintype "output"))
    )
    (net (code "231") (name "unconnected-(CMP16-N-PadOUT_M)") (class "Default")
      (node (ref "CMP16") (pin "OUT_M") (pinfunction "N_OUT_M") (pintype "output"))
    )
    (net (code "232") (name "unconnected-(CMP17-N-PadOUT_M)") (class "Default")
      (node (ref "CMP17") (pin "OUT_M") (pinfunction "N_OUT_M") (pintype "output"))
    )
    (net (code "233") (name "unconnected-(CMP19-N-PadOUT_M)") (class "Default")
      (node (ref "CMP19") (pin "OUT_M") (pinfunction "N_OUT_M") (pintype "output"))
    )
    (net (code "234") (name "unconnected-(CMP20-N-PadOUT_M)") (class "Default")
      (node (ref "CMP20") (pin "OUT_M") (pinfunction "N_OUT_M") (pintype "output"))
    )
    (net (code "235") (name "unconnected-(CMP21-N-PadOUT_M)") (class "Default")
      (node (ref "CMP21") (pin "OUT_M") (pinfunction "N_OUT_M") (pintype "output"))
    )
    (net (code "236") (name "unconnected-(CMP22-N-PadOUT_M)") (class "Default")
      (node (ref "CMP22") (pin "OUT_M") (pinfunction "N_OUT_M") (pintype "output"))
    )
    (net (code "237") (name "unconnected-(CMP23-N-PadOUT_M)") (class "Default")
      (node (ref "CMP23") (pin "OUT_M") (pinfunction "N_OUT_M") (pintype "output"))
    )
    (net (code "238") (name "unconnected-(CMP24-P-PadOUT_P)") (class "Default")
      (node (ref "CMP24") (pin "OUT_P") (pinfunction "P_OUT_P") (pintype "output"))
    )
    (net (code "239") (name "unconnected-(CMP26-N-PadOUT_M)") (class "Default")
      (node (ref "CMP26") (pin "OUT_M") (pinfunction "N_OUT_M") (pintype "output"))
    )
    (net (code "240") (name "unconnected-(CMP27-N-PadOUT_M)") (class "Default")
      (node (ref "CMP27") (pin "OUT_M") (pinfunction "N_OUT_M") (pintype "output"))
    )
    (net (code "241") (name "unconnected-(CMP28-M-PadOUT_M)") (class "Default")
      (node (ref "CMP28") (pin "OUT_M") (pinfunction "M_OUT_M") (pintype "output"))
    )
    (net (code "242") (name "unconnected-(CMP29-N-PadOUT_M)") (class "Default")
      (node (ref "CMP29") (pin "OUT_M") (pinfunction "N_OUT_M") (pintype "output"))
    )
    (net (code "243") (name "unconnected-(CMP31-PadP)") (class "Default")
      (node (ref "CMP31") (pin "P") (pinfunction "P_P") (pintype "output"))
    )
    (net (code "244") (name "unconnected-(CMP32-P-PadOUT_P)") (class "Default")
      (node (ref "CMP32") (pin "OUT_P") (pinfunction "P_OUT_P") (pintype "output"))
    )
    (net (code "245") (name "unconnected-(CMP33-N-PadOUT_M)") (class "Default")
      (node (ref "CMP33") (pin "OUT_M") (pinfunction "N_OUT_M") (pintype "output"))
    )
    (net (code "246") (name "unconnected-(CMP34-N-PadOUT_M)") (class "Default")
      (node (ref "CMP34") (pin "OUT_M") (pinfunction "N_OUT_M") (pintype "output"))
    )
    (net (code "247") (name "unconnected-(CMP35-N-PadOUT_M)") (class "Default")
      (node (ref "CMP35") (pin "OUT_M") (pinfunction "N_OUT_M") (pintype "output"))
    )
    (net (code "248") (name "unconnected-(CMP36-N-PadOUT_M)") (class "Default")
      (node (ref "CMP36") (pin "OUT_M") (pinfunction "N_OUT_M") (pintype "output"))
    )
    (net (code "249") (name "unconnected-(CMP37-N-PadOUT_M)") (class "Default")
      (node (ref "CMP37") (pin "OUT_M") (pinfunction "N_OUT_M") (pintype "output"))
    )
    (net (code "250") (name "unconnected-(CMP38-PadN0)") (class "Default")
      (node (ref "CMP38") (pin "N0") (pinfunction "N0_N0") (pintype "output"))
    )
    (net (code "251") (name "unconnected-(CMP38-PadN1)") (class "Default")
      (node (ref "CMP38") (pin "N1") (pinfunction "N1_N1") (pintype "output"))
    )
    (net (code "252") (name "unconnected-(CMP38-PadN2)") (class "Default")
      (node (ref "CMP38") (pin "N2") (pinfunction "N2_N2") (pintype "output"))
    )
    (net (code "253") (name "unconnected-(CMP38-PadN3)") (class "Default")
      (node (ref "CMP38") (pin "N3") (pinfunction "N3_N3") (pintype "output"))
    )
    (net (code "254") (name "unconnected-(CMP39-PadN0)") (class "Default")
      (node (ref "CMP39") (pin "N0") (pinfunction "N0_N0") (pintype "output"))
    )
    (net (code "255") (name "unconnected-(CMP39-PadN1)") (class "Default")
      (node (ref "CMP39") (pin "N1") (pinfunction "N1_N1") (pintype "output"))
    )
    (net (code "256") (name "unconnected-(CMP39-PadN2)") (class "Default")
      (node (ref "CMP39") (pin "N2") (pinfunction "N2_N2") (pintype "output"))
    )
    (net (code "257") (name "unconnected-(CMP39-PadN3)") (class "Default")
      (node (ref "CMP39") (pin "N3") (pinfunction "N3_N3") (pintype "output"))
    )
    (net (code "258") (name "unconnected-(CMP40-P-PadOUT_P)") (class "Default")
      (node (ref "CMP40") (pin "OUT_P") (pinfunction "P_OUT_P") (pintype "output"))
    )
    (net (code "259") (name "unconnected-(CMP41-N-PadOUT_M)") (class "Default")
      (node (ref "CMP41") (pin "OUT_M") (pinfunction "N_OUT_M") (pintype "output"))
    )
    (net (code "260") (name "unconnected-(CMP42-N-PadOUT_M)") (class "Default")
      (node (ref "CMP42") (pin "OUT_M") (pinfunction "N_OUT_M") (pintype "output"))
    )
    (net (code "261") (name "unconnected-(CMP44-N-PadOUT_M)") (class "Default")
      (node (ref "CMP44") (pin "OUT_M") (pinfunction "N_OUT_M") (pintype "output"))
    )
    (net (code "262") (name "unconnected-(CMP45-N-PadOUT_M)") (class "Default")
      (node (ref "CMP45") (pin "OUT_M") (pinfunction "N_OUT_M") (pintype "output"))
    )
    (net (code "263") (name "unconnected-(CMP46-N-PadOUT_M)") (class "Default")
      (node (ref "CMP46") (pin "OUT_M") (pinfunction "N_OUT_M") (pintype "output"))
    )
    (net (code "264") (name "unconnected-(CMP47-N-PadOUT_M)") (class "Default")
      (node (ref "CMP47") (pin "OUT_M") (pinfunction "N_OUT_M") (pintype "output"))
    )
    (net (code "265") (name "unconnected-(CMP48-PadP)") (class "Default")
      (node (ref "CMP48") (pin "P") (pinfunction "P_P") (pintype "output"))
    )
    (net (code "266") (name "unconnected-(CMP49-PadP)") (class "Default")
      (node (ref "CMP49") (pin "P") (pinfunction "P_P") (pintype "output"))
    )
    (net (code "267") (name "unconnected-(CMP50-N-PadOUT_M)") (class "Default")
      (node (ref "CMP50") (pin "OUT_M") (pinfunction "N_OUT_M") (pintype "output"))
    )
    (net (code "268") (name "unconnected-(CMP51-PadN0)") (class "Default")
      (node (ref "CMP51") (pin "N0") (pinfunction "N0_N0") (pintype "output"))
    )
    (net (code "269") (name "unconnected-(CMP51-PadN1)") (class "Default")
      (node (ref "CMP51") (pin "N1") (pinfunction "N1_N1") (pintype "output"))
    )
    (net (code "270") (name "unconnected-(CMP51-PadN2)") (class "Default")
      (node (ref "CMP51") (pin "N2") (pinfunction "N2_N2") (pintype "output"))
    )
    (net (code "271") (name "unconnected-(CMP51-PadN3)") (class "Default")
      (node (ref "CMP51") (pin "N3") (pinfunction "N3_N3") (pintype "output"))
    )
    (net (code "272") (name "unconnected-(CMP53-M-PadOUT_M)") (class "Default")
      (node (ref "CMP53") (pin "OUT_M") (pinfunction "M_OUT_M") (pintype "output"))
    )
    (net (code "273") (name "unconnected-(CMP54-N-PadOUT_M)") (class "Default")
      (node (ref "CMP54") (pin "OUT_M") (pinfunction "N_OUT_M") (pintype "output"))
    )
    (net (code "274") (name "unconnected-(CMP55-PadP)") (class "Default")
      (node (ref "CMP55") (pin "P") (pinfunction "P_P") (pintype "output"))
    )
    (net (code "275") (name "unconnected-(CMP56-N-PadOUT_M)") (class "Default")
      (node (ref "CMP56") (pin "OUT_M") (pinfunction "N_OUT_M") (pintype "output"))
    )
    (net (code "276") (name "unconnected-(CMP58-N-PadOUT_M)") (class "Default")
      (node (ref "CMP58") (pin "OUT_M") (pinfunction "N_OUT_M") (pintype "output"))
    )
    (net (code "277") (name "unconnected-(CMP60-N-PadOUT_M)") (class "Default")
      (node (ref "CMP60") (pin "OUT_M") (pinfunction "N_OUT_M") (pintype "output"))
    )
    (net (code "278") (name "unconnected-(CMP61-N-PadOUT_M)") (class "Default")
      (node (ref "CMP61") (pin "OUT_M") (pinfunction "N_OUT_M") (pintype "output"))
    )
    (net (code "279") (name "unconnected-(CMP62-N-PadOUT_M)") (class "Default")
      (node (ref "CMP62") (pin "OUT_M") (pinfunction "N_OUT_M") (pintype "output"))
    )
    (net (code "280") (name "unconnected-(CMP63-N-PadOUT_M)") (class "Default")
      (node (ref "CMP63") (pin "OUT_M") (pinfunction "N_OUT_M") (pintype "output"))
    )
    (net (code "281") (name "unconnected-(CMP64-N-PadOUT_M)") (class "Default")
      (node (ref "CMP64") (pin "OUT_M") (pinfunction "N_OUT_M") (pintype "output"))
    )
    (net (code "282") (name "unconnected-(CMP65-PadINPUT)") (class "Default")
      (node (ref "CMP65") (pin "INPUT") (pinfunction "INPUT_INPUT") (pintype "input"))
    )
    (net (code "283") (name "unconnected-(CMP66-N-PadOUT_M)") (class "Default")
      (node (ref "CMP66") (pin "OUT_M") (pinfunction "N_OUT_M") (pintype "output"))
    )
    (net (code "284") (name "unconnected-(CMP67-N-PadOUT_M)") (class "Default")
      (node (ref "CMP67") (pin "OUT_M") (pinfunction "N_OUT_M") (pintype "output"))
    )
    (net (code "285") (name "unconnected-(CMP68-N-PadOUT_M)") (class "Default")
      (node (ref "CMP68") (pin "OUT_M") (pinfunction "N_OUT_M") (pintype "output"))
    )
    (net (code "286") (name "unconnected-(CMP69-N-PadOUT_M)") (class "Default")
      (node (ref "CMP69") (pin "OUT_M") (pinfunction "N_OUT_M") (pintype "output"))
    )
    (net (code "287") (name "unconnected-(CMP70-N-PadOUT_M)") (class "Default")
      (node (ref "CMP70") (pin "OUT_M") (pinfunction "N_OUT_M") (pintype "output"))
    )
    (net (code "288") (name "unconnected-(CMP71-N-PadOUT_M)") (class "Default")
      (node (ref "CMP71") (pin "OUT_M") (pinfunction "N_OUT_M") (pintype "output"))
    )
    (net (code "289") (name "unconnected-(CMP72-M-PadOUT_M)") (class "Default")
      (node (ref "CMP72") (pin "OUT_M") (pinfunction "M_OUT_M") (pintype "output"))
    )
    (net (code "290") (name "unconnected-(CMP73-N-PadOUT_M)") (class "Default")
      (node (ref "CMP73") (pin "OUT_M") (pinfunction "N_OUT_M") (pintype "output"))
    )
    (net (code "291") (name "unconnected-(CMP74-N-PadOUT_M)") (class "Default")
      (node (ref "CMP74") (pin "OUT_M") (pinfunction "N_OUT_M") (pintype "output"))
    )
    (net (code "292") (name "unconnected-(CMP75-N-PadOUT_M)") (class "Default")
      (node (ref "CMP75") (pin "OUT_M") (pinfunction "N_OUT_M") (pintype "output"))
    )
    (net (code "293") (name "unconnected-(CMP76-N-PadOUT_M)") (class "Default")
      (node (ref "CMP76") (pin "OUT_M") (pinfunction "N_OUT_M") (pintype "output"))
    )
    (net (code "294") (name "unconnected-(CMP77-N-PadOUT_M)") (class "Default")
      (node (ref "CMP77") (pin "OUT_M") (pinfunction "N_OUT_M") (pintype "output"))
    )
    (net (code "295") (name "unconnected-(CMP78-N-PadOUT_M)") (class "Default")
      (node (ref "CMP78") (pin "OUT_M") (pinfunction "N_OUT_M") (pintype "output"))
    )
    (net (code "296") (name "unconnected-(CMP79-N-PadOUT_M)") (class "Default")
      (node (ref "CMP79") (pin "OUT_M") (pinfunction "N_OUT_M") (pintype "output"))
    )
    (net (code "297") (name "unconnected-(CMP80-N-PadOUT_M)") (class "Default")
      (node (ref "CMP80") (pin "OUT_M") (pinfunction "N_OUT_M") (pintype "output"))
    )
    (net (code "298") (name "unconnected-(CMP81-N-PadOUT_M)") (class "Default")
      (node (ref "CMP81") (pin "OUT_M") (pinfunction "N_OUT_M") (pintype "output"))
    )
    (net (code "299") (name "unconnected-(CMP82-N-PadOUT_M)") (class "Default")
      (node (ref "CMP82") (pin "OUT_M") (pinfunction "N_OUT_M") (pintype "output"))
    )
    (net (code "300") (name "unconnected-(CMP83-PadP)") (class "Default")
      (node (ref "CMP83") (pin "P") (pinfunction "P_P") (pintype "output"))
    )
    (net (code "301") (name "unconnected-(CMP84-N-PadOUT_M)") (class "Default")
      (node (ref "CMP84") (pin "OUT_M") (pinfunction "N_OUT_M") (pintype "output"))
    )
    (net (code "302") (name "unconnected-(CMP85-M-PadOUT_M)") (class "Default")
      (node (ref "CMP85") (pin "OUT_M") (pinfunction "M_OUT_M") (pintype "output"))
    )
    (net (code "303") (name "unconnected-(CMP86-OUT_8-PadP$9)") (class "Default")
      (node (ref "CMP86") (pin "P$9") (pinfunction "OUT_8_P$9") (pintype "output"))
    )
    (net (code "304") (name "unconnected-(CMP86-OUT_9-PadP$10)") (class "Default")
      (node (ref "CMP86") (pin "P$10") (pinfunction "OUT_9_P$10") (pintype "output"))
    )
    (net (code "305") (name "unconnected-(CMP86-OUT_10-PadP$11)") (class "Default")
      (node (ref "CMP86") (pin "P$11") (pinfunction "OUT_10_P$11") (pintype "output"))
    )
    (net (code "306") (name "unconnected-(CMP86-OUT_11-PadP$12)") (class "Default")
      (node (ref "CMP86") (pin "P$12") (pinfunction "OUT_11_P$12") (pintype "output"))
    )
    (net (code "307") (name "unconnected-(CMP86-OUT_12-PadP$13)") (class "Default")
      (node (ref "CMP86") (pin "P$13") (pinfunction "OUT_12_P$13") (pintype "output"))
    )
    (net (code "308") (name "unconnected-(CMP86-OUT_13-PadP$14)") (class "Default")
      (node (ref "CMP86") (pin "P$14") (pinfunction "OUT_13_P$14") (pintype "output"))
    )
    (net (code "309") (name "unconnected-(CMP86-OUT_14-PadP$15)") (class "Default")
      (node (ref "CMP86") (pin "P$15") (pinfunction "OUT_14_P$15") (pintype "output"))
    )
    (net (code "310") (name "unconnected-(CMP86-OUT_15-PadP$16)") (class "Default")
      (node (ref "CMP86") (pin "P$16") (pinfunction "OUT_15_P$16") (pintype "output"))
    )
    (net (code "311") (name "unconnected-(CMP87-OUT_7-PadP$8)") (class "Default")
      (node (ref "CMP87") (pin "P$8") (pinfunction "OUT_7_P$8") (pintype "output"))
    )
    (net (code "312") (name "unconnected-(CMP87-OUT_14-PadP$15)") (class "Default")
      (node (ref "CMP87") (pin "P$15") (pinfunction "OUT_14_P$15") (pintype "output"))
    )
    (net (code "313") (name "unconnected-(CMP87-OUT_15-PadP$16)") (class "Default")
      (node (ref "CMP87") (pin "P$16") (pinfunction "OUT_15_P$16") (pintype "output"))
    )
    (net (code "314") (name "unconnected-(CMP88-PadE)") (class "Default")
      (node (ref "CMP88") (pin "E") (pinfunction "E_E") (pintype "input"))
    )
    (net (code "315") (name "unconnected-(CMP88-PadN0)") (class "Default")
      (node (ref "CMP88") (pin "N0") (pinfunction "N0_N0") (pintype "output"))
    )
    (net (code "316") (name "unconnected-(CMP88-PadN1)") (class "Default")
      (node (ref "CMP88") (pin "N1") (pinfunction "N1_N1") (pintype "output"))
    )
    (net (code "317") (name "unconnected-(CMP88-PadN2)") (class "Default")
      (node (ref "CMP88") (pin "N2") (pinfunction "N2_N2") (pintype "output"))
    )
    (net (code "318") (name "unconnected-(CMP88-PadN3)") (class "Default")
      (node (ref "CMP88") (pin "N3") (pinfunction "N3_N3") (pintype "output"))
    )
    (net (code "319") (name "unconnected-(CMP88-PadP2)") (class "Default")
      (node (ref "CMP88") (pin "P2") (pinfunction "P2_P2") (pintype "output"))
    )
    (net (code "320") (name "unconnected-(CMP88-PadP3)") (class "Default")
      (node (ref "CMP88") (pin "P3") (pinfunction "P3_P3") (pintype "output"))
    )
    (net (code "321") (name "unconnected-(CMP89-OUT-PadINPUT)") (class "Default")
      (node (ref "CMP89") (pin "INPUT") (pinfunction "OUT_INPUT") (pintype "output"))
    )
    (net (code "322") (name "unconnected-(CMP90-PadP)") (class "Default")
      (node (ref "CMP90") (pin "P") (pinfunction "P_P") (pintype "output"))
    )
    (net (code "323") (name "unconnected-(CMP91-PadP)") (class "Default")
      (node (ref "CMP91") (pin "P") (pinfunction "P_P") (pintype "output"))
    )
    (net (code "324") (name "unconnected-(CMP92-PadP)") (class "Default")
      (node (ref "CMP92") (pin "P") (pinfunction "P_P") (pintype "output"))
    )
    (net (code "325") (name "unconnected-(CMP93-N-PadOUT_M)") (class "Default")
      (node (ref "CMP93") (pin "OUT_M") (pinfunction "N_OUT_M") (pintype "output"))
    )
    (net (code "326") (name "unconnected-(CMP96-PadINPUT)") (class "Default")
      (node (ref "CMP96") (pin "INPUT") (pinfunction "INPUT_INPUT") (pintype "input"))
    )
    (net (code "327") (name "unconnected-(CMP97-OUT_6-PadP$7)") (class "Default")
      (node (ref "CMP97") (pin "P$7") (pinfunction "OUT_6_P$7") (pintype "output"))
    )
    (net (code "328") (name "unconnected-(CMP97-OUT_7-PadP$8)") (class "Default")
      (node (ref "CMP97") (pin "P$8") (pinfunction "OUT_7_P$8") (pintype "output"))
    )
    (net (code "329") (name "unconnected-(CMP97-OUT_8-PadP$9)") (class "Default")
      (node (ref "CMP97") (pin "P$9") (pinfunction "OUT_8_P$9") (pintype "output"))
    )
    (net (code "330") (name "unconnected-(CMP97-OUT_9-PadP$10)") (class "Default")
      (node (ref "CMP97") (pin "P$10") (pinfunction "OUT_9_P$10") (pintype "output"))
    )
    (net (code "331") (name "unconnected-(CMP97-OUT_10-PadP$11)") (class "Default")
      (node (ref "CMP97") (pin "P$11") (pinfunction "OUT_10_P$11") (pintype "output"))
    )
    (net (code "332") (name "unconnected-(CMP97-OUT_11-PadP$12)") (class "Default")
      (node (ref "CMP97") (pin "P$12") (pinfunction "OUT_11_P$12") (pintype "output"))
    )
    (net (code "333") (name "unconnected-(CMP97-OUT_12-PadP$13)") (class "Default")
      (node (ref "CMP97") (pin "P$13") (pinfunction "OUT_12_P$13") (pintype "output"))
    )
    (net (code "334") (name "unconnected-(CMP97-OUT_13-PadP$14)") (class "Default")
      (node (ref "CMP97") (pin "P$14") (pinfunction "OUT_13_P$14") (pintype "output"))
    )
    (net (code "335") (name "unconnected-(CMP97-OUT_14-PadP$15)") (class "Default")
      (node (ref "CMP97") (pin "P$15") (pinfunction "OUT_14_P$15") (pintype "output"))
    )
    (net (code "336") (name "unconnected-(CMP97-OUT_15-PadP$16)") (class "Default")
      (node (ref "CMP97") (pin "P$16") (pinfunction "OUT_15_P$16") (pintype "output"))
    )
    (net (code "337") (name "unconnected-(CMP99-OUT-PadINPUT)") (class "Default")
      (node (ref "CMP99") (pin "INPUT") (pinfunction "OUT_INPUT") (pintype "output"))
    )
  )
)
